# BeagleBone_Blue.net
KiCad netlist of a schematic drawn in EAGLE
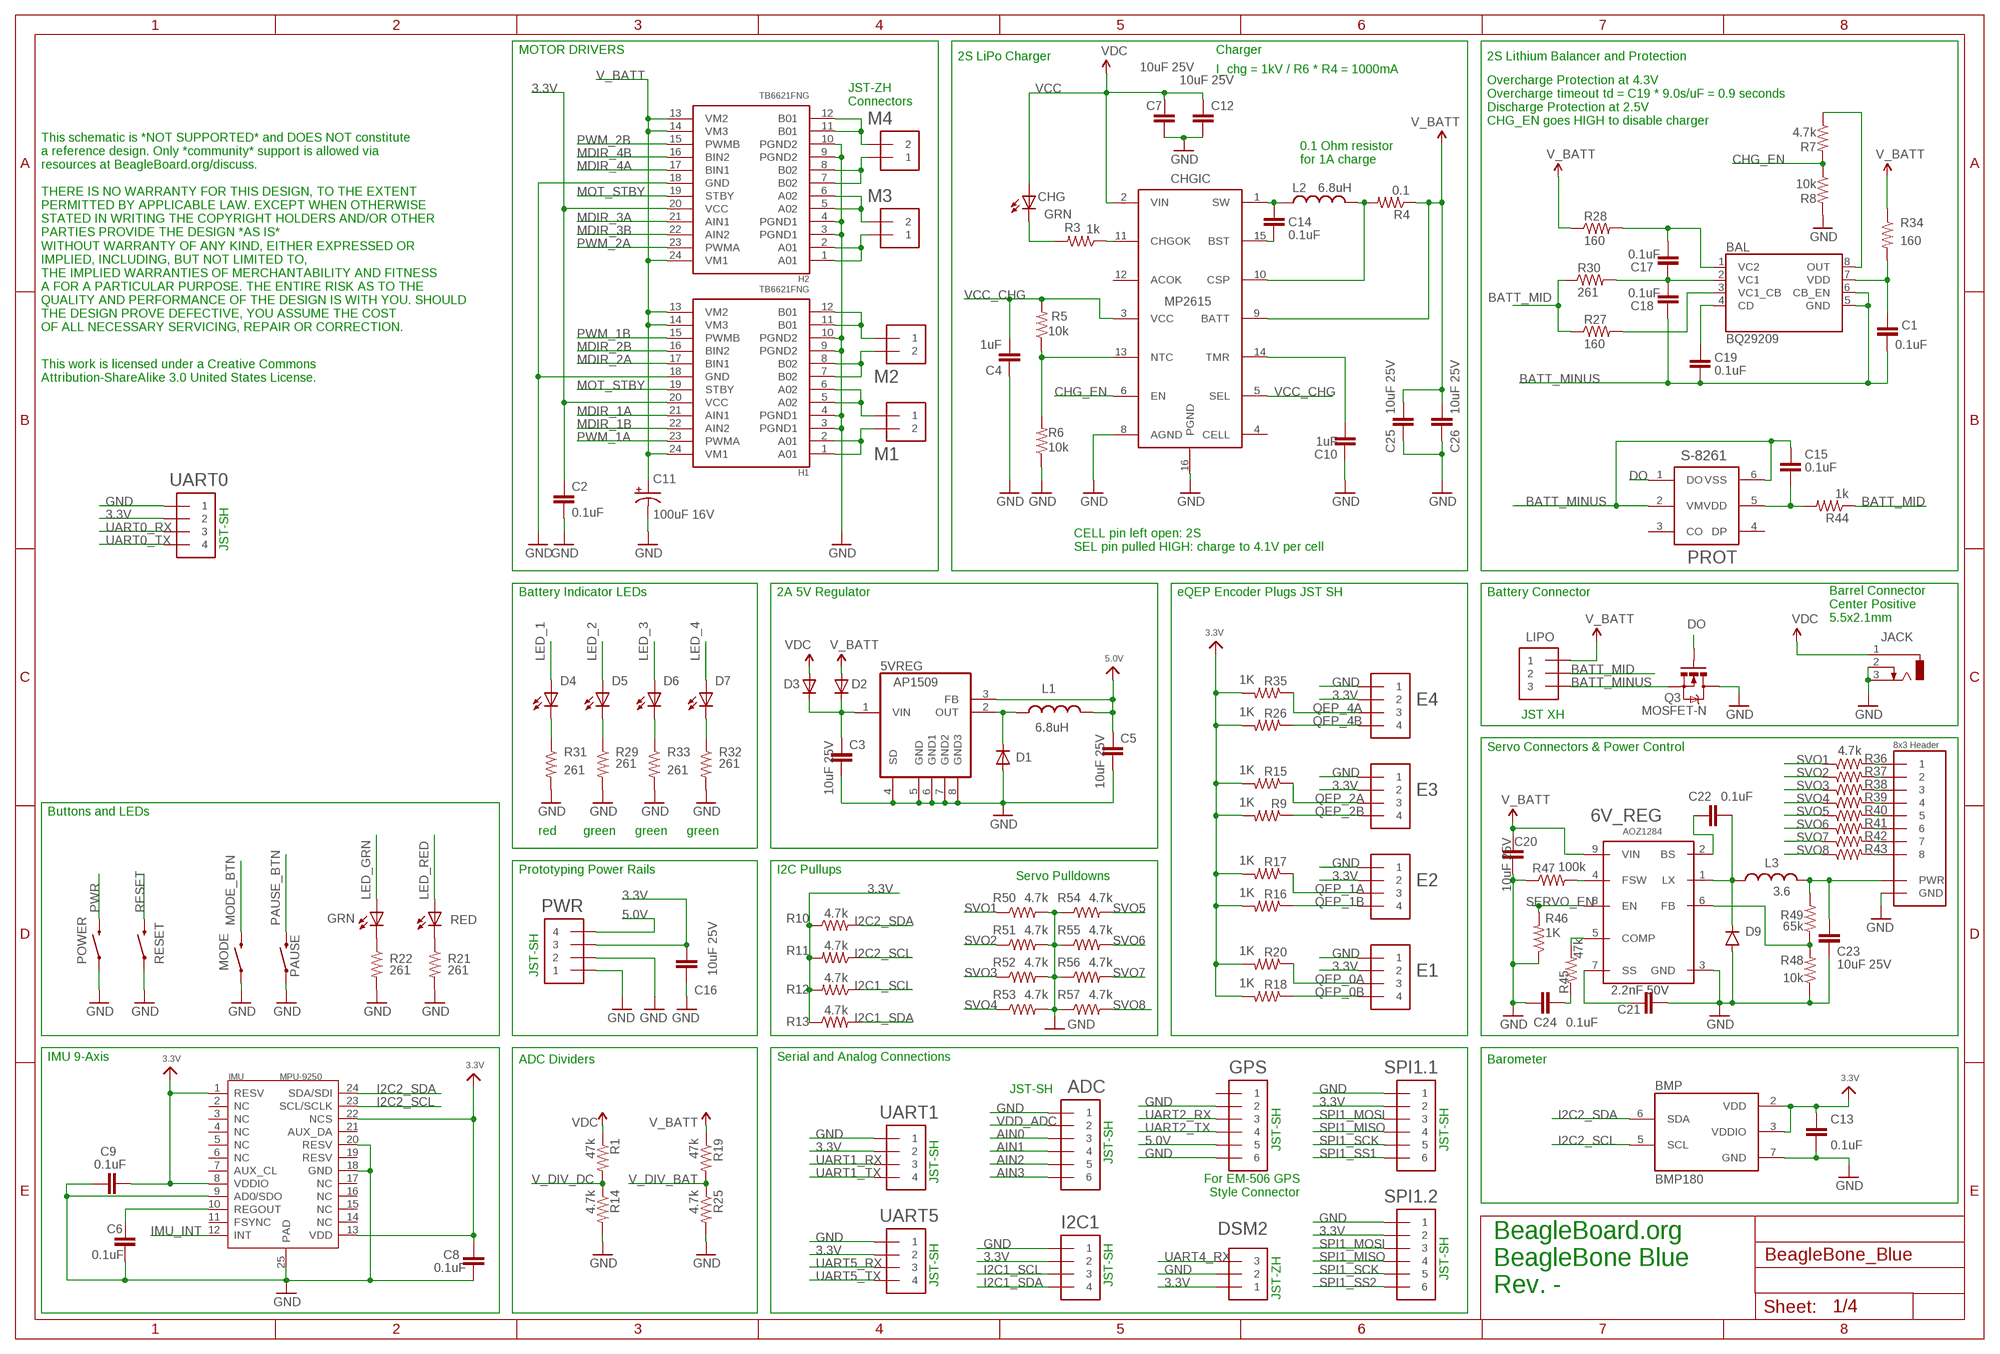
[diagram p0: schematic, sheet 1]
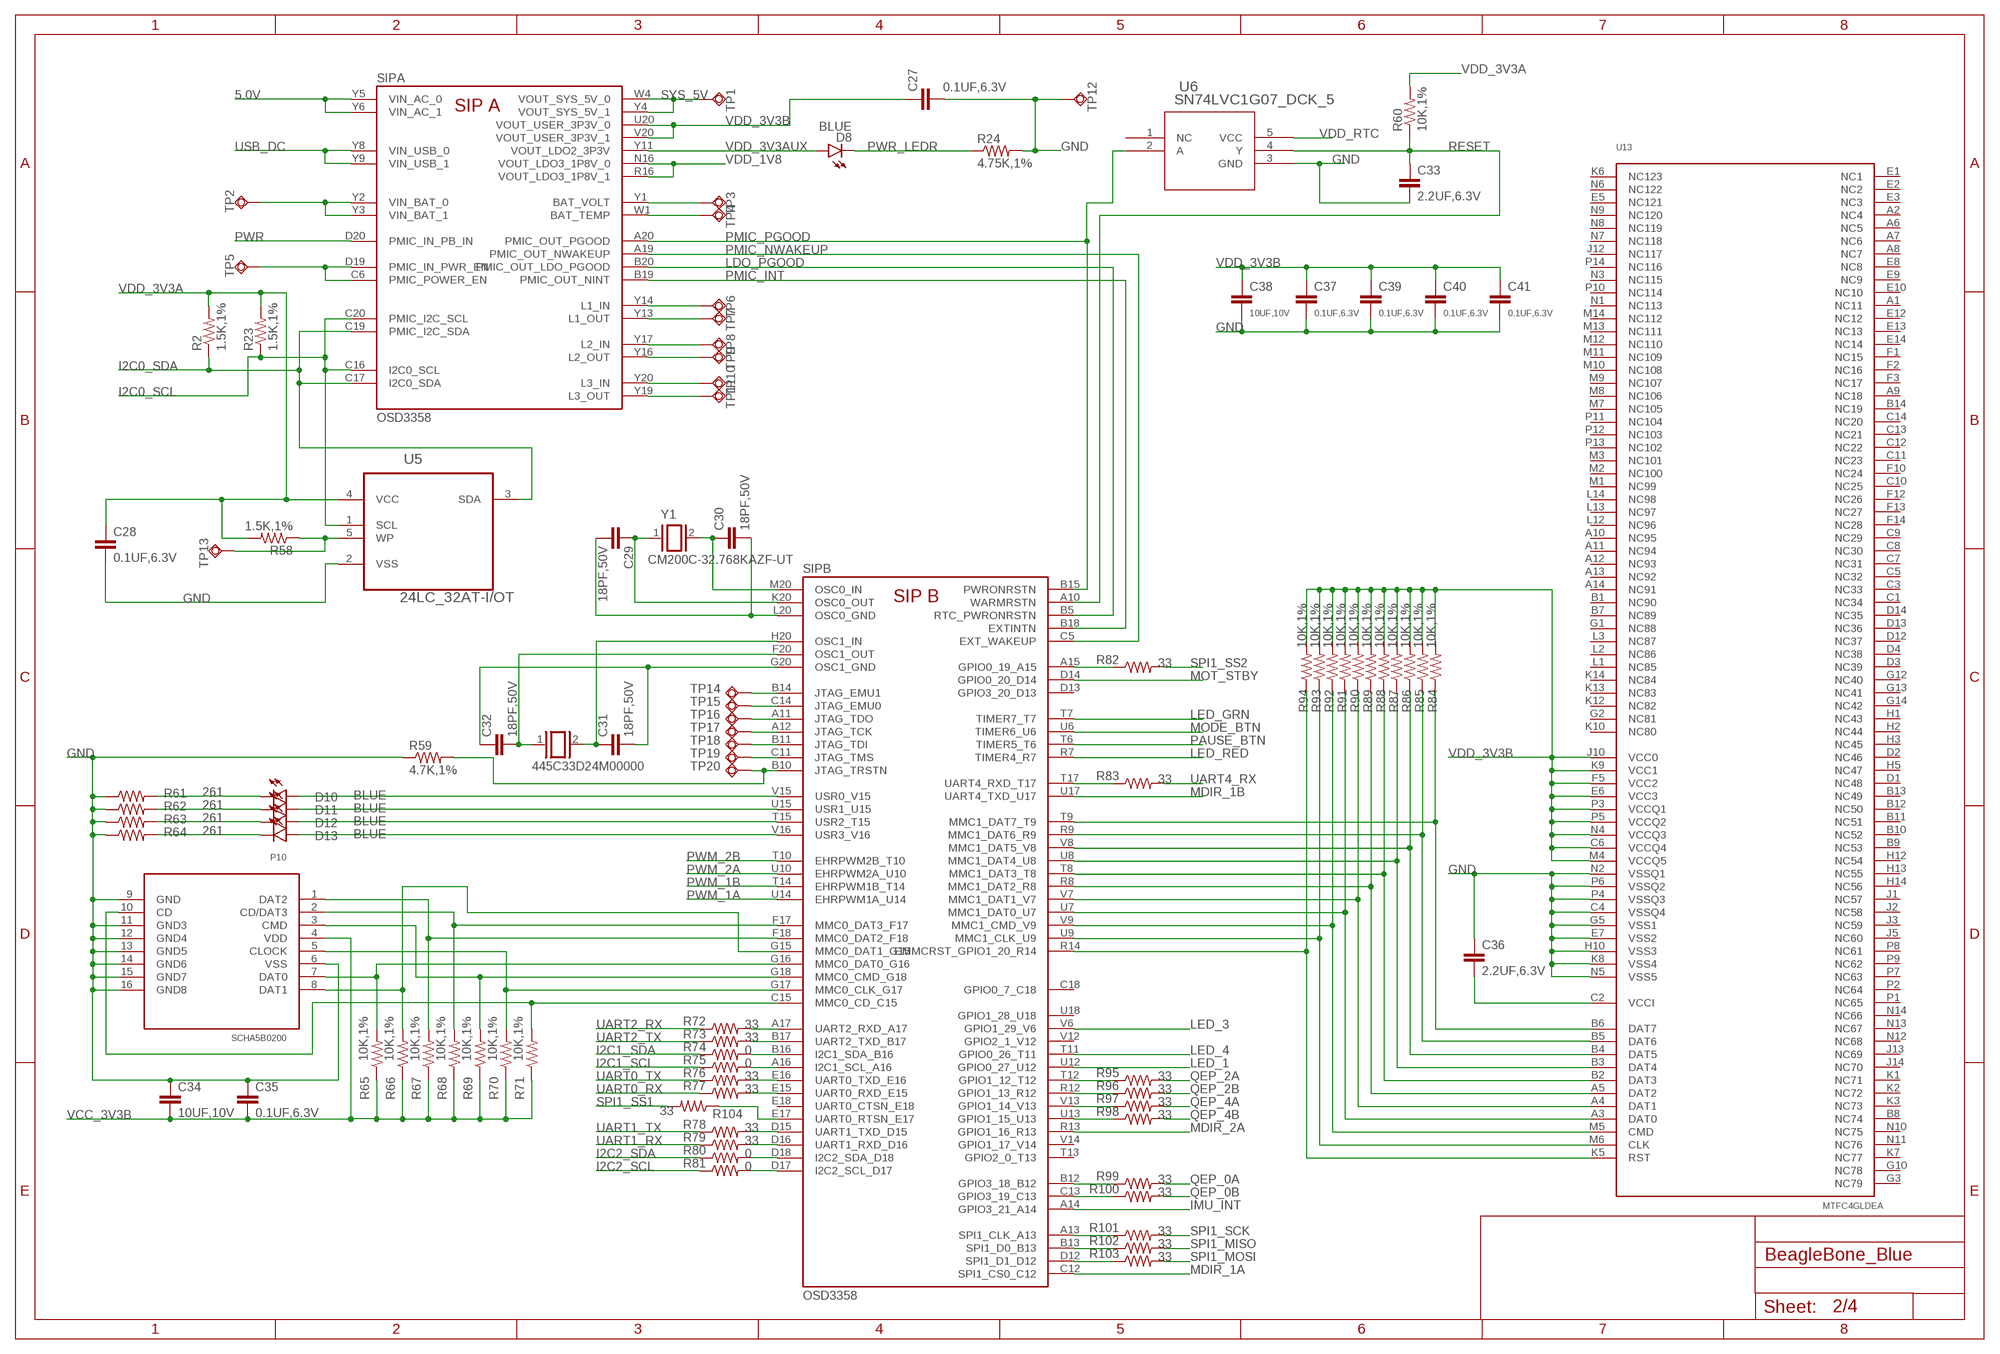
[diagram p1: schematic, sheet 2]
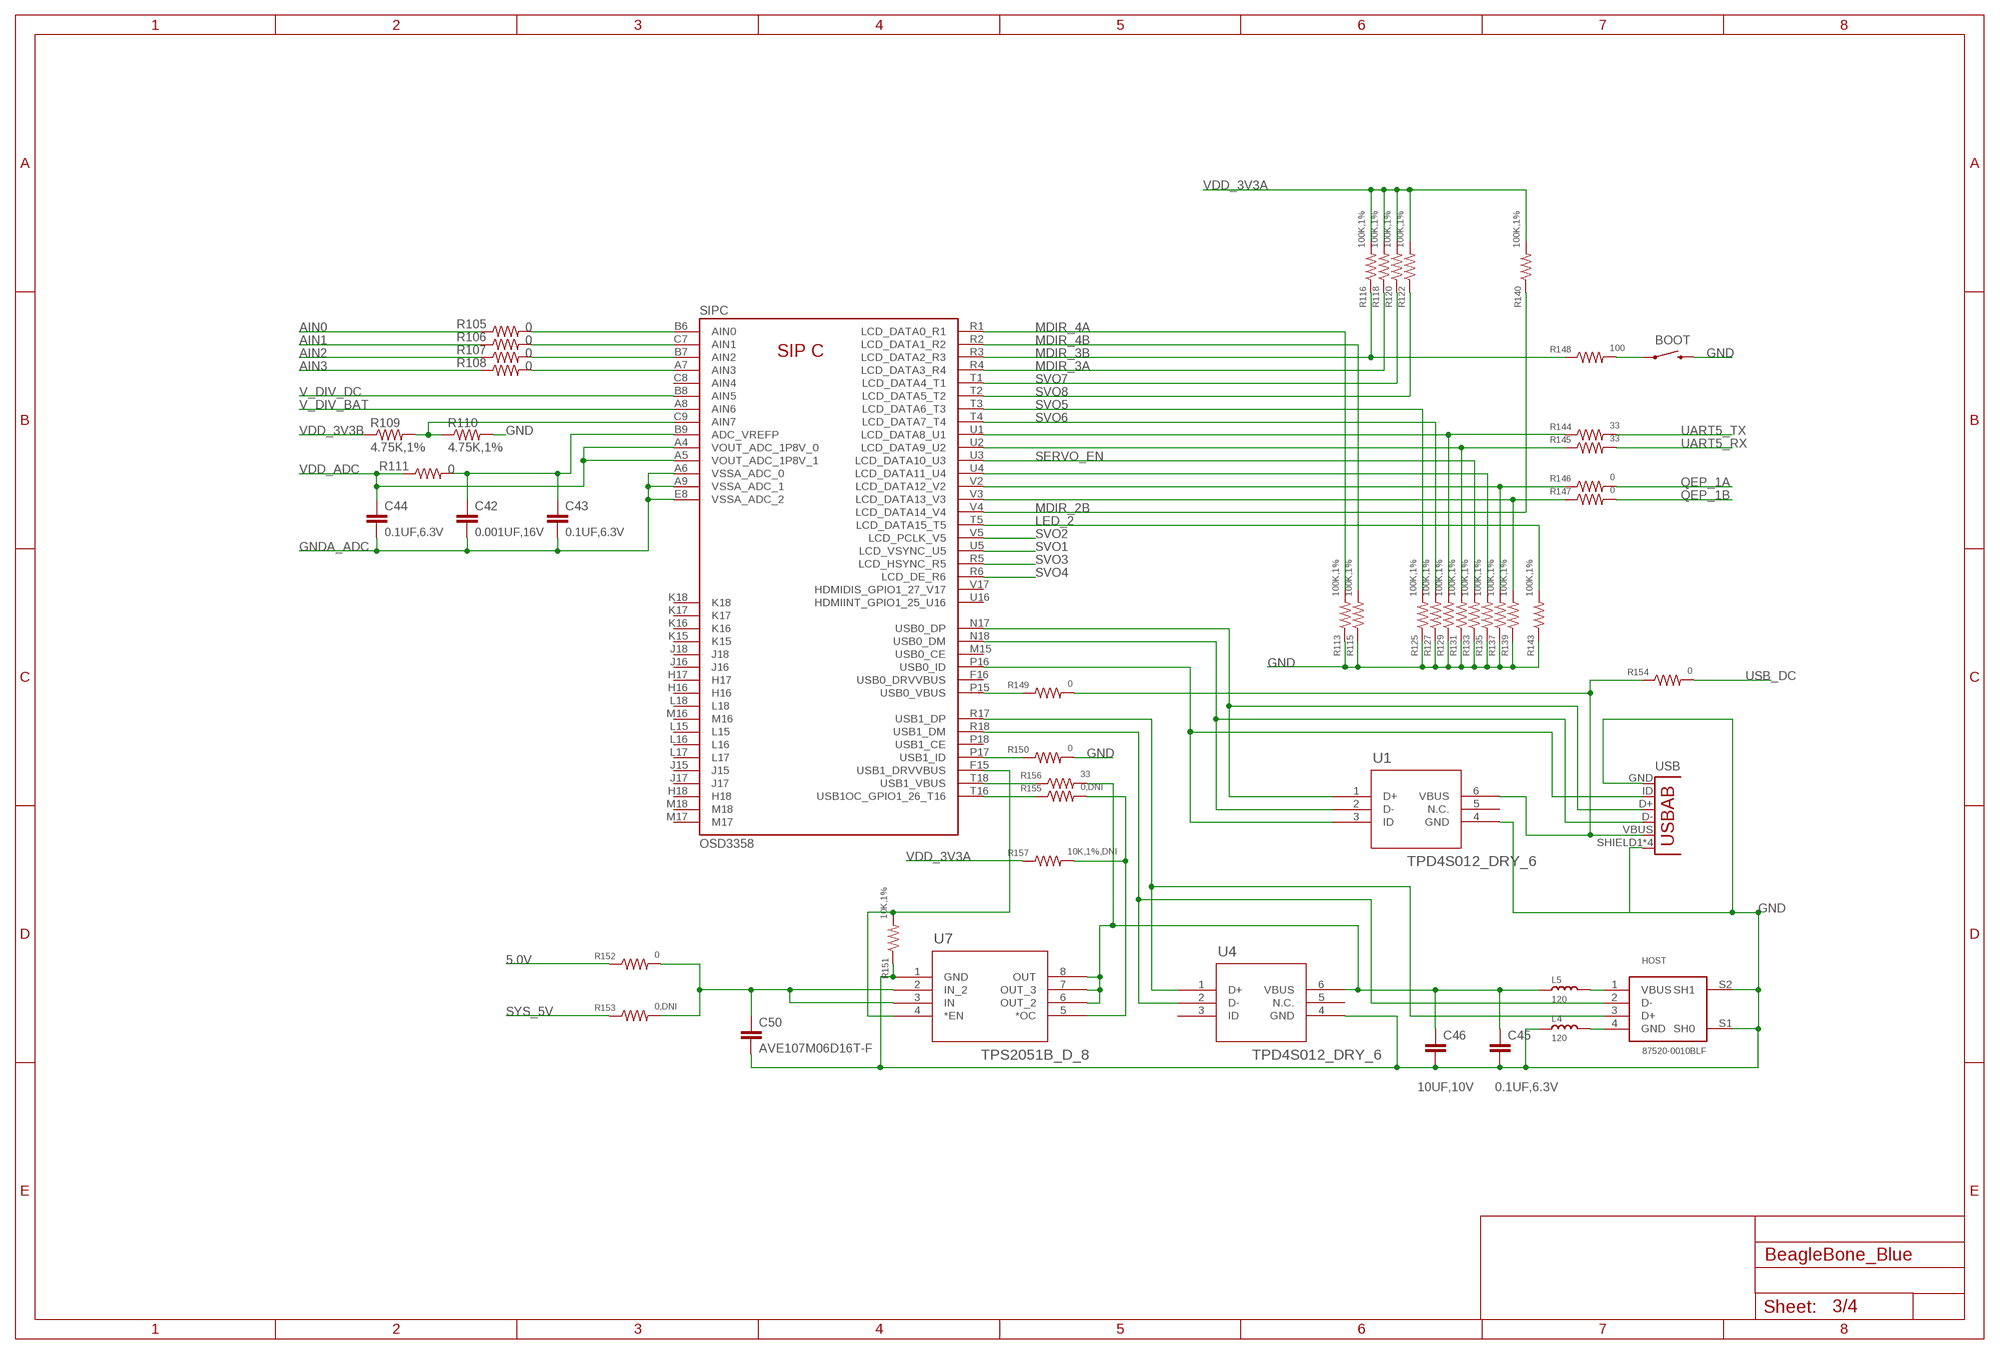
[diagram p2: schematic, sheet 3]
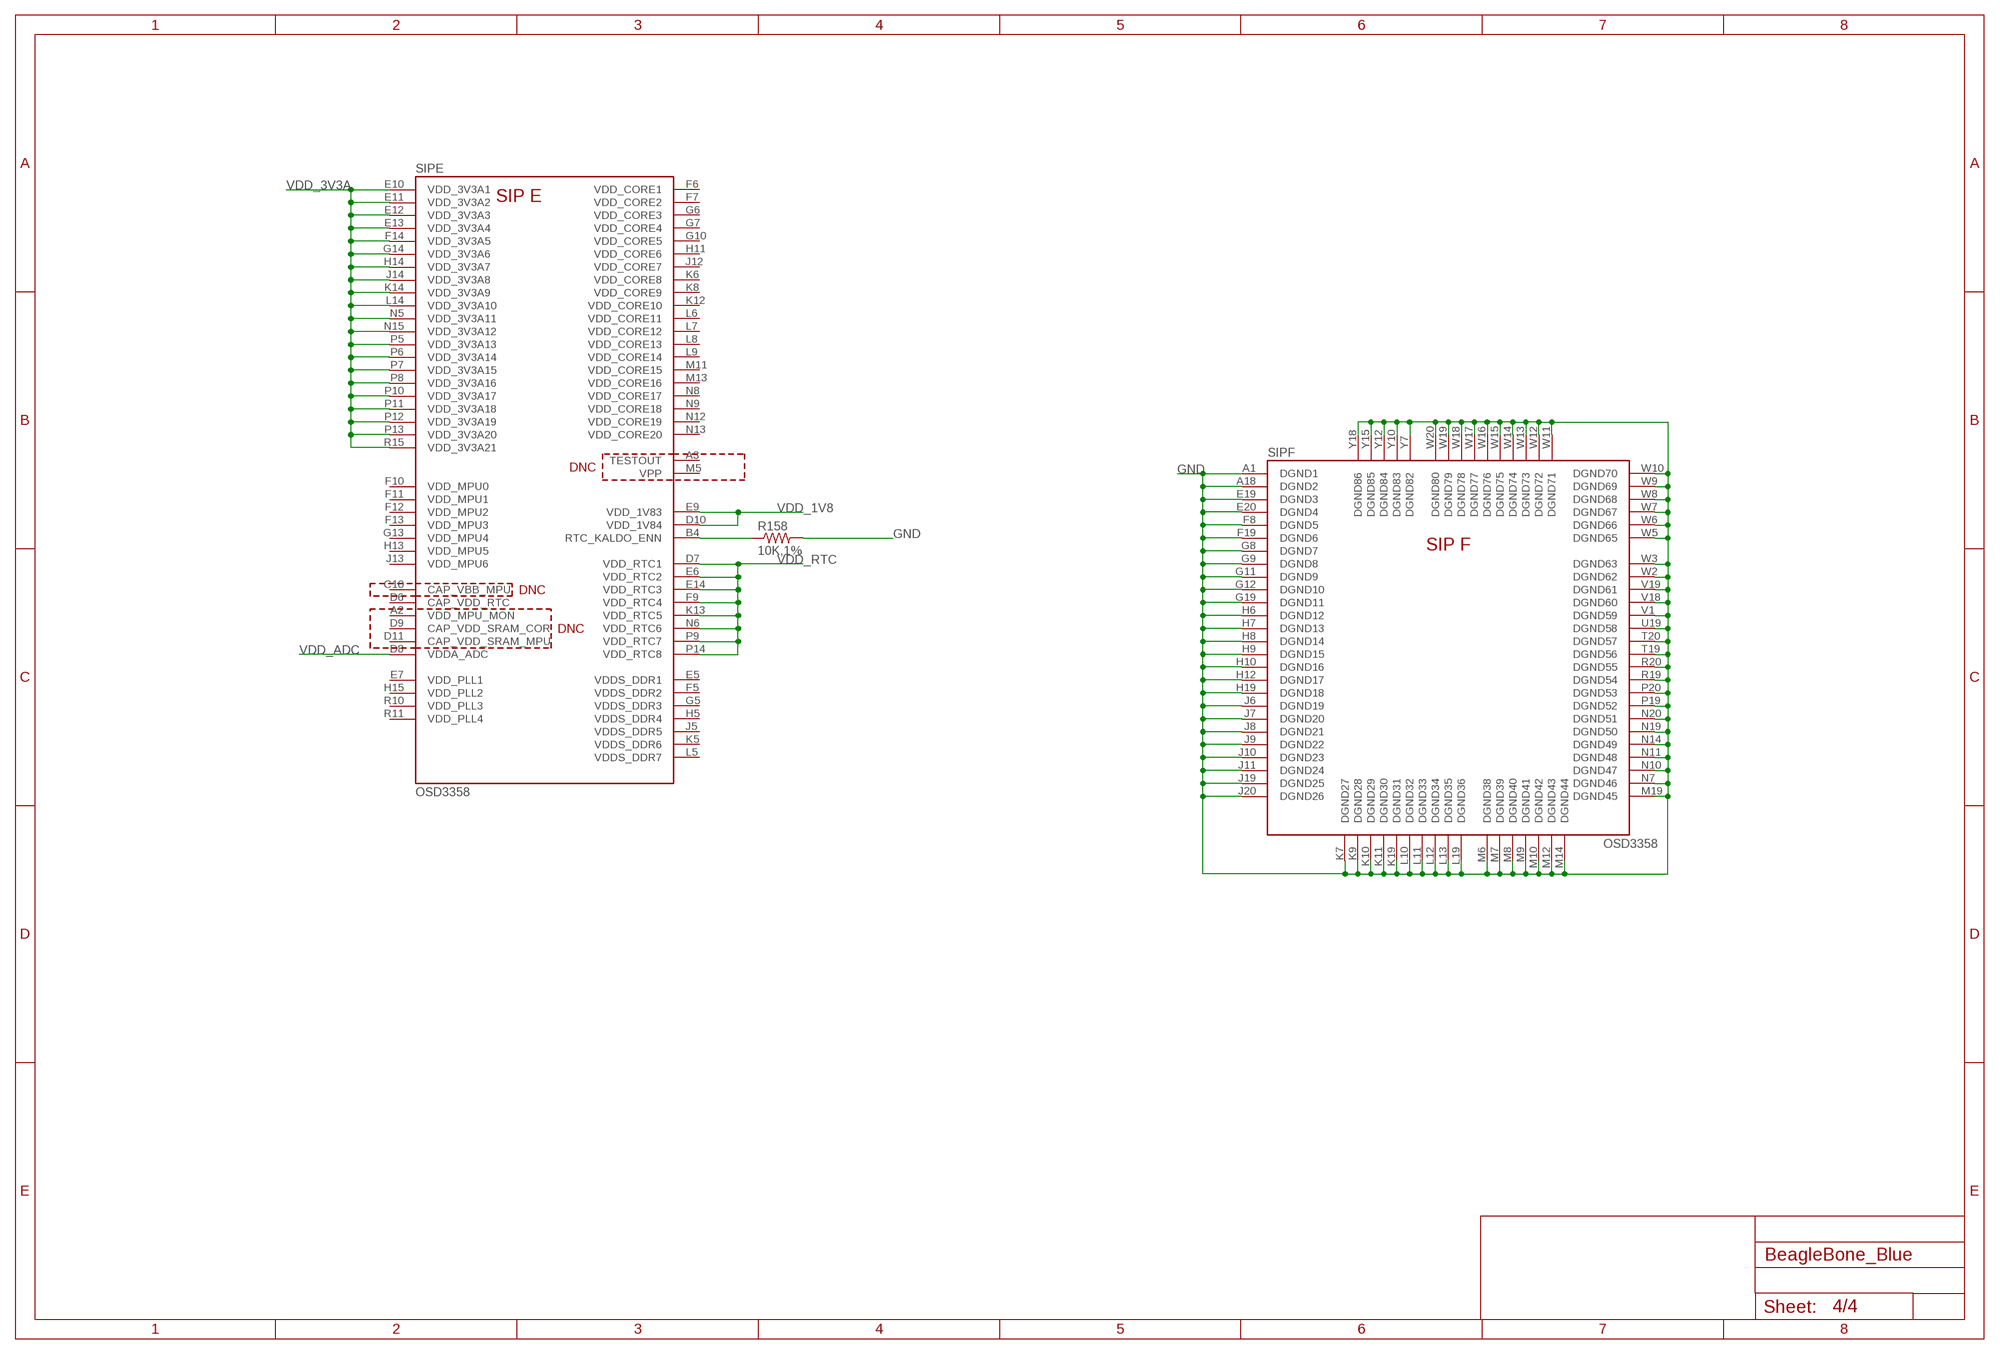
[diagram p3: schematic, sheet 4]

(export (version "E")
  (design (tool "Eeschema 10.0.6"))
  (components
    (comp (ref "5VREG")
      (value "AP1509SOIC-8-TIGHT")
      (footprint "eagle-import:SO08-TIGHT")
      (libsource (lib "eagle-import") (part "AP1509SOIC-8-TIGHT"))
    )
    (comp (ref "6V_REG")
      (value "AOZ1284")
      (footprint "eagle-import:SO08-EXPOSED")
      (libsource (lib "eagle-import") (part "AOZ1284"))
    )
    (comp (ref "ADC")
      (value "JST_SH_6")
      (footprint "eagle-import:JST_SH_6")
      (libsource (lib "eagle-import") (part "JST_SH_6"))
    )
    (comp (ref "BAL")
      (value "BQ29209")
      (footprint "eagle-import:8-SON_3X3MM")
      (libsource (lib "eagle-import") (part "BQ29209"))
    )
    (comp (ref "BMP")
      (value "BMP180")
      (footprint "eagle-import:BMP180")
      (libsource (lib "eagle-import") (part "BMP180"))
    )
    (comp (ref "C1")
      (value "0.1uF")
      (footprint "eagle-import:0402-CAP")
      (libsource (lib "eagle-import") (part "Strawson_Eagle_Lib_CAP0402-CAP"))
    )
    (comp (ref "C2")
      (value "0.1uF")
      (footprint "eagle-import:0402-CAP")
      (libsource (lib "eagle-import") (part "Strawson_Eagle_Lib_CAP0402-CAP"))
    )
    (comp (ref "C3")
      (value "10uF 25V")
      (footprint "eagle-import:0805")
      (libsource (lib "eagle-import") (part "CAP0805"))
    )
    (comp (ref "C4")
      (value "1uF")
      (footprint "eagle-import:0402-CAP")
      (libsource (lib "eagle-import") (part "Strawson_Eagle_Lib_CAP0402-CAP"))
    )
    (comp (ref "C5")
      (value "10uF 25V")
      (footprint "eagle-import:0805")
      (libsource (lib "eagle-import") (part "CAP0805"))
    )
    (comp (ref "C6")
      (value "0.1uF")
      (footprint "eagle-import:0402-CAP")
      (libsource (lib "eagle-import") (part "Strawson_Eagle_Lib_CAP0402-CAP"))
    )
    (comp (ref "C7")
      (value "10uF 25V")
      (footprint "eagle-import:0805")
      (libsource (lib "eagle-import") (part "CAP0805"))
    )
    (comp (ref "C8")
      (value "0.1uF")
      (footprint "eagle-import:0402-CAP")
      (libsource (lib "eagle-import") (part "Strawson_Eagle_Lib_CAP0402-CAP"))
    )
    (comp (ref "C9")
      (value "0.1uF")
      (footprint "eagle-import:0402-CAP")
      (libsource (lib "eagle-import") (part "Strawson_Eagle_Lib_CAP0402-CAP"))
    )
    (comp (ref "C10")
      (value "1uF")
      (footprint "eagle-import:0402-CAP")
      (libsource (lib "eagle-import") (part "Strawson_Eagle_Lib_CAP0402-CAP"))
    )
    (comp (ref "C11")
      (value "100uF 16V")
      (footprint "eagle-import:PANASONIC_D")
      (libsource (lib "eagle-import") (part "CPOL-USD"))
    )
    (comp (ref "C12")
      (value "10uF 25V")
      (footprint "eagle-import:0805")
      (libsource (lib "eagle-import") (part "CAP0805"))
    )
    (comp (ref "C13")
      (value "0.1uF")
      (footprint "eagle-import:0402-CAP")
      (libsource (lib "eagle-import") (part "Strawson_Eagle_Lib_CAP0402-CAP"))
    )
    (comp (ref "C14")
      (value "0.1uF")
      (footprint "eagle-import:0402-CAP")
      (libsource (lib "eagle-import") (part "Strawson_Eagle_Lib_CAP0402-CAP"))
    )
    (comp (ref "C15")
      (value "0.1uF")
      (footprint "eagle-import:0402-CAP")
      (libsource (lib "eagle-import") (part "Strawson_Eagle_Lib_CAP0402-CAP"))
    )
    (comp (ref "C16")
      (value "10uF 25V")
      (footprint "eagle-import:0805")
      (libsource (lib "eagle-import") (part "CAP0805"))
    )
    (comp (ref "C17")
      (value "0.1uF")
      (footprint "eagle-import:0402-CAP")
      (libsource (lib "eagle-import") (part "Strawson_Eagle_Lib_CAP0402-CAP"))
    )
    (comp (ref "C18")
      (value "0.1uF")
      (footprint "eagle-import:0402-CAP")
      (libsource (lib "eagle-import") (part "Strawson_Eagle_Lib_CAP0402-CAP"))
    )
    (comp (ref "C19")
      (value "0.1uF")
      (footprint "eagle-import:0402-CAP")
      (libsource (lib "eagle-import") (part "Strawson_Eagle_Lib_CAP0402-CAP"))
    )
    (comp (ref "C20")
      (value "10uF 25V")
      (footprint "eagle-import:0805")
      (libsource (lib "eagle-import") (part "CAP0805"))
    )
    (comp (ref "C21")
      (value "2.2nF 50V")
      (footprint "eagle-import:0402-CAP")
      (libsource (lib "eagle-import") (part "Strawson_Eagle_Lib_CAP0402-CAP"))
    )
    (comp (ref "C22")
      (value "0.1uF")
      (footprint "eagle-import:0402-CAP")
      (libsource (lib "eagle-import") (part "Strawson_Eagle_Lib_CAP0402-CAP"))
    )
    (comp (ref "C23")
      (value "10uF 25V")
      (footprint "eagle-import:0805")
      (libsource (lib "eagle-import") (part "CAP0805"))
    )
    (comp (ref "C24")
      (value "0.1uF")
      (footprint "eagle-import:0402-CAP")
      (libsource (lib "eagle-import") (part "Strawson_Eagle_Lib_CAP0402-CAP"))
    )
    (comp (ref "C25")
      (value "10uF 25V")
      (footprint "eagle-import:0805")
      (libsource (lib "eagle-import") (part "CAP0805"))
    )
    (comp (ref "C26")
      (value "10uF 25V")
      (footprint "eagle-import:0805")
      (libsource (lib "eagle-import") (part "CAP0805"))
    )
    (comp (ref "CHG")
      (value "GRN")
      (footprint "eagle-import:LED-0603")
      (libsource (lib "eagle-import") (part "SparkFun-LED_LED0603"))
    )
    (comp (ref "CHGIC")
      (value "MP2615")
      (footprint "eagle-import:MP2615")
      (libsource (lib "eagle-import") (part "MP2615"))
    )
    (comp (ref "D1")
      (value "DIODESOD-123")
      (footprint "eagle-import:SOD-123")
      (libsource (lib "eagle-import") (part "DIODESOD-123"))
    )
    (comp (ref "D2")
      (value "DIODESOD-123")
      (footprint "eagle-import:SOD-123")
      (libsource (lib "eagle-import") (part "DIODESOD-123"))
    )
    (comp (ref "D3")
      (value "DIODESOD-123")
      (footprint "eagle-import:SOD-123")
      (libsource (lib "eagle-import") (part "DIODESOD-123"))
    )
    (comp (ref "D4")
      (value "RED")
      (footprint "eagle-import:LED-0603")
      (libsource (lib "eagle-import") (part "SparkFun-LED_LED0603"))
    )
    (comp (ref "D5")
      (value "GREEN")
      (footprint "eagle-import:LED-0603")
      (libsource (lib "eagle-import") (part "SparkFun-LED_LED0603"))
    )
    (comp (ref "D6")
      (value "GREEN")
      (footprint "eagle-import:LED-0603")
      (libsource (lib "eagle-import") (part "SparkFun-LED_LED0603"))
    )
    (comp (ref "D7")
      (value "GREEN")
      (footprint "eagle-import:LED-0603")
      (libsource (lib "eagle-import") (part "SparkFun-LED_LED0603"))
    )
    (comp (ref "D9")
      (value "DIODEDO214AA")
      (footprint "eagle-import:DO-214AA")
      (libsource (lib "eagle-import") (part "DIODEDO214AA"))
    )
    (comp (ref "DSM2")
      (value "JST_ZH_3SMD_TOP")
      (footprint "eagle-import:JST_ZH_3_SMD_TOP")
      (libsource (lib "eagle-import") (part "JST_ZH_3SMD_TOP"))
    )
    (comp (ref "E1")
      (value "JST_SH_4")
      (footprint "eagle-import:JST_SH_4_SMD")
      (libsource (lib "eagle-import") (part "JST_SH_4"))
    )
    (comp (ref "E2")
      (value "JST_SH_4")
      (footprint "eagle-import:JST_SH_4_SMD")
      (libsource (lib "eagle-import") (part "JST_SH_4"))
    )
    (comp (ref "E3")
      (value "JST_SH_4")
      (footprint "eagle-import:JST_SH_4_SMD")
      (libsource (lib "eagle-import") (part "JST_SH_4"))
    )
    (comp (ref "E4")
      (value "JST_SH_4")
      (footprint "eagle-import:JST_SH_4_SMD")
      (libsource (lib "eagle-import") (part "JST_SH_4"))
    )
    (comp (ref "GPS")
      (value "JST_SH_6")
      (footprint "eagle-import:JST_SH_6")
      (libsource (lib "eagle-import") (part "JST_SH_6"))
    )
    (comp (ref "GRN")
      (value "GRN")
      (footprint "eagle-import:LED-0603")
      (libsource (lib "eagle-import") (part "SparkFun-LED_LED0603"))
    )
    (comp (ref "H1")
      (value "TB6621FNG")
      (footprint "eagle-import:SSOP24")
      (libsource (lib "eagle-import") (part "TB6621FNG"))
    )
    (comp (ref "H2")
      (value "TB6621FNG")
      (footprint "eagle-import:SSOP24")
      (libsource (lib "eagle-import") (part "TB6621FNG"))
    )
    (comp (ref "I2C1")
      (value "JST_SH_4")
      (footprint "eagle-import:JST_SH_4_SMD")
      (libsource (lib "eagle-import") (part "JST_SH_4"))
    )
    (comp (ref "IMU")
      (value "MPU-9250")
      (footprint "eagle-import:QFN24G-0.4-3X3MM")
      (libsource (lib "eagle-import") (part "MPU-9250"))
    )
    (comp (ref "JACK")
      (value "5.5x2.1mm")
      (footprint "eagle-import:DCJ0303")
      (libsource (lib "eagle-import") (part "DCJ0303"))
    )
    (comp (ref "L1")
      (value "6.8uH")
      (footprint "eagle-import:SRN6045")
      (libsource (lib "eagle-import") (part "INDUCTORBOURNS_SRN6045"))
    )
    (comp (ref "L2")
      (value "6.8uH")
      (footprint "eagle-import:SRN6045")
      (libsource (lib "eagle-import") (part "INDUCTORBOURNS_SRN6045"))
    )
    (comp (ref "L3")
      (value "3.6")
      (footprint "eagle-import:8X8MM_INDUCTOR")
      (libsource (lib "eagle-import") (part "INDUCTOR"))
    )
    (comp (ref "LIPO")
      (value "JST_XH_3-PIN")
      (footprint "eagle-import:JST_XH_3-PIN")
      (libsource (lib "eagle-import") (part "JST_XH_3-PIN"))
    )
    (comp (ref "M1")
      (value "JST_ZH_2")
      (footprint "eagle-import:JST_ZH_2")
      (libsource (lib "eagle-import") (part "JST_ZH_2"))
    )
    (comp (ref "M2")
      (value "JST_ZH_2")
      (footprint "eagle-import:JST_ZH_2")
      (libsource (lib "eagle-import") (part "JST_ZH_2"))
    )
    (comp (ref "M3")
      (value "JST_ZH_2")
      (footprint "eagle-import:JST_ZH_2")
      (libsource (lib "eagle-import") (part "JST_ZH_2"))
    )
    (comp (ref "M4")
      (value "JST_ZH_2")
      (footprint "eagle-import:JST_ZH_2")
      (libsource (lib "eagle-import") (part "JST_ZH_2"))
    )
    (comp (ref "MODE")
      (value "SWITCH-MOMENTARY-2SMD-1101NE")
      (footprint "eagle-import:TACTILE-SWITCH-1101NE")
      (libsource (lib "eagle-import") (part "SWITCH-MOMENTARY-2SMD-1101NE"))
    )
    (comp (ref "PAUSE")
      (value "SWITCH-MOMENTARY-2SMD-1101NE")
      (footprint "eagle-import:TACTILE-SWITCH-1101NE")
      (libsource (lib "eagle-import") (part "SWITCH-MOMENTARY-2SMD-1101NE"))
    )
    (comp (ref "POWER")
      (value "SWITCH-MOMENTARY-2SMD-1101NE")
      (footprint "eagle-import:TACTILE-SWITCH-1101NE")
      (libsource (lib "eagle-import") (part "SWITCH-MOMENTARY-2SMD-1101NE"))
    )
    (comp (ref "PROT")
      (value "S-8261")
      (footprint "eagle-import:SOT-236")
      (libsource (lib "eagle-import") (part "S-8261"))
    )
    (comp (ref "PWR")
      (value "JST_SH_4")
      (footprint "eagle-import:JST_SH_4_SMD")
      (libsource (lib "eagle-import") (part "JST_SH_4"))
    )
    (comp (ref "Q3")
      (value "MOSFET-N")
      (footprint "eagle-import:SO08-TIGHT")
      (libsource (lib "eagle-import") (part "MOSFET-NCHANNEL"))
    )
    (comp (ref "R1")
      (value "47k")
      (footprint "eagle-import:0402-RES")
      (libsource (lib "eagle-import") (part "RESISTOR0402-RES"))
    )
    (comp (ref "R3")
      (value "1k")
      (footprint "eagle-import:0402-RES")
      (libsource (lib "eagle-import") (part "RESISTOR0402-RES"))
    )
    (comp (ref "R4")
      (value "0.1")
      (footprint "eagle-import:0603-RES")
      (libsource (lib "eagle-import") (part "RESISTOR0603"))
    )
    (comp (ref "R5")
      (value "10k")
      (footprint "eagle-import:0402-RES")
      (libsource (lib "eagle-import") (part "RESISTOR0402-RES"))
    )
    (comp (ref "R6")
      (value "10k")
      (footprint "eagle-import:0402-RES")
      (libsource (lib "eagle-import") (part "RESISTOR0402-RES"))
    )
    (comp (ref "R7")
      (value "4.7k")
      (footprint "eagle-import:0402-RES")
      (libsource (lib "eagle-import") (part "RESISTOR0402-RES"))
    )
    (comp (ref "R8")
      (value "10k")
      (footprint "eagle-import:0402-RES")
      (libsource (lib "eagle-import") (part "RESISTOR0402-RES"))
    )
    (comp (ref "R9")
      (value "1K")
      (footprint "eagle-import:0402-RES")
      (libsource (lib "eagle-import") (part "RESISTOR0402-RES"))
    )
    (comp (ref "R10")
      (value "4.7k")
      (footprint "eagle-import:0402-RES")
      (libsource (lib "eagle-import") (part "RESISTOR0402-RES"))
    )
    (comp (ref "R11")
      (value "4.7k")
      (footprint "eagle-import:0402-RES")
      (libsource (lib "eagle-import") (part "RESISTOR0402-RES"))
    )
    (comp (ref "R12")
      (value "4.7k")
      (footprint "eagle-import:0402-RES")
      (libsource (lib "eagle-import") (part "RESISTOR0402-RES"))
    )
    (comp (ref "R13")
      (value "4.7k")
      (footprint "eagle-import:0402-RES")
      (libsource (lib "eagle-import") (part "RESISTOR0402-RES"))
    )
    (comp (ref "R14")
      (value "4.7k")
      (footprint "eagle-import:0402-RES")
      (libsource (lib "eagle-import") (part "RESISTOR0402-RES"))
    )
    (comp (ref "R15")
      (value "1K")
      (footprint "eagle-import:0402-RES")
      (libsource (lib "eagle-import") (part "RESISTOR0402-RES"))
    )
    (comp (ref "R16")
      (value "1K")
      (footprint "eagle-import:0402-RES")
      (libsource (lib "eagle-import") (part "RESISTOR0402-RES"))
    )
    (comp (ref "R17")
      (value "1K")
      (footprint "eagle-import:0402-RES")
      (libsource (lib "eagle-import") (part "RESISTOR0402-RES"))
    )
    (comp (ref "R18")
      (value "1K")
      (footprint "eagle-import:0402-RES")
      (libsource (lib "eagle-import") (part "RESISTOR0402-RES"))
    )
    (comp (ref "R19")
      (value "47k")
      (footprint "eagle-import:0402-RES")
      (libsource (lib "eagle-import") (part "RESISTOR0402-RES"))
    )
    (comp (ref "R20")
      (value "1K")
      (footprint "eagle-import:0402-RES")
      (libsource (lib "eagle-import") (part "RESISTOR0402-RES"))
    )
    (comp (ref "R21")
      (value "261")
      (footprint "eagle-import:0402-RES")
      (libsource (lib "eagle-import") (part "RESISTOR0402-RES"))
    )
    (comp (ref "R22")
      (value "261")
      (footprint "eagle-import:0402-RES")
      (libsource (lib "eagle-import") (part "RESISTOR0402-RES"))
    )
    (comp (ref "R25")
      (value "4.7k")
      (footprint "eagle-import:0402-RES")
      (libsource (lib "eagle-import") (part "RESISTOR0402-RES"))
    )
    (comp (ref "R26")
      (value "1K")
      (footprint "eagle-import:0402-RES")
      (libsource (lib "eagle-import") (part "RESISTOR0402-RES"))
    )
    (comp (ref "R27")
      (value "160")
      (footprint "eagle-import:0402-RES")
      (libsource (lib "eagle-import") (part "RESISTOR0402-RES"))
    )
    (comp (ref "R28")
      (value "160")
      (footprint "eagle-import:0402-RES")
      (libsource (lib "eagle-import") (part "RESISTOR0402-RES"))
    )
    (comp (ref "R29")
      (value "261")
      (footprint "eagle-import:0402-RES")
      (libsource (lib "eagle-import") (part "RESISTOR0402-RES"))
    )
    (comp (ref "R30")
      (value "261")
      (footprint "eagle-import:0402-RES")
      (libsource (lib "eagle-import") (part "RESISTOR0402-RES"))
    )
    (comp (ref "R31")
      (value "261")
      (footprint "eagle-import:0402-RES")
      (libsource (lib "eagle-import") (part "RESISTOR0402-RES"))
    )
    (comp (ref "R32")
      (value "261")
      (footprint "eagle-import:0402-RES")
      (libsource (lib "eagle-import") (part "RESISTOR0402-RES"))
    )
    (comp (ref "R33")
      (value "261")
      (footprint "eagle-import:0402-RES")
      (libsource (lib "eagle-import") (part "RESISTOR0402-RES"))
    )
    (comp (ref "R34")
      (value "160")
      (footprint "eagle-import:0402-RES")
      (libsource (lib "eagle-import") (part "RESISTOR0402-RES"))
    )
    (comp (ref "R35")
      (value "1K")
      (footprint "eagle-import:0402-RES")
      (libsource (lib "eagle-import") (part "RESISTOR0402-RES"))
    )
    (comp (ref "R36")
      (value "4.7k")
      (footprint "eagle-import:0402-RES")
      (libsource (lib "eagle-import") (part "RESISTOR0402-RES"))
    )
    (comp (ref "R37")
      (value "4.7k")
      (footprint "eagle-import:0402-RES")
      (libsource (lib "eagle-import") (part "RESISTOR0402-RES"))
    )
    (comp (ref "R38")
      (value "4.7k")
      (footprint "eagle-import:0402-RES")
      (libsource (lib "eagle-import") (part "RESISTOR0402-RES"))
    )
    (comp (ref "R39")
      (value "4.7k")
      (footprint "eagle-import:0402-RES")
      (libsource (lib "eagle-import") (part "RESISTOR0402-RES"))
    )
    (comp (ref "R40")
      (value "4.7k")
      (footprint "eagle-import:0402-RES")
      (libsource (lib "eagle-import") (part "RESISTOR0402-RES"))
    )
    (comp (ref "R41")
      (value "4.7k")
      (footprint "eagle-import:0402-RES")
      (libsource (lib "eagle-import") (part "RESISTOR0402-RES"))
    )
    (comp (ref "R42")
      (value "4.7k")
      (footprint "eagle-import:0402-RES")
      (libsource (lib "eagle-import") (part "RESISTOR0402-RES"))
    )
    (comp (ref "R43")
      (value "4.7k")
      (footprint "eagle-import:0402-RES")
      (libsource (lib "eagle-import") (part "RESISTOR0402-RES"))
    )
    (comp (ref "R44")
      (value "1k")
      (footprint "eagle-import:0402-RES")
      (libsource (lib "eagle-import") (part "RESISTOR0402-RES"))
    )
    (comp (ref "R45")
      (value "47k")
      (footprint "eagle-import:0402-RES")
      (libsource (lib "eagle-import") (part "RESISTOR0402-RES"))
    )
    (comp (ref "R46")
      (value "1K")
      (footprint "eagle-import:0402-RES")
      (libsource (lib "eagle-import") (part "RESISTOR0402-RES"))
    )
    (comp (ref "R47")
      (value "100k")
      (footprint "eagle-import:0402-RES")
      (libsource (lib "eagle-import") (part "RESISTOR0402-RES"))
    )
    (comp (ref "R48")
      (value "10k")
      (footprint "eagle-import:0402-RES")
      (libsource (lib "eagle-import") (part "RESISTOR0402-RES"))
    )
    (comp (ref "R49")
      (value "65k")
      (footprint "eagle-import:0402-RES")
      (libsource (lib "eagle-import") (part "RESISTOR0402-RES"))
    )
    (comp (ref "R50")
      (value "4.7k")
      (footprint "eagle-import:0402-RES")
      (libsource (lib "eagle-import") (part "RESISTOR0402-RES"))
    )
    (comp (ref "R51")
      (value "4.7k")
      (footprint "eagle-import:0402-RES")
      (libsource (lib "eagle-import") (part "RESISTOR0402-RES"))
    )
    (comp (ref "R52")
      (value "4.7k")
      (footprint "eagle-import:0402-RES")
      (libsource (lib "eagle-import") (part "RESISTOR0402-RES"))
    )
    (comp (ref "R53")
      (value "4.7k")
      (footprint "eagle-import:0402-RES")
      (libsource (lib "eagle-import") (part "RESISTOR0402-RES"))
    )
    (comp (ref "R54")
      (value "4.7k")
      (footprint "eagle-import:0402-RES")
      (libsource (lib "eagle-import") (part "RESISTOR0402-RES"))
    )
    (comp (ref "R55")
      (value "4.7k")
      (footprint "eagle-import:0402-RES")
      (libsource (lib "eagle-import") (part "RESISTOR0402-RES"))
    )
    (comp (ref "R56")
      (value "4.7k")
      (footprint "eagle-import:0402-RES")
      (libsource (lib "eagle-import") (part "RESISTOR0402-RES"))
    )
    (comp (ref "R57")
      (value "4.7k")
      (footprint "eagle-import:0402-RES")
      (libsource (lib "eagle-import") (part "RESISTOR0402-RES"))
    )
    (comp (ref "RED")
      (value "RED")
      (footprint "eagle-import:LED-0603")
      (libsource (lib "eagle-import") (part "SparkFun-LED_LED0603"))
    )
    (comp (ref "RESET")
      (value "SWITCH-MOMENTARY-2SMD-1101NE")
      (footprint "eagle-import:TACTILE-SWITCH-1101NE")
      (libsource (lib "eagle-import") (part "SWITCH-MOMENTARY-2SMD-1101NE"))
    )
    (comp (ref "SPI1.1")
      (value "JST_SH_6")
      (footprint "eagle-import:JST_SH_6")
      (libsource (lib "eagle-import") (part "JST_SH_6"))
    )
    (comp (ref "SPI1.2")
      (value "JST_SH_6")
      (footprint "eagle-import:JST_SH_6")
      (libsource (lib "eagle-import") (part "JST_SH_6"))
    )
    (comp (ref "U$1")
      (value "SERVO_HEADERS_8X")
      (footprint "eagle-import:3X8_0.1__HEADER")
      (libsource (lib "eagle-import") (part "SERVO_HEADERS_8X"))
    )
    (comp (ref "UART0")
      (value "JST_SH_4")
      (footprint "eagle-import:JST_SH_4_SMD")
      (libsource (lib "eagle-import") (part "JST_SH_4"))
    )
    (comp (ref "UART1")
      (value "JST_SH_4")
      (footprint "eagle-import:JST_SH_4_SMD")
      (libsource (lib "eagle-import") (part "JST_SH_4"))
    )
    (comp (ref "UART5")
      (value "JST_SH_4")
      (footprint "eagle-import:JST_SH_4_SMD")
      (libsource (lib "eagle-import") (part "JST_SH_4"))
    )
    (comp (ref "BOOT")
      (value "SWITCH-MOMENTARY-2SMD-1101NE")
      (footprint "eagle-import:TACTILE-SWITCH-1101NE")
      (libsource (lib "eagle-import") (part "SWITCH-MOMENTARY-2SMD-1101NE"))
    )
    (comp (ref "C42")
      (value "0.001UF,16V")
      (footprint "eagle-import:0402-CAP")
      (libsource (lib "eagle-import") (part "Strawson_Eagle_Lib_CAP0402-CAP"))
    )
    (comp (ref "C43")
      (value "0.1UF,6.3V")
      (footprint "eagle-import:0402-CAP")
      (libsource (lib "eagle-import") (part "Strawson_Eagle_Lib_CAP0402-CAP"))
    )
    (comp (ref "C44")
      (value "0.1UF,6.3V")
      (footprint "eagle-import:0402-CAP")
      (libsource (lib "eagle-import") (part "Strawson_Eagle_Lib_CAP0402-CAP"))
    )
    (comp (ref "C45")
      (value "0.1UF,6.3V")
      (footprint "eagle-import:0402-CAP")
      (libsource (lib "eagle-import") (part "Strawson_Eagle_Lib_CAP0402-CAP"))
    )
    (comp (ref "C46")
      (value "10UF,10V")
      (footprint "eagle-import:0805")
      (libsource (lib "eagle-import") (part "Strawson_Eagle_Lib_CAP0805"))
    )
    (comp (ref "C50")
      (value "AVE107M06D16T-F")
      (footprint "eagle-import:AVE107M06D16T-F")
      (libsource (lib "eagle-import") (part "AVE107M06D16T-F"))
    )
    (comp (ref "HOST")
      (value "87520-0010BLF")
      (footprint "eagle-import:87520-0010BLF")
      (libsource (lib "eagle-import") (part "87520-0010BLF"))
    )
    (comp (ref "L4")
      (value "120")
      (footprint "eagle-import:L0603")
      (libsource (lib "eagle-import") (part "INDUCTOR/FERRITE-BEAD'0603'"))
    )
    (comp (ref "L5")
      (value "120")
      (footprint "eagle-import:L0603")
      (libsource (lib "eagle-import") (part "INDUCTOR/FERRITE-BEAD'0603'"))
    )
    (comp (ref "R105")
      (value "0")
      (footprint "eagle-import:0402-RES")
      (libsource (lib "eagle-import") (part "RESISTOR0402-RES"))
    )
    (comp (ref "R106")
      (value "0")
      (footprint "eagle-import:0402-RES")
      (libsource (lib "eagle-import") (part "RESISTOR0402-RES"))
    )
    (comp (ref "R107")
      (value "0")
      (footprint "eagle-import:0402-RES")
      (libsource (lib "eagle-import") (part "RESISTOR0402-RES"))
    )
    (comp (ref "R108")
      (value "0")
      (footprint "eagle-import:0402-RES")
      (libsource (lib "eagle-import") (part "RESISTOR0402-RES"))
    )
    (comp (ref "R109")
      (value "4.75K,1%")
      (footprint "eagle-import:0402-RES")
      (libsource (lib "eagle-import") (part "RESISTOR0402-RES"))
    )
    (comp (ref "R110")
      (value "4.75K,1%")
      (footprint "eagle-import:0402-RES")
      (libsource (lib "eagle-import") (part "RESISTOR0402-RES"))
    )
    (comp (ref "R111")
      (value "0")
      (footprint "eagle-import:0402-RES")
      (libsource (lib "eagle-import") (part "RESISTOR0402-RES"))
    )
    (comp (ref "R113")
      (value "100K,1%")
      (footprint "eagle-import:0402-RES")
      (libsource (lib "eagle-import") (part "RESISTOR0402-RES"))
    )
    (comp (ref "R115")
      (value "100K,1%")
      (footprint "eagle-import:0402-RES")
      (libsource (lib "eagle-import") (part "RESISTOR0402-RES"))
    )
    (comp (ref "R116")
      (value "100K,1%")
      (footprint "eagle-import:0402-RES")
      (libsource (lib "eagle-import") (part "RESISTOR0402-RES"))
    )
    (comp (ref "R118")
      (value "100K,1%")
      (footprint "eagle-import:0402-RES")
      (libsource (lib "eagle-import") (part "RESISTOR0402-RES"))
    )
    (comp (ref "R120")
      (value "100K,1%")
      (footprint "eagle-import:0402-RES")
      (libsource (lib "eagle-import") (part "RESISTOR0402-RES"))
    )
    (comp (ref "R122")
      (value "100K,1%")
      (footprint "eagle-import:0402-RES")
      (libsource (lib "eagle-import") (part "RESISTOR0402-RES"))
    )
    (comp (ref "R125")
      (value "100K,1%")
      (footprint "eagle-import:0402-RES")
      (libsource (lib "eagle-import") (part "RESISTOR0402-RES"))
    )
    (comp (ref "R127")
      (value "100K,1%")
      (footprint "eagle-import:0402-RES")
      (libsource (lib "eagle-import") (part "RESISTOR0402-RES"))
    )
    (comp (ref "R129")
      (value "100K,1%")
      (footprint "eagle-import:0402-RES")
      (libsource (lib "eagle-import") (part "RESISTOR0402-RES"))
    )
    (comp (ref "R131")
      (value "100K,1%")
      (footprint "eagle-import:0402-RES")
      (libsource (lib "eagle-import") (part "RESISTOR0402-RES"))
    )
    (comp (ref "R133")
      (value "100K,1%")
      (footprint "eagle-import:0402-RES")
      (libsource (lib "eagle-import") (part "RESISTOR0402-RES"))
    )
    (comp (ref "R135")
      (value "100K,1%")
      (footprint "eagle-import:0402-RES")
      (libsource (lib "eagle-import") (part "RESISTOR0402-RES"))
    )
    (comp (ref "R137")
      (value "100K,1%")
      (footprint "eagle-import:0402-RES")
      (libsource (lib "eagle-import") (part "RESISTOR0402-RES"))
    )
    (comp (ref "R139")
      (value "100K,1%")
      (footprint "eagle-import:0402-RES")
      (libsource (lib "eagle-import") (part "RESISTOR0402-RES"))
    )
    (comp (ref "R140")
      (value "100K,1%")
      (footprint "eagle-import:0402-RES")
      (libsource (lib "eagle-import") (part "RESISTOR0402-RES"))
    )
    (comp (ref "R143")
      (value "100K,1%")
      (footprint "eagle-import:0402-RES")
      (libsource (lib "eagle-import") (part "RESISTOR0402-RES"))
    )
    (comp (ref "R144")
      (value "33")
      (footprint "eagle-import:0402-RES")
      (libsource (lib "eagle-import") (part "RESISTOR0402-RES"))
    )
    (comp (ref "R145")
      (value "33")
      (footprint "eagle-import:0402-RES")
      (libsource (lib "eagle-import") (part "RESISTOR0402-RES"))
    )
    (comp (ref "R146")
      (value "0")
      (footprint "eagle-import:0402-RES")
      (libsource (lib "eagle-import") (part "RESISTOR0402-RES"))
    )
    (comp (ref "R147")
      (value "0")
      (footprint "eagle-import:0402-RES")
      (libsource (lib "eagle-import") (part "RESISTOR0402-RES"))
    )
    (comp (ref "R148")
      (value "100")
      (footprint "eagle-import:0402-RES")
      (libsource (lib "eagle-import") (part "RESISTOR0402-RES"))
    )
    (comp (ref "R149")
      (value "0")
      (footprint "eagle-import:0402-RES")
      (libsource (lib "eagle-import") (part "RESISTOR0402-RES"))
    )
    (comp (ref "R150")
      (value "0")
      (footprint "eagle-import:0402-RES")
      (libsource (lib "eagle-import") (part "RESISTOR0402-RES"))
    )
    (comp (ref "R151")
      (value "10K,1%")
      (footprint "eagle-import:0402-RES")
      (libsource (lib "eagle-import") (part "RESISTOR0402-RES"))
    )
    (comp (ref "R152")
      (value "0")
      (footprint "eagle-import:0402-RES")
      (libsource (lib "eagle-import") (part "RESISTOR0402-RES"))
    )
    (comp (ref "R153")
      (value "0,DNI")
      (footprint "eagle-import:0402-RES")
      (libsource (lib "eagle-import") (part "RESISTOR0402-RES"))
    )
    (comp (ref "R154")
      (value "0")
      (footprint "eagle-import:0402-RES")
      (libsource (lib "eagle-import") (part "RESISTOR0402-RES"))
    )
    (comp (ref "R155")
      (value "0,DNI")
      (footprint "eagle-import:0402-RES")
      (libsource (lib "eagle-import") (part "RESISTOR0402-RES"))
    )
    (comp (ref "R156")
      (value "33")
      (footprint "eagle-import:0402-RES")
      (libsource (lib "eagle-import") (part "RESISTOR0402-RES"))
    )
    (comp (ref "R157")
      (value "10K,1%,DNI")
      (footprint "eagle-import:0402-RES")
      (libsource (lib "eagle-import") (part "RESISTOR0402-RES"))
    )
    (comp (ref "SIP")
      (value "OSD3358")
      (footprint "eagle-import:OSD3358")
      (libsource (lib "eagle-import") (part "OSD3358"))
    )
    (comp (ref "U1")
      (value "TPD4S012_DRY_6")
      (footprint "eagle-import:DRY6")
      (fields
        (field (name "GENERIC_PART_NUMBER") "TPD4S012")
        (field (name "MANUFACTURER") "Texas Instruments")
        (field (name "MANUFACTURER_PART_NUMBER") "tpd4s012_dry_6")
      )
      (libsource (lib "eagle-import") (part "TPD4S012_DRY_6"))
    )
    (comp (ref "U4")
      (value "TPD4S012_DRY_6")
      (footprint "eagle-import:DRY6")
      (fields
        (field (name "GENERIC_PART_NUMBER") "TPD4S012")
        (field (name "MANUFACTURER") "Texas Instruments")
        (field (name "MANUFACTURER_PART_NUMBER") "tpd4s012_dry_6")
      )
      (libsource (lib "eagle-import") (part "TPD4S012_DRY_6"))
    )
    (comp (ref "U7")
      (value "TPS2051B_D_8")
      (footprint "eagle-import:D8")
      (fields
        (field (name "GENERIC_PART_NUMBER") "TPS2051B")
        (field (name "MANUFACTURER") "Texas Instruments")
        (field (name "MANUFACTURER_PART_NUMBER") "tps2051b_d_8")
      )
      (libsource (lib "eagle-import") (part "TPS2051B_D_8"))
    )
    (comp (ref "USB")
      (value "USB-AB")
      (footprint "eagle-import:USB-AB-MICRO-SMD")
      (libsource (lib "eagle-import") (part "USB-AB"))
    )
    (comp (ref "C27")
      (value "0.1UF,6.3V")
      (footprint "eagle-import:0402-CAP")
      (libsource (lib "eagle-import") (part "Strawson_Eagle_Lib_CAP0402-CAP"))
    )
    (comp (ref "C28")
      (value "0.1UF,6.3V")
      (footprint "eagle-import:0402-CAP")
      (libsource (lib "eagle-import") (part "Strawson_Eagle_Lib_CAP0402-CAP"))
    )
    (comp (ref "C29")
      (value "18PF,50V")
      (footprint "eagle-import:0402-CAP")
      (libsource (lib "eagle-import") (part "Strawson_Eagle_Lib_CAP0402-CAP"))
    )
    (comp (ref "C30")
      (value "18PF,50V")
      (footprint "eagle-import:0402-CAP")
      (libsource (lib "eagle-import") (part "Strawson_Eagle_Lib_CAP0402-CAP"))
    )
    (comp (ref "C31")
      (value "18PF,50V")
      (footprint "eagle-import:0402-CAP")
      (libsource (lib "eagle-import") (part "Strawson_Eagle_Lib_CAP0402-CAP"))
    )
    (comp (ref "C32")
      (value "18PF,50V")
      (footprint "eagle-import:0402-CAP")
      (libsource (lib "eagle-import") (part "Strawson_Eagle_Lib_CAP0402-CAP"))
    )
    (comp (ref "C33")
      (value "2.2UF,6.3V")
      (footprint "eagle-import:0402-CAP")
      (libsource (lib "eagle-import") (part "Strawson_Eagle_Lib_CAP0402-CAP"))
    )
    (comp (ref "C34")
      (value "10UF,10V")
      (footprint "eagle-import:0805")
      (libsource (lib "eagle-import") (part "Strawson_Eagle_Lib_CAP0805"))
    )
    (comp (ref "C35")
      (value "0.1UF,6.3V")
      (footprint "eagle-import:0402-CAP")
      (libsource (lib "eagle-import") (part "Strawson_Eagle_Lib_CAP0402-CAP"))
    )
    (comp (ref "C36")
      (value "2.2UF,6.3V")
      (footprint "eagle-import:0402-CAP")
      (libsource (lib "eagle-import") (part "Strawson_Eagle_Lib_CAP0402-CAP"))
    )
    (comp (ref "C37")
      (value "0.1UF,6.3V")
      (footprint "eagle-import:0402-CAP")
      (libsource (lib "eagle-import") (part "Strawson_Eagle_Lib_CAP0402-CAP"))
    )
    (comp (ref "C38")
      (value "10UF,10V")
      (footprint "eagle-import:0805")
      (libsource (lib "eagle-import") (part "Strawson_Eagle_Lib_CAP0805"))
    )
    (comp (ref "C39")
      (value "0.1UF,6.3V")
      (footprint "eagle-import:0402-CAP")
      (libsource (lib "eagle-import") (part "Strawson_Eagle_Lib_CAP0402-CAP"))
    )
    (comp (ref "C40")
      (value "0.1UF,6.3V")
      (footprint "eagle-import:0402-CAP")
      (libsource (lib "eagle-import") (part "Strawson_Eagle_Lib_CAP0402-CAP"))
    )
    (comp (ref "C41")
      (value "0.1UF,6.3V")
      (footprint "eagle-import:0402-CAP")
      (libsource (lib "eagle-import") (part "Strawson_Eagle_Lib_CAP0402-CAP"))
    )
    (comp (ref "D8")
      (value "BLUE")
      (footprint "eagle-import:LED-0603")
      (libsource (lib "eagle-import") (part "LED0603"))
    )
    (comp (ref "D10")
      (value "BLUE")
      (footprint "eagle-import:LED-0603")
      (libsource (lib "eagle-import") (part "LED0603"))
    )
    (comp (ref "D11")
      (value "BLUE")
      (footprint "eagle-import:LED-0603")
      (libsource (lib "eagle-import") (part "LED0603"))
    )
    (comp (ref "D12")
      (value "BLUE")
      (footprint "eagle-import:LED-0603")
      (libsource (lib "eagle-import") (part "LED0603"))
    )
    (comp (ref "D13")
      (value "BLUE")
      (footprint "eagle-import:LED-0603")
      (libsource (lib "eagle-import") (part "LED0603"))
    )
    (comp (ref "P10")
      (value "SCHA5B0200")
      (footprint "eagle-import:SCHA5B0200")
      (libsource (lib "eagle-import") (part "SCHA5B0200"))
    )
    (comp (ref "R2")
      (value "1.5K,1%")
      (footprint "eagle-import:0402-RES")
      (libsource (lib "eagle-import") (part "RESISTOR0402-RES"))
    )
    (comp (ref "R23")
      (value "1.5K,1%")
      (footprint "eagle-import:0402-RES")
      (libsource (lib "eagle-import") (part "RESISTOR0402-RES"))
    )
    (comp (ref "R24")
      (value "4.75K,1%")
      (footprint "eagle-import:0402-RES")
      (libsource (lib "eagle-import") (part "RESISTOR0402-RES"))
    )
    (comp (ref "R58")
      (value "1.5K,1%")
      (footprint "eagle-import:0402-RES")
      (libsource (lib "eagle-import") (part "RESISTOR0402-RES"))
    )
    (comp (ref "R59")
      (value "4.7K,1%")
      (footprint "eagle-import:0402-RES")
      (libsource (lib "eagle-import") (part "RESISTOR0402-RES"))
    )
    (comp (ref "R60")
      (value "10K,1%")
      (footprint "eagle-import:0402-RES")
      (libsource (lib "eagle-import") (part "RESISTOR0402-RES"))
    )
    (comp (ref "R61")
      (value "261")
      (footprint "eagle-import:0402-RES")
      (libsource (lib "eagle-import") (part "RESISTOR0402-RES"))
    )
    (comp (ref "R62")
      (value "261")
      (footprint "eagle-import:0402-RES")
      (libsource (lib "eagle-import") (part "RESISTOR0402-RES"))
    )
    (comp (ref "R63")
      (value "261")
      (footprint "eagle-import:0402-RES")
      (libsource (lib "eagle-import") (part "RESISTOR0402-RES"))
    )
    (comp (ref "R64")
      (value "261")
      (footprint "eagle-import:0402-RES")
      (libsource (lib "eagle-import") (part "RESISTOR0402-RES"))
    )
    (comp (ref "R65")
      (value "10K,1%")
      (footprint "eagle-import:0402-RES")
      (libsource (lib "eagle-import") (part "RESISTOR0402-RES"))
    )
    (comp (ref "R66")
      (value "10K,1%")
      (footprint "eagle-import:0402-RES")
      (libsource (lib "eagle-import") (part "RESISTOR0402-RES"))
    )
    (comp (ref "R67")
      (value "10K,1%")
      (footprint "eagle-import:0402-RES")
      (libsource (lib "eagle-import") (part "RESISTOR0402-RES"))
    )
    (comp (ref "R68")
      (value "10K,1%")
      (footprint "eagle-import:0402-RES")
      (libsource (lib "eagle-import") (part "RESISTOR0402-RES"))
    )
    (comp (ref "R69")
      (value "10K,1%")
      (footprint "eagle-import:0402-RES")
      (libsource (lib "eagle-import") (part "RESISTOR0402-RES"))
    )
    (comp (ref "R70")
      (value "10K,1%")
      (footprint "eagle-import:0402-RES")
      (libsource (lib "eagle-import") (part "RESISTOR0402-RES"))
    )
    (comp (ref "R71")
      (value "10K,1%")
      (footprint "eagle-import:0402-RES")
      (libsource (lib "eagle-import") (part "RESISTOR0402-RES"))
    )
    (comp (ref "R72")
      (value "33")
      (footprint "eagle-import:0402-RES")
      (libsource (lib "eagle-import") (part "RESISTOR0402-RES"))
    )
    (comp (ref "R73")
      (value "33")
      (footprint "eagle-import:0402-RES")
      (libsource (lib "eagle-import") (part "RESISTOR0402-RES"))
    )
    (comp (ref "R74")
      (value "0")
      (footprint "eagle-import:0402-RES")
      (libsource (lib "eagle-import") (part "RESISTOR0402-RES"))
    )
    (comp (ref "R75")
      (value "0")
      (footprint "eagle-import:0402-RES")
      (libsource (lib "eagle-import") (part "RESISTOR0402-RES"))
    )
    (comp (ref "R76")
      (value "33")
      (footprint "eagle-import:0402-RES")
      (libsource (lib "eagle-import") (part "RESISTOR0402-RES"))
    )
    (comp (ref "R77")
      (value "33")
      (footprint "eagle-import:0402-RES")
      (libsource (lib "eagle-import") (part "RESISTOR0402-RES"))
    )
    (comp (ref "R78")
      (value "33")
      (footprint "eagle-import:0402-RES")
      (libsource (lib "eagle-import") (part "RESISTOR0402-RES"))
    )
    (comp (ref "R79")
      (value "33")
      (footprint "eagle-import:0402-RES")
      (libsource (lib "eagle-import") (part "RESISTOR0402-RES"))
    )
    (comp (ref "R80")
      (value "0")
      (footprint "eagle-import:0402-RES")
      (libsource (lib "eagle-import") (part "RESISTOR0402-RES"))
    )
    (comp (ref "R81")
      (value "0")
      (footprint "eagle-import:0402-RES")
      (libsource (lib "eagle-import") (part "RESISTOR0402-RES"))
    )
    (comp (ref "R82")
      (value "33")
      (footprint "eagle-import:0402-RES")
      (libsource (lib "eagle-import") (part "RESISTOR0402-RES"))
    )
    (comp (ref "R83")
      (value "33")
      (footprint "eagle-import:0402-RES")
      (libsource (lib "eagle-import") (part "RESISTOR0402-RES"))
    )
    (comp (ref "R84")
      (value "10K,1%")
      (footprint "eagle-import:0402-RES")
      (libsource (lib "eagle-import") (part "RESISTOR0402-RES"))
    )
    (comp (ref "R85")
      (value "10K,1%")
      (footprint "eagle-import:0402-RES")
      (libsource (lib "eagle-import") (part "RESISTOR0402-RES"))
    )
    (comp (ref "R86")
      (value "10K,1%")
      (footprint "eagle-import:0402-RES")
      (libsource (lib "eagle-import") (part "RESISTOR0402-RES"))
    )
    (comp (ref "R87")
      (value "10K,1%")
      (footprint "eagle-import:0402-RES")
      (libsource (lib "eagle-import") (part "RESISTOR0402-RES"))
    )
    (comp (ref "R88")
      (value "10K,1%")
      (footprint "eagle-import:0402-RES")
      (libsource (lib "eagle-import") (part "RESISTOR0402-RES"))
    )
    (comp (ref "R89")
      (value "10K,1%")
      (footprint "eagle-import:0402-RES")
      (libsource (lib "eagle-import") (part "RESISTOR0402-RES"))
    )
    (comp (ref "R90")
      (value "10K,1%")
      (footprint "eagle-import:0402-RES")
      (libsource (lib "eagle-import") (part "RESISTOR0402-RES"))
    )
    (comp (ref "R91")
      (value "10K,1%")
      (footprint "eagle-import:0402-RES")
      (libsource (lib "eagle-import") (part "RESISTOR0402-RES"))
    )
    (comp (ref "R92")
      (value "10K,1%")
      (footprint "eagle-import:0402-RES")
      (libsource (lib "eagle-import") (part "RESISTOR0402-RES"))
    )
    (comp (ref "R93")
      (value "10K,1%")
      (footprint "eagle-import:0402-RES")
      (libsource (lib "eagle-import") (part "RESISTOR0402-RES"))
    )
    (comp (ref "R94")
      (value "10K,1%")
      (footprint "eagle-import:0402-RES")
      (libsource (lib "eagle-import") (part "RESISTOR0402-RES"))
    )
    (comp (ref "R95")
      (value "33")
      (footprint "eagle-import:0402-RES")
      (libsource (lib "eagle-import") (part "RESISTOR0402-RES"))
    )
    (comp (ref "R96")
      (value "33")
      (footprint "eagle-import:0402-RES")
      (libsource (lib "eagle-import") (part "RESISTOR0402-RES"))
    )
    (comp (ref "R97")
      (value "33")
      (footprint "eagle-import:0402-RES")
      (libsource (lib "eagle-import") (part "RESISTOR0402-RES"))
    )
    (comp (ref "R98")
      (value "33")
      (footprint "eagle-import:0402-RES")
      (libsource (lib "eagle-import") (part "RESISTOR0402-RES"))
    )
    (comp (ref "R99")
      (value "33")
      (footprint "eagle-import:0402-RES")
      (libsource (lib "eagle-import") (part "RESISTOR0402-RES"))
    )
    (comp (ref "R100")
      (value "33")
      (footprint "eagle-import:0402-RES")
      (libsource (lib "eagle-import") (part "RESISTOR0402-RES"))
    )
    (comp (ref "R101")
      (value "33")
      (footprint "eagle-import:0402-RES")
      (libsource (lib "eagle-import") (part "RESISTOR0402-RES"))
    )
    (comp (ref "R102")
      (value "33")
      (footprint "eagle-import:0402-RES")
      (libsource (lib "eagle-import") (part "RESISTOR0402-RES"))
    )
    (comp (ref "R103")
      (value "33")
      (footprint "eagle-import:0402-RES")
      (libsource (lib "eagle-import") (part "RESISTOR0402-RES"))
    )
    (comp (ref "R104")
      (value "33")
      (footprint "eagle-import:0402-RES")
      (libsource (lib "eagle-import") (part "RESISTOR0402-RES"))
    )
    (comp (ref "TP1")
      (value "TPSQB1,27")
      (footprint "eagle-import:B1,27")
      (libsource (lib "eagle-import") (part "TPSQB1,27"))
    )
    (comp (ref "TP2")
      (value "TPSQB1,27")
      (footprint "eagle-import:B1,27")
      (libsource (lib "eagle-import") (part "TPSQB1,27"))
    )
    (comp (ref "TP3")
      (value "TPSQB1,27")
      (footprint "eagle-import:B1,27")
      (libsource (lib "eagle-import") (part "TPSQB1,27"))
    )
    (comp (ref "TP4")
      (value "TPSQB1,27")
      (footprint "eagle-import:B1,27")
      (libsource (lib "eagle-import") (part "TPSQB1,27"))
    )
    (comp (ref "TP5")
      (value "TPSQB1,27")
      (footprint "eagle-import:B1,27")
      (libsource (lib "eagle-import") (part "TPSQB1,27"))
    )
    (comp (ref "TP6")
      (value "TPSQB1,27")
      (footprint "eagle-import:B1,27")
      (libsource (lib "eagle-import") (part "TPSQB1,27"))
    )
    (comp (ref "TP7")
      (value "TPSQB1,27")
      (footprint "eagle-import:B1,27")
      (libsource (lib "eagle-import") (part "TPSQB1,27"))
    )
    (comp (ref "TP8")
      (value "TPSQB1,27")
      (footprint "eagle-import:B1,27")
      (libsource (lib "eagle-import") (part "TPSQB1,27"))
    )
    (comp (ref "TP9")
      (value "TPSQB1,27")
      (footprint "eagle-import:B1,27")
      (libsource (lib "eagle-import") (part "TPSQB1,27"))
    )
    (comp (ref "TP10")
      (value "TPSQB1,27")
      (footprint "eagle-import:B1,27")
      (libsource (lib "eagle-import") (part "TPSQB1,27"))
    )
    (comp (ref "TP11")
      (value "TPSQB1,27")
      (footprint "eagle-import:B1,27")
      (libsource (lib "eagle-import") (part "TPSQB1,27"))
    )
    (comp (ref "TP12")
      (value "TPSQB1,27")
      (footprint "eagle-import:B1,27")
      (libsource (lib "eagle-import") (part "TPSQB1,27"))
    )
    (comp (ref "TP13")
      (value "TPSQB1,27")
      (footprint "eagle-import:B1,27")
      (libsource (lib "eagle-import") (part "TPSQB1,27"))
    )
    (comp (ref "TP14")
      (value "TPSQB1,27")
      (footprint "eagle-import:B1,27")
      (libsource (lib "eagle-import") (part "TPSQB1,27"))
    )
    (comp (ref "TP15")
      (value "TPSQB1,27")
      (footprint "eagle-import:B1,27")
      (libsource (lib "eagle-import") (part "TPSQB1,27"))
    )
    (comp (ref "TP16")
      (value "TPSQB1,27")
      (footprint "eagle-import:B1,27")
      (libsource (lib "eagle-import") (part "TPSQB1,27"))
    )
    (comp (ref "TP17")
      (value "TPSQB1,27")
      (footprint "eagle-import:B1,27")
      (libsource (lib "eagle-import") (part "TPSQB1,27"))
    )
    (comp (ref "TP18")
      (value "TPSQB1,27")
      (footprint "eagle-import:B1,27")
      (libsource (lib "eagle-import") (part "TPSQB1,27"))
    )
    (comp (ref "TP19")
      (value "TPSQB1,27")
      (footprint "eagle-import:B1,27")
      (libsource (lib "eagle-import") (part "TPSQB1,27"))
    )
    (comp (ref "TP20")
      (value "TPSQB1,27")
      (footprint "eagle-import:B1,27")
      (libsource (lib "eagle-import") (part "TPSQB1,27"))
    )
    (comp (ref "U5")
      (value "24LC_32AT-I/OT")
      (footprint "eagle-import:SOT95P290X145-5N")
      (fields (field (name "MPN") "24LC32AT-I/OT"))
      (libsource (lib "eagle-import") (part "24LC_32AT-I/OT"))
    )
    (comp (ref "U6")
      (value "SN74LVC1G07_DCK_5")
      (footprint "eagle-import:DCK5")
      (fields
        (field (name "GENERIC_PART_NUMBER") "SN74LVC1G07")
        (field (name "MANUFACTURER") "Texas Instruments")
        (field (name "MANUFACTURER_PART_NUMBER") "sn74lvc1g07_dck_5")
      )
      (libsource (lib "eagle-import") (part "SN74LVC1G07_DCK_5"))
    )
    (comp (ref "U8")
      (value "MTFC4GLDEA")
      (footprint "eagle-import:MTFC4GLDEA")
      (libsource (lib "eagle-import") (part "MTFC4GLDEA"))
    )
    (comp (ref "Y1")
      (value "CM200C-32.768KAZF-UT")
      (footprint "eagle-import:CM200C-32.768KAZF-UT")
      (libsource (lib "eagle-import") (part "CM200C-32.768KAZF-UT"))
    )
    (comp (ref "Y2")
      (value "445C33D24M00000")
      (footprint "eagle-import:445C33D24M00000")
      (libsource (lib "eagle-import") (part "445C33D24M00000"))
    )
    (comp (ref "R158")
      (value "10K,1%")
      (footprint "eagle-import:0402-RES")
      (libsource (lib "eagle-import") (part "RESISTOR0402-RES"))
    )
  )
  (nets
    (net (code "1") (name "3.3V") (class "Default")
      (node (ref "BMP") (pin "2") (pinfunction "VDD_2") (pintype "power_in"))
      (node (ref "BMP") (pin "3") (pinfunction "VDDIO_3") (pintype "power_in"))
      (node (ref "C13") (pin "1") (pinfunction "1_1") (pintype "passive"))
      (node (ref "C16") (pin "1") (pinfunction "1_1") (pintype "passive"))
      (node (ref "C2") (pin "2") (pinfunction "2_2") (pintype "passive"))
      (node (ref "C8") (pin "1") (pinfunction "1_1") (pintype "passive"))
      (node (ref "C9") (pin "2") (pinfunction "2_2") (pintype "passive"))
      (node (ref "DSM2") (pin "1") (pinfunction "1_1") (pintype "bidirectional"))
      (node (ref "E1") (pin "2") (pinfunction "2_2") (pintype "bidirectional"))
      (node (ref "E2") (pin "2") (pinfunction "2_2") (pintype "bidirectional"))
      (node (ref "E3") (pin "2") (pinfunction "2_2") (pintype "bidirectional"))
      (node (ref "E4") (pin "2") (pinfunction "2_2") (pintype "bidirectional"))
      (node (ref "H1") (pin "20") (pinfunction "VCC_20") (pintype "bidirectional"))
      (node (ref "H2") (pin "20") (pinfunction "VCC_20") (pintype "bidirectional"))
      (node (ref "I2C1") (pin "2") (pinfunction "2_2") (pintype "bidirectional"))
      (node (ref "IMU") (pin "1") (pinfunction "RESV_1") (pintype "bidirectional"))
      (node (ref "IMU") (pin "13") (pinfunction "VDD_13") (pintype "bidirectional"))
      (node (ref "IMU") (pin "22") (pinfunction "NCS_22") (pintype "bidirectional"))
      (node (ref "IMU") (pin "8") (pinfunction "VDDIO_8") (pintype "bidirectional"))
      (node (ref "PWR") (pin "3") (pinfunction "3_3") (pintype "bidirectional"))
      (node (ref "R10") (pin "1") (pinfunction "1_1") (pintype "passive"))
      (node (ref "R11") (pin "2") (pinfunction "2_2") (pintype "passive"))
      (node (ref "R12") (pin "2") (pinfunction "2_2") (pintype "passive"))
      (node (ref "R13") (pin "1") (pinfunction "1_1") (pintype "passive"))
      (node (ref "R15") (pin "2") (pinfunction "2_2") (pintype "passive"))
      (node (ref "R16") (pin "2") (pinfunction "2_2") (pintype "passive"))
      (node (ref "R17") (pin "2") (pinfunction "2_2") (pintype "passive"))
      (node (ref "R18") (pin "2") (pinfunction "2_2") (pintype "passive"))
      (node (ref "R20") (pin "2") (pinfunction "2_2") (pintype "passive"))
      (node (ref "R26") (pin "2") (pinfunction "2_2") (pintype "passive"))
      (node (ref "R35") (pin "2") (pinfunction "2_2") (pintype "passive"))
      (node (ref "R9") (pin "2") (pinfunction "2_2") (pintype "passive"))
      (node (ref "SPI1.1") (pin "2") (pinfunction "2_2") (pintype "bidirectional"))
      (node (ref "SPI1.2") (pin "2") (pinfunction "2_2") (pintype "bidirectional"))
      (node (ref "UART0") (pin "2") (pinfunction "2_2") (pintype "bidirectional"))
      (node (ref "UART1") (pin "2") (pinfunction "2_2") (pintype "bidirectional"))
      (node (ref "UART5") (pin "2") (pinfunction "2_2") (pintype "bidirectional"))
    )
    (net (code "2") (name "5.0V") (class "Default")
      (node (ref "5VREG") (pin "3") (pinfunction "FB_3") (pintype "power_in"))
      (node (ref "C5") (pin "1") (pinfunction "1_1") (pintype "passive"))
      (node (ref "GPS") (pin "5") (pinfunction "5_5") (pintype "bidirectional"))
      (node (ref "L1") (pin "2") (pinfunction "2_2") (pintype "passive"))
      (node (ref "PWR") (pin "4") (pinfunction "4_4") (pintype "bidirectional"))
      (node (ref "R152") (pin "1") (pinfunction "1_1") (pintype "passive"))
      (node (ref "SIP") (pin "Y5") (pinfunction "VIN_AC_0_Y5") (pintype "power_in"))
      (node (ref "SIP") (pin "Y6") (pinfunction "VIN_AC_1_Y6") (pintype "power_in"))
    )
    (net (code "3") (name "AIN0") (class "Default")
      (node (ref "ADC") (pin "3") (pinfunction "3_3") (pintype "bidirectional"))
      (node (ref "R105") (pin "1") (pinfunction "1_1") (pintype "passive"))
    )
    (net (code "4") (name "AIN1") (class "Default")
      (node (ref "ADC") (pin "4") (pinfunction "4_4") (pintype "bidirectional"))
      (node (ref "R106") (pin "1") (pinfunction "1_1") (pintype "passive"))
    )
    (net (code "5") (name "AIN2") (class "Default")
      (node (ref "ADC") (pin "5") (pinfunction "5_5") (pintype "bidirectional"))
      (node (ref "R107") (pin "1") (pinfunction "1_1") (pintype "passive"))
    )
    (net (code "6") (name "AIN3") (class "Default")
      (node (ref "ADC") (pin "6") (pinfunction "6_6") (pintype "bidirectional"))
      (node (ref "R108") (pin "1") (pinfunction "1_1") (pintype "passive"))
    )
    (net (code "7") (name "BATT_MID") (class "Default")
      (node (ref "LIPO") (pin "P$2") (pinfunction "2_P$2") (pintype "passive"))
      (node (ref "R27") (pin "1") (pinfunction "1_1") (pintype "passive"))
      (node (ref "R30") (pin "1") (pinfunction "1_1") (pintype "passive"))
      (node (ref "R44") (pin "1") (pinfunction "1_1") (pintype "passive"))
    )
    (net (code "8") (name "BATT_MINUS") (class "Default")
      (node (ref "BAL") (pin "5") (pinfunction "GND_5") (pintype "bidirectional"))
      (node (ref "BAL") (pin "6") (pinfunction "CB_EN_6") (pintype "bidirectional"))
      (node (ref "C1") (pin "2") (pinfunction "2_2") (pintype "passive"))
      (node (ref "C15") (pin "1") (pinfunction "1_1") (pintype "passive"))
      (node (ref "C18") (pin "1") (pinfunction "1_1") (pintype "passive"))
      (node (ref "C19") (pin "2") (pinfunction "2_2") (pintype "passive"))
      (node (ref "LIPO") (pin "P$3") (pinfunction "3_P$3") (pintype "passive"))
      (node (ref "PROT") (pin "2") (pinfunction "VM_2") (pintype "bidirectional"))
      (node (ref "PROT") (pin "6") (pinfunction "VSS_6") (pintype "bidirectional"))
      (node (ref "Q3") (pin "1") (pinfunction "S_1") (pintype "passive"))
      (node (ref "Q3") (pin "2") (pinfunction "S_2") (pintype "passive"))
      (node (ref "Q3") (pin "3") (pinfunction "S_3") (pintype "passive"))
    )
    (net (code "9") (name "CHG_EN") (class "Default")
      (node (ref "CHGIC") (pin "6") (pinfunction "EN_6") (pintype "bidirectional"))
      (node (ref "R7") (pin "2") (pinfunction "2_2") (pintype "passive"))
      (node (ref "R8") (pin "1") (pinfunction "1_1") (pintype "passive"))
    )
    (net (code "10") (name "DO") (class "Default")
      (node (ref "PROT") (pin "1") (pinfunction "DO_1") (pintype "bidirectional"))
      (node (ref "Q3") (pin "4") (pinfunction "G_4") (pintype "passive"))
    )
    (net (code "11") (name "GND") (class "Default")
      (node (ref "5VREG") (pin "4") (pinfunction "SD_4") (pintype "input"))
      (node (ref "5VREG") (pin "5") (pinfunction "GND_5") (pintype "power_in"))
      (node (ref "5VREG") (pin "6") (pinfunction "GND1_6") (pintype "input"))
      (node (ref "5VREG") (pin "7") (pinfunction "GND2_7") (pintype "passive"))
      (node (ref "5VREG") (pin "8") (pinfunction "GND3_8") (pintype "power_in"))
      (node (ref "6V_REG") (pin "3") (pinfunction "GND_3") (pintype "bidirectional"))
      (node (ref "ADC") (pin "1") (pinfunction "1_1") (pintype "bidirectional"))
      (node (ref "BMP") (pin "7") (pinfunction "GND_7") (pintype "power_in"))
      (node (ref "BOOT") (pin "2") (pinfunction "2_2") (pintype "passive"))
      (node (ref "C10") (pin "1") (pinfunction "1_1") (pintype "passive"))
      (node (ref "C11") (pin "-") (pinfunction "-_-") (pintype "passive"))
      (node (ref "C12") (pin "2") (pinfunction "2_2") (pintype "passive"))
      (node (ref "C13") (pin "2") (pinfunction "2_2") (pintype "passive"))
      (node (ref "C16") (pin "2") (pinfunction "2_2") (pintype "passive"))
      (node (ref "C2") (pin "1") (pinfunction "1_1") (pintype "passive"))
      (node (ref "C20") (pin "1") (pinfunction "1_1") (pintype "passive"))
      (node (ref "C21") (pin "1") (pinfunction "1_1") (pintype "passive"))
      (node (ref "C23") (pin "1") (pinfunction "1_1") (pintype "passive"))
      (node (ref "C24") (pin "1") (pinfunction "1_1") (pintype "passive"))
      (node (ref "C25") (pin "2") (pinfunction "2_2") (pintype "passive"))
      (node (ref "C26") (pin "2") (pinfunction "2_2") (pintype "passive"))
      (node (ref "C27") (pin "2") (pinfunction "2_2") (pintype "passive"))
      (node (ref "C28") (pin "2") (pinfunction "2_2") (pintype "passive"))
      (node (ref "C3") (pin "2") (pinfunction "2_2") (pintype "passive"))
      (node (ref "C33") (pin "2") (pinfunction "2_2") (pintype "passive"))
      (node (ref "C34") (pin "1") (pinfunction "1_1") (pintype "passive"))
      (node (ref "C35") (pin "1") (pinfunction "1_1") (pintype "passive"))
      (node (ref "C36") (pin "1") (pinfunction "1_1") (pintype "passive"))
      (node (ref "C37") (pin "2") (pinfunction "2_2") (pintype "passive"))
      (node (ref "C38") (pin "2") (pinfunction "2_2") (pintype "passive"))
      (node (ref "C39") (pin "2") (pinfunction "2_2") (pintype "passive"))
      (node (ref "C4") (pin "1") (pinfunction "1_1") (pintype "passive"))
      (node (ref "C40") (pin "2") (pinfunction "2_2") (pintype "passive"))
      (node (ref "C41") (pin "2") (pinfunction "2_2") (pintype "passive"))
      (node (ref "C45") (pin "2") (pinfunction "2_2") (pintype "passive"))
      (node (ref "C46") (pin "2") (pinfunction "2_2") (pintype "passive"))
      (node (ref "C5") (pin "2") (pinfunction "2_2") (pintype "passive"))
      (node (ref "C50") (pin "-") (pinfunction "2_-") (pintype "passive"))
      (node (ref "C6") (pin "2") (pinfunction "2_2") (pintype "passive"))
      (node (ref "C7") (pin "2") (pinfunction "2_2") (pintype "passive"))
      (node (ref "C8") (pin "2") (pinfunction "2_2") (pintype "passive"))
      (node (ref "C9") (pin "1") (pinfunction "1_1") (pintype "passive"))
      (node (ref "CHGIC") (pin "16") (pinfunction "PGND_16") (pintype "bidirectional"))
      (node (ref "CHGIC") (pin "8") (pinfunction "AGND_8") (pintype "bidirectional"))
      (node (ref "D1") (pin "A") (pinfunction "A_A") (pintype "passive"))
      (node (ref "D9") (pin "A") (pinfunction "A_A") (pintype "passive"))
      (node (ref "DSM2") (pin "2") (pinfunction "2_2") (pintype "bidirectional"))
      (node (ref "E1") (pin "1") (pinfunction "1_1") (pintype "bidirectional"))
      (node (ref "E2") (pin "1") (pinfunction "1_1") (pintype "bidirectional"))
      (node (ref "E3") (pin "1") (pinfunction "1_1") (pintype "bidirectional"))
      (node (ref "E4") (pin "1") (pinfunction "1_1") (pintype "bidirectional"))
      (node (ref "GPS") (pin "2") (pinfunction "2_2") (pintype "bidirectional"))
      (node (ref "GPS") (pin "6") (pinfunction "6_6") (pintype "bidirectional"))
      (node (ref "H1") (pin "10") (pinfunction "PGND2_10") (pintype "bidirectional"))
      (node (ref "H1") (pin "18") (pinfunction "GND_18") (pintype "bidirectional"))
      (node (ref "H1") (pin "3") (pinfunction "PGND1_3") (pintype "bidirectional"))
      (node (ref "H1") (pin "4") (pinfunction "PGND1_4") (pintype "bidirectional"))
      (node (ref "H1") (pin "9") (pinfunction "PGND2_9") (pintype "bidirectional"))
      (node (ref "H2") (pin "10") (pinfunction "PGND2_10") (pintype "bidirectional"))
      (node (ref "H2") (pin "18") (pinfunction "GND_18") (pintype "bidirectional"))
      (node (ref "H2") (pin "3") (pinfunction "PGND1_3") (pintype "bidirectional"))
      (node (ref "H2") (pin "4") (pinfunction "PGND1_4") (pintype "bidirectional"))
      (node (ref "H2") (pin "9") (pinfunction "PGND2_9") (pintype "bidirectional"))
      (node (ref "HOST") (pin "S1") (pinfunction "SH0_S1") (pintype "bidirectional"))
      (node (ref "HOST") (pin "S2") (pinfunction "SH1_S2") (pintype "bidirectional"))
      (node (ref "I2C1") (pin "1") (pinfunction "1_1") (pintype "bidirectional"))
      (node (ref "IMU") (pin "18") (pinfunction "GND_18") (pintype "bidirectional"))
      (node (ref "IMU") (pin "20") (pinfunction "RESV_20") (pintype "bidirectional"))
      (node (ref "IMU") (pin "25") (pinfunction "PAD_25") (pintype "bidirectional"))
      (node (ref "IMU") (pin "9") (pinfunction "AD0/SDO_9") (pintype "bidirectional"))
      (node (ref "JACK") (pin "2") (pinfunction "2_2") (pintype "passive"))
      (node (ref "JACK") (pin "3") (pinfunction "3_3") (pintype "passive"))
      (node (ref "L4") (pin "1") (pinfunction "1_1") (pintype "passive"))
      (node (ref "MODE") (pin "1") (pinfunction "1_1") (pintype "passive"))
      (node (ref "P10") (pin "11") (pinfunction "GND3_11") (pintype "bidirectional"))
      (node (ref "P10") (pin "12") (pinfunction "GND4_12") (pintype "bidirectional"))
      (node (ref "P10") (pin "13") (pinfunction "GND5_13") (pintype "bidirectional"))
      (node (ref "P10") (pin "14") (pinfunction "GND6_14") (pintype "bidirectional"))
      (node (ref "P10") (pin "15") (pinfunction "GND7_15") (pintype "bidirectional"))
      (node (ref "P10") (pin "16") (pinfunction "GND8_16") (pintype "bidirectional"))
      (node (ref "P10") (pin "6") (pinfunction "VSS_6") (pintype "bidirectional"))
      (node (ref "P10") (pin "9") (pinfunction "GND_9") (pintype "bidirectional"))
      (node (ref "PAUSE") (pin "1") (pinfunction "1_1") (pintype "passive"))
      (node (ref "POWER") (pin "1") (pinfunction "1_1") (pintype "passive"))
      (node (ref "PWR") (pin "1") (pinfunction "1_1") (pintype "bidirectional"))
      (node (ref "PWR") (pin "2") (pinfunction "2_2") (pintype "bidirectional"))
      (node (ref "Q3") (pin "5") (pinfunction "D_5") (pintype "passive"))
      (node (ref "Q3") (pin "6") (pinfunction "D_6") (pintype "passive"))
      (node (ref "Q3") (pin "7") (pinfunction "D_7") (pintype "passive"))
      (node (ref "Q3") (pin "8") (pinfunction "D_8") (pintype "passive"))
      (node (ref "R110") (pin "2") (pinfunction "2_2") (pintype "passive"))
      (node (ref "R113") (pin "1") (pinfunction "1_1") (pintype "passive"))
      (node (ref "R115") (pin "1") (pinfunction "1_1") (pintype "passive"))
      (node (ref "R125") (pin "1") (pinfunction "1_1") (pintype "passive"))
      (node (ref "R127") (pin "1") (pinfunction "1_1") (pintype "passive"))
      (node (ref "R129") (pin "1") (pinfunction "1_1") (pintype "passive"))
      (node (ref "R131") (pin "1") (pinfunction "1_1") (pintype "passive"))
      (node (ref "R133") (pin "1") (pinfunction "1_1") (pintype "passive"))
      (node (ref "R135") (pin "1") (pinfunction "1_1") (pintype "passive"))
      (node (ref "R137") (pin "1") (pinfunction "1_1") (pintype "passive"))
      (node (ref "R139") (pin "1") (pinfunction "1_1") (pintype "passive"))
      (node (ref "R14") (pin "2") (pinfunction "2_2") (pintype "passive"))
      (node (ref "R143") (pin "1") (pinfunction "1_1") (pintype "passive"))
      (node (ref "R150") (pin "2") (pinfunction "2_2") (pintype "passive"))
      (node (ref "R151") (pin "1") (pinfunction "1_1") (pintype "passive"))
      (node (ref "R158") (pin "2") (pinfunction "2_2") (pintype "passive"))
      (node (ref "R21") (pin "2") (pinfunction "2_2") (pintype "passive"))
      (node (ref "R22") (pin "2") (pinfunction "2_2") (pintype "passive"))
      (node (ref "R24") (pin "2") (pinfunction "2_2") (pintype "passive"))
      (node (ref "R25") (pin "2") (pinfunction "2_2") (pintype "passive"))
      (node (ref "R29") (pin "2") (pinfunction "2_2") (pintype "passive"))
      (node (ref "R31") (pin "2") (pinfunction "2_2") (pintype "passive"))
      (node (ref "R32") (pin "2") (pinfunction "2_2") (pintype "passive"))
      (node (ref "R33") (pin "2") (pinfunction "2_2") (pintype "passive"))
      (node (ref "R46") (pin "1") (pinfunction "1_1") (pintype "passive"))
      (node (ref "R47") (pin "1") (pinfunction "1_1") (pintype "passive"))
      (node (ref "R48") (pin "1") (pinfunction "1_1") (pintype "passive"))
      (node (ref "R50") (pin "2") (pinfunction "2_2") (pintype "passive"))
      (node (ref "R51") (pin "2") (pinfunction "2_2") (pintype "passive"))
      (node (ref "R52") (pin "2") (pinfunction "2_2") (pintype "passive"))
      (node (ref "R53") (pin "2") (pinfunction "2_2") (pintype "passive"))
      (node (ref "R54") (pin "1") (pinfunction "1_1") (pintype "passive"))
      (node (ref "R55") (pin "1") (pinfunction "1_1") (pintype "passive"))
      (node (ref "R56") (pin "1") (pinfunction "1_1") (pintype "passive"))
      (node (ref "R57") (pin "1") (pinfunction "1_1") (pintype "passive"))
      (node (ref "R59") (pin "1") (pinfunction "1_1") (pintype "passive"))
      (node (ref "R6") (pin "1") (pinfunction "1_1") (pintype "passive"))
      (node (ref "R61") (pin "1") (pinfunction "1_1") (pintype "passive"))
      (node (ref "R62") (pin "1") (pinfunction "1_1") (pintype "passive"))
      (node (ref "R63") (pin "1") (pinfunction "1_1") (pintype "passive"))
      (node (ref "R64") (pin "1") (pinfunction "1_1") (pintype "passive"))
      (node (ref "R8") (pin "2") (pinfunction "2_2") (pintype "passive"))
      (node (ref "RESET") (pin "1") (pinfunction "1_1") (pintype "passive"))
      (node (ref "SIP") (pin "A1") (pinfunction "DGND1_A1") (pintype "bidirectional"))
      (node (ref "SIP") (pin "A18") (pinfunction "DGND2_A18") (pintype "bidirectional"))
      (node (ref "SIP") (pin "E19") (pinfunction "DGND3_E19") (pintype "bidirectional"))
      (node (ref "SIP") (pin "E20") (pinfunction "DGND4_E20") (pintype "bidirectional"))
      (node (ref "SIP") (pin "F19") (pinfunction "DGND6_F19") (pintype "bidirectional"))
      (node (ref "SIP") (pin "F8") (pinfunction "DGND5_F8") (pintype "bidirectional"))
      (node (ref "SIP") (pin "G11") (pinfunction "DGND9_G11") (pintype "bidirectional"))
      (node (ref "SIP") (pin "G12") (pinfunction "DGND10_G12") (pintype "bidirectional"))
      (node (ref "SIP") (pin "G19") (pinfunction "DGND11_G19") (pintype "bidirectional"))
      (node (ref "SIP") (pin "G8") (pinfunction "DGND7_G8") (pintype "bidirectional"))
      (node (ref "SIP") (pin "G9") (pinfunction "DGND8_G9") (pintype "bidirectional"))
      (node (ref "SIP") (pin "H10") (pinfunction "DGND16_H10") (pintype "bidirectional"))
      (node (ref "SIP") (pin "H12") (pinfunction "DGND17_H12") (pintype "bidirectional"))
      (node (ref "SIP") (pin "H19") (pinfunction "DGND18_H19") (pintype "bidirectional"))
      (node (ref "SIP") (pin "H6") (pinfunction "DGND12_H6") (pintype "bidirectional"))
      (node (ref "SIP") (pin "H7") (pinfunction "DGND13_H7") (pintype "bidirectional"))
      (node (ref "SIP") (pin "H8") (pinfunction "DGND14_H8") (pintype "bidirectional"))
      (node (ref "SIP") (pin "H9") (pinfunction "DGND15_H9") (pintype "bidirectional"))
      (node (ref "SIP") (pin "J10") (pinfunction "DGND23_J10") (pintype "bidirectional"))
      (node (ref "SIP") (pin "J11") (pinfunction "DGND24_J11") (pintype "bidirectional"))
      (node (ref "SIP") (pin "J19") (pinfunction "DGND25_J19") (pintype "bidirectional"))
      (node (ref "SIP") (pin "J20") (pinfunction "DGND26_J20") (pintype "bidirectional"))
      (node (ref "SIP") (pin "J6") (pinfunction "DGND19_J6") (pintype "bidirectional"))
      (node (ref "SIP") (pin "J7") (pinfunction "DGND20_J7") (pintype "bidirectional"))
      (node (ref "SIP") (pin "J8") (pinfunction "DGND21_J8") (pintype "bidirectional"))
      (node (ref "SIP") (pin "J9") (pinfunction "DGND22_J9") (pintype "bidirectional"))
      (node (ref "SIP") (pin "K10") (pinfunction "DGND29_K10") (pintype "bidirectional"))
      (node (ref "SIP") (pin "K11") (pinfunction "DGND30_K11") (pintype "bidirectional"))
      (node (ref "SIP") (pin "K19") (pinfunction "DGND31_K19") (pintype "bidirectional"))
      (node (ref "SIP") (pin "K7") (pinfunction "DGND27_K7") (pintype "bidirectional"))
      (node (ref "SIP") (pin "K9") (pinfunction "DGND28_K9") (pintype "bidirectional"))
      (node (ref "SIP") (pin "L10") (pinfunction "DGND32_L10") (pintype "bidirectional"))
      (node (ref "SIP") (pin "L11") (pinfunction "DGND33_L11") (pintype "bidirectional"))
      (node (ref "SIP") (pin "L12") (pinfunction "DGND34_L12") (pintype "bidirectional"))
      (node (ref "SIP") (pin "L13") (pinfunction "DGND35_L13") (pintype "bidirectional"))
      (node (ref "SIP") (pin "L19") (pinfunction "DGND36_L19") (pintype "bidirectional"))
      (node (ref "SIP") (pin "M10") (pinfunction "DGND42_M10") (pintype "bidirectional"))
      (node (ref "SIP") (pin "M12") (pinfunction "DGND43_M12") (pintype "bidirectional"))
      (node (ref "SIP") (pin "M14") (pinfunction "DGND44_M14") (pintype "bidirectional"))
      (node (ref "SIP") (pin "M19") (pinfunction "DGND45_M19") (pintype "bidirectional"))
      (node (ref "SIP") (pin "M6") (pinfunction "DGND38_M6") (pintype "bidirectional"))
      (node (ref "SIP") (pin "M7") (pinfunction "DGND39_M7") (pintype "bidirectional"))
      (node (ref "SIP") (pin "M8") (pinfunction "DGND40_M8") (pintype "bidirectional"))
      (node (ref "SIP") (pin "M9") (pinfunction "DGND41_M9") (pintype "bidirectional"))
      (node (ref "SIP") (pin "N10") (pinfunction "DGND47_N10") (pintype "bidirectional"))
      (node (ref "SIP") (pin "N11") (pinfunction "DGND48_N11") (pintype "bidirectional"))
      (node (ref "SIP") (pin "N14") (pinfunction "DGND49_N14") (pintype "bidirectional"))
      (node (ref "SIP") (pin "N19") (pinfunction "DGND50_N19") (pintype "bidirectional"))
      (node (ref "SIP") (pin "N20") (pinfunction "DGND51_N20") (pintype "bidirectional"))
      (node (ref "SIP") (pin "N7") (pinfunction "DGND46_N7") (pintype "bidirectional"))
      (node (ref "SIP") (pin "P19") (pinfunction "DGND52_P19") (pintype "bidirectional"))
      (node (ref "SIP") (pin "P20") (pinfunction "DGND53_P20") (pintype "bidirectional"))
      (node (ref "SIP") (pin "R19") (pinfunction "DGND54_R19") (pintype "bidirectional"))
      (node (ref "SIP") (pin "R20") (pinfunction "DGND55_R20") (pintype "bidirectional"))
      (node (ref "SIP") (pin "T19") (pinfunction "DGND56_T19") (pintype "bidirectional"))
      (node (ref "SIP") (pin "T20") (pinfunction "DGND57_T20") (pintype "bidirectional"))
      (node (ref "SIP") (pin "U19") (pinfunction "DGND58_U19") (pintype "bidirectional"))
      (node (ref "SIP") (pin "V1") (pinfunction "DGND59_V1") (pintype "bidirectional"))
      (node (ref "SIP") (pin "V18") (pinfunction "DGND60_V18") (pintype "bidirectional"))
      (node (ref "SIP") (pin "V19") (pinfunction "DGND61_V19") (pintype "bidirectional"))
      (node (ref "SIP") (pin "W10") (pinfunction "DGND70_W10") (pintype "bidirectional"))
      (node (ref "SIP") (pin "W11") (pinfunction "DGND71_W11") (pintype "bidirectional"))
      (node (ref "SIP") (pin "W12") (pinfunction "DGND72_W12") (pintype "bidirectional"))
      (node (ref "SIP") (pin "W13") (pinfunction "DGND73_W13") (pintype "bidirectional"))
      (node (ref "SIP") (pin "W14") (pinfunction "DGND74_W14") (pintype "bidirectional"))
      (node (ref "SIP") (pin "W15") (pinfunction "DGND75_W15") (pintype "bidirectional"))
      (node (ref "SIP") (pin "W16") (pinfunction "DGND76_W16") (pintype "bidirectional"))
      (node (ref "SIP") (pin "W17") (pinfunction "DGND77_W17") (pintype "bidirectional"))
      (node (ref "SIP") (pin "W18") (pinfunction "DGND78_W18") (pintype "bidirectional"))
      (node (ref "SIP") (pin "W19") (pinfunction "DGND79_W19") (pintype "bidirectional"))
      (node (ref "SIP") (pin "W2") (pinfunction "DGND62_W2") (pintype "bidirectional"))
      (node (ref "SIP") (pin "W20") (pinfunction "DGND80_W20") (pintype "bidirectional"))
      (node (ref "SIP") (pin "W3") (pinfunction "DGND63_W3") (pintype "bidirectional"))
      (node (ref "SIP") (pin "W5") (pinfunction "DGND65_W5") (pintype "bidirectional"))
      (node (ref "SIP") (pin "W6") (pinfunction "DGND66_W6") (pintype "bidirectional"))
      (node (ref "SIP") (pin "W7") (pinfunction "DGND67_W7") (pintype "bidirectional"))
      (node (ref "SIP") (pin "W8") (pinfunction "DGND68_W8") (pintype "bidirectional"))
      (node (ref "SIP") (pin "W9") (pinfunction "DGND69_W9") (pintype "bidirectional"))
      (node (ref "SIP") (pin "Y10") (pinfunction "DGND83_Y10") (pintype "bidirectional"))
      (node (ref "SIP") (pin "Y12") (pinfunction "DGND84_Y12") (pintype "bidirectional"))
      (node (ref "SIP") (pin "Y15") (pinfunction "DGND85_Y15") (pintype "bidirectional"))
      (node (ref "SIP") (pin "Y18") (pinfunction "DGND86_Y18") (pintype "bidirectional"))
      (node (ref "SIP") (pin "Y7") (pinfunction "DGND82_Y7") (pintype "bidirectional"))
      (node (ref "SPI1.1") (pin "1") (pinfunction "1_1") (pintype "bidirectional"))
      (node (ref "SPI1.2") (pin "1") (pinfunction "1_1") (pintype "bidirectional"))
      (node (ref "TP12") (pin "TP") (pinfunction "TP_TP") (pintype "input"))
      (node (ref "U$1") (pin "P$13") (pinfunction "GND_P$13") (pintype "bidirectional"))
      (node (ref "U$1") (pin "P$14") (pinfunction "GND_P$14") (pintype "bidirectional"))
      (node (ref "U$1") (pin "P$15") (pinfunction "GND_P$15") (pintype "bidirectional"))
      (node (ref "U$1") (pin "P$16") (pinfunction "GND_P$16") (pintype "bidirectional"))
      (node (ref "U$1") (pin "P$17") (pinfunction "GND_P$17") (pintype "bidirectional"))
      (node (ref "U$1") (pin "P$18") (pinfunction "GND_P$18") (pintype "bidirectional"))
      (node (ref "U$1") (pin "P$23") (pinfunction "GND_P$23") (pintype "bidirectional"))
      (node (ref "U$1") (pin "P$24") (pinfunction "GND_P$24") (pintype "bidirectional"))
      (node (ref "U1") (pin "4") (pinfunction "GND_4") (pintype "power_in"))
      (node (ref "U4") (pin "4") (pinfunction "GND_4") (pintype "power_in"))
      (node (ref "U5") (pin "2") (pinfunction "VSS_2") (pintype "passive"))
      (node (ref "U6") (pin "3") (pinfunction "GND_3") (pintype "power_in"))
      (node (ref "U7") (pin "1") (pinfunction "GND_1") (pintype "power_in"))
      (node (ref "U8") (pin "C4") (pinfunction "VSSQ4_C4") (pintype "bidirectional"))
      (node (ref "U8") (pin "E7") (pinfunction "VSS2_E7") (pintype "bidirectional"))
      (node (ref "U8") (pin "G5") (pinfunction "VSS1_G5") (pintype "bidirectional"))
      (node (ref "U8") (pin "H10") (pinfunction "VSS3_H10") (pintype "bidirectional"))
      (node (ref "U8") (pin "K8") (pinfunction "VSS4_K8") (pintype "bidirectional"))
      (node (ref "U8") (pin "N2") (pinfunction "VSSQ1_N2") (pintype "bidirectional"))
      (node (ref "U8") (pin "N5") (pinfunction "VSS5_N5") (pintype "bidirectional"))
      (node (ref "U8") (pin "P4") (pinfunction "VSSQ3_P4") (pintype "bidirectional"))
      (node (ref "U8") (pin "P6") (pinfunction "VSSQ2_P6") (pintype "bidirectional"))
      (node (ref "UART0") (pin "1") (pinfunction "1_1") (pintype "bidirectional"))
      (node (ref "UART1") (pin "1") (pinfunction "1_1") (pintype "bidirectional"))
      (node (ref "UART5") (pin "1") (pinfunction "1_1") (pintype "bidirectional"))
      (node (ref "USB") (pin "GND") (pinfunction "GND_GND") (pintype "bidirectional"))
      (node (ref "USB") (pin "SHIELD1") (pinfunction "SHIELD_SHIELD1") (pintype "bidirectional"))
      (node (ref "USB") (pin "SHIELD2") (pinfunction "SHIELD_SHIELD2") (pintype "bidirectional"))
      (node (ref "USB") (pin "SHIELD3") (pinfunction "SHIELD_SHIELD3") (pintype "bidirectional"))
      (node (ref "USB") (pin "SHIELD4") (pinfunction "SHIELD_SHIELD4") (pintype "bidirectional"))
    )
    (net (code "12") (name "GNDA_ADC") (class "Default")
      (node (ref "C42") (pin "2") (pinfunction "2_2") (pintype "passive"))
      (node (ref "C43") (pin "2") (pinfunction "2_2") (pintype "passive"))
      (node (ref "C44") (pin "2") (pinfunction "2_2") (pintype "passive"))
      (node (ref "SIP") (pin "A6") (pinfunction "VSSA_ADC_0_A6") (pintype "bidirectional"))
      (node (ref "SIP") (pin "A9") (pinfunction "VSSA_ADC_1_A9") (pintype "bidirectional"))
      (node (ref "SIP") (pin "E8") (pinfunction "VSSA_ADC_2_E8") (pintype "bidirectional"))
    )
    (net (code "13") (name "I2C0_SCL") (class "Default")
      (node (ref "R23") (pin "1") (pinfunction "1_1") (pintype "passive"))
      (node (ref "SIP") (pin "C16") (pinfunction "I2C0_SCL_C16") (pintype "bidirectional"))
      (node (ref "SIP") (pin "C20") (pinfunction "PMIC_I2C_SCL_C20") (pintype "bidirectional"))
      (node (ref "U5") (pin "1") (pinfunction "SCL_1") (pintype "input"))
    )
    (net (code "14") (name "I2C0_SDA") (class "Default")
      (node (ref "R2") (pin "1") (pinfunction "1_1") (pintype "passive"))
      (node (ref "SIP") (pin "C17") (pinfunction "I2C0_SDA_C17") (pintype "bidirectional"))
      (node (ref "SIP") (pin "C19") (pinfunction "PMIC_I2C_SDA_C19") (pintype "bidirectional"))
      (node (ref "U5") (pin "3") (pinfunction "SDA_3") (pintype "bidirectional"))
    )
    (net (code "15") (name "I2C1_SCL") (class "Default")
      (node (ref "I2C1") (pin "3") (pinfunction "3_3") (pintype "bidirectional"))
      (node (ref "R12") (pin "1") (pinfunction "1_1") (pintype "passive"))
      (node (ref "R75") (pin "1") (pinfunction "1_1") (pintype "passive"))
    )
    (net (code "16") (name "I2C1_SDA") (class "Default")
      (node (ref "I2C1") (pin "4") (pinfunction "4_4") (pintype "bidirectional"))
      (node (ref "R13") (pin "2") (pinfunction "2_2") (pintype "passive"))
      (node (ref "R74") (pin "1") (pinfunction "1_1") (pintype "passive"))
    )
    (net (code "17") (name "I2C2_SCL") (class "Default")
      (node (ref "BMP") (pin "5") (pinfunction "SCL_5") (pintype "input"))
      (node (ref "IMU") (pin "23") (pinfunction "SCL/SCLK_23") (pintype "bidirectional"))
      (node (ref "R11") (pin "1") (pinfunction "1_1") (pintype "passive"))
      (node (ref "R81") (pin "1") (pinfunction "1_1") (pintype "passive"))
    )
    (net (code "18") (name "I2C2_SDA") (class "Default")
      (node (ref "BMP") (pin "6") (pinfunction "SDA_6") (pintype "bidirectional"))
      (node (ref "IMU") (pin "24") (pinfunction "SDA/SDI_24") (pintype "bidirectional"))
      (node (ref "R10") (pin "2") (pinfunction "2_2") (pintype "passive"))
      (node (ref "R80") (pin "1") (pinfunction "1_1") (pintype "passive"))
    )
    (net (code "19") (name "IMU_INT") (class "Default")
      (node (ref "IMU") (pin "12") (pinfunction "INT_12") (pintype "bidirectional"))
      (node (ref "SIP") (pin "A14") (pinfunction "GPIO3_21_A14_A14") (pintype "bidirectional"))
    )
    (net (code "20") (name "LDO_PGOOD") (class "Default")
      (node (ref "SIP") (pin "B20") (pinfunction "PMIC_OUT_LDO_PGOOD_B20") (pintype "output"))
      (node (ref "SIP") (pin "B5") (pinfunction "RTC_PWRONRSTN_B5") (pintype "bidirectional"))
    )
    (net (code "21") (name "LED_1") (class "Default")
      (node (ref "D4") (pin "A") (pinfunction "A_A") (pintype "passive"))
      (node (ref "SIP") (pin "U12") (pinfunction "GPIO0_27_U12_U12") (pintype "bidirectional"))
    )
    (net (code "22") (name "LED_2") (class "Default")
      (node (ref "D5") (pin "A") (pinfunction "A_A") (pintype "passive"))
      (node (ref "R143") (pin "2") (pinfunction "2_2") (pintype "passive"))
      (node (ref "SIP") (pin "T5") (pinfunction "LCD_DATA15_T5_T5") (pintype "bidirectional"))
    )
    (net (code "23") (name "LED_3") (class "Default")
      (node (ref "D6") (pin "A") (pinfunction "A_A") (pintype "passive"))
      (node (ref "SIP") (pin "V6") (pinfunction "GPIO1_29_V6_V6") (pintype "bidirectional"))
    )
    (net (code "24") (name "LED_4") (class "Default")
      (node (ref "D7") (pin "A") (pinfunction "A_A") (pintype "passive"))
      (node (ref "SIP") (pin "T11") (pinfunction "GPIO0_26_T11_T11") (pintype "bidirectional"))
    )
    (net (code "25") (name "LED_GRN") (class "Default")
      (node (ref "GRN") (pin "A") (pinfunction "A_A") (pintype "passive"))
      (node (ref "SIP") (pin "T7") (pinfunction "TIMER7_T7_T7") (pintype "bidirectional"))
    )
    (net (code "26") (name "LED_RED") (class "Default")
      (node (ref "RED") (pin "A") (pinfunction "A_A") (pintype "passive"))
      (node (ref "SIP") (pin "R7") (pinfunction "TIMER4_R7_R7") (pintype "bidirectional"))
    )
    (net (code "27") (name "MDIR_1A") (class "Default")
      (node (ref "H1") (pin "21") (pinfunction "AIN1_21") (pintype "bidirectional"))
      (node (ref "SIP") (pin "C12") (pinfunction "SPI1_CS0_C12_C12") (pintype "bidirectional"))
    )
    (net (code "28") (name "MDIR_1B") (class "Default")
      (node (ref "H1") (pin "22") (pinfunction "AIN2_22") (pintype "bidirectional"))
      (node (ref "SIP") (pin "U17") (pinfunction "UART4_TXD_U17_U17") (pintype "bidirectional"))
    )
    (net (code "29") (name "MDIR_2A") (class "Default")
      (node (ref "H1") (pin "17") (pinfunction "BIN1_17") (pintype "bidirectional"))
      (node (ref "SIP") (pin "R13") (pinfunction "GPIO1_16_R13_R13") (pintype "bidirectional"))
    )
    (net (code "30") (name "MDIR_2B") (class "Default")
      (node (ref "H1") (pin "16") (pinfunction "BIN2_16") (pintype "bidirectional"))
      (node (ref "R140") (pin "1") (pinfunction "1_1") (pintype "passive"))
      (node (ref "SIP") (pin "V4") (pinfunction "LCD_DATA14_V4_V4") (pintype "bidirectional"))
    )
    (net (code "31") (name "MDIR_3A") (class "Default")
      (node (ref "H2") (pin "21") (pinfunction "AIN1_21") (pintype "bidirectional"))
      (node (ref "R118") (pin "1") (pinfunction "1_1") (pintype "passive"))
      (node (ref "SIP") (pin "R4") (pinfunction "LCD_DATA3_R4_R4") (pintype "bidirectional"))
    )
    (net (code "32") (name "MDIR_3B") (class "Default")
      (node (ref "H2") (pin "22") (pinfunction "AIN2_22") (pintype "bidirectional"))
      (node (ref "R116") (pin "1") (pinfunction "1_1") (pintype "passive"))
      (node (ref "R148") (pin "1") (pinfunction "1_1") (pintype "passive"))
      (node (ref "SIP") (pin "R3") (pinfunction "LCD_DATA2_R3_R3") (pintype "bidirectional"))
    )
    (net (code "33") (name "MDIR_4A") (class "Default")
      (node (ref "H2") (pin "17") (pinfunction "BIN1_17") (pintype "bidirectional"))
      (node (ref "R113") (pin "2") (pinfunction "2_2") (pintype "passive"))
      (node (ref "SIP") (pin "R1") (pinfunction "LCD_DATA0_R1_R1") (pintype "bidirectional"))
    )
    (net (code "34") (name "MDIR_4B") (class "Default")
      (node (ref "H2") (pin "16") (pinfunction "BIN2_16") (pintype "bidirectional"))
      (node (ref "R115") (pin "2") (pinfunction "2_2") (pintype "passive"))
      (node (ref "SIP") (pin "R2") (pinfunction "LCD_DATA1_R2_R2") (pintype "bidirectional"))
    )
    (net (code "35") (name "MODE_BTN") (class "Default")
      (node (ref "MODE") (pin "2") (pinfunction "2_2") (pintype "passive"))
      (node (ref "SIP") (pin "U6") (pinfunction "TIMER6_U6_U6") (pintype "bidirectional"))
    )
    (net (code "36") (name "MOT_STBY") (class "Default")
      (node (ref "H1") (pin "19") (pinfunction "STBY_19") (pintype "bidirectional"))
      (node (ref "H2") (pin "19") (pinfunction "STBY_19") (pintype "bidirectional"))
      (node (ref "SIP") (pin "D14") (pinfunction "GPIO0_20_D14_D14") (pintype "bidirectional"))
    )
    (net (code "37") (name "Net-(5VREG-OUT)") (class "Default")
      (node (ref "5VREG") (pin "2") (pinfunction "OUT_2") (pintype "power_in"))
      (node (ref "D1") (pin "C") (pinfunction "C_C") (pintype "passive"))
      (node (ref "L1") (pin "1") (pinfunction "1_1") (pintype "passive"))
    )
    (net (code "38") (name "Net-(5VREG-VIN)") (class "Default")
      (node (ref "5VREG") (pin "1") (pinfunction "VIN_1") (pintype "input"))
      (node (ref "C3") (pin "1") (pinfunction "1_1") (pintype "passive"))
      (node (ref "D2") (pin "C") (pinfunction "C_C") (pintype "passive"))
      (node (ref "D3") (pin "C") (pinfunction "C_C") (pintype "passive"))
    )
    (net (code "39") (name "Net-(6V_REG-BS)") (class "Default")
      (node (ref "6V_REG") (pin "2") (pinfunction "BS_2") (pintype "bidirectional"))
      (node (ref "C22") (pin "1") (pinfunction "1_1") (pintype "passive"))
    )
    (net (code "40") (name "Net-(6V_REG-COMP)") (class "Default")
      (node (ref "6V_REG") (pin "5") (pinfunction "COMP_5") (pintype "bidirectional"))
      (node (ref "R45") (pin "2") (pinfunction "2_2") (pintype "passive"))
    )
    (net (code "41") (name "Net-(6V_REG-FB)") (class "Default")
      (node (ref "6V_REG") (pin "6") (pinfunction "FB_6") (pintype "bidirectional"))
      (node (ref "R48") (pin "2") (pinfunction "2_2") (pintype "passive"))
      (node (ref "R49") (pin "1") (pinfunction "1_1") (pintype "passive"))
    )
    (net (code "42") (name "Net-(6V_REG-FSW)") (class "Default")
      (node (ref "6V_REG") (pin "4") (pinfunction "FSW_4") (pintype "bidirectional"))
      (node (ref "R47") (pin "2") (pinfunction "2_2") (pintype "passive"))
    )
    (net (code "43") (name "Net-(6V_REG-LX)") (class "Default")
      (node (ref "6V_REG") (pin "1") (pinfunction "LX_1") (pintype "bidirectional"))
      (node (ref "C22") (pin "2") (pinfunction "2_2") (pintype "passive"))
      (node (ref "D9") (pin "C") (pinfunction "C_C") (pintype "passive"))
      (node (ref "L3") (pin "1") (pinfunction "1_1") (pintype "passive"))
    )
    (net (code "44") (name "Net-(6V_REG-SS)") (class "Default")
      (node (ref "6V_REG") (pin "7") (pinfunction "SS_7") (pintype "bidirectional"))
      (node (ref "C21") (pin "2") (pinfunction "2_2") (pintype "passive"))
    )
    (net (code "45") (name "Net-(BAL-CD)") (class "Default")
      (node (ref "BAL") (pin "4") (pinfunction "CD_4") (pintype "bidirectional"))
      (node (ref "C19") (pin "1") (pinfunction "1_1") (pintype "passive"))
    )
    (net (code "46") (name "Net-(BAL-OUT)") (class "Default")
      (node (ref "BAL") (pin "8") (pinfunction "OUT_8") (pintype "bidirectional"))
      (node (ref "R7") (pin "1") (pinfunction "1_1") (pintype "passive"))
    )
    (net (code "47") (name "Net-(BAL-VC1)") (class "Default")
      (node (ref "BAL") (pin "2") (pinfunction "VC1_2") (pintype "bidirectional"))
      (node (ref "C17") (pin "1") (pinfunction "1_1") (pintype "passive"))
      (node (ref "C18") (pin "2") (pinfunction "2_2") (pintype "passive"))
      (node (ref "R30") (pin "2") (pinfunction "2_2") (pintype "passive"))
    )
    (net (code "48") (name "Net-(BAL-VC1_CB)") (class "Default")
      (node (ref "BAL") (pin "3") (pinfunction "VC1_CB_3") (pintype "bidirectional"))
      (node (ref "R27") (pin "2") (pinfunction "2_2") (pintype "passive"))
    )
    (net (code "49") (name "Net-(BAL-VC2)") (class "Default")
      (node (ref "BAL") (pin "1") (pinfunction "VC2_1") (pintype "bidirectional"))
      (node (ref "C17") (pin "2") (pinfunction "2_2") (pintype "passive"))
      (node (ref "R28") (pin "2") (pinfunction "2_2") (pintype "passive"))
    )
    (net (code "50") (name "Net-(BAL-VDD)") (class "Default")
      (node (ref "BAL") (pin "7") (pinfunction "VDD_7") (pintype "bidirectional"))
      (node (ref "C1") (pin "1") (pinfunction "1_1") (pintype "passive"))
      (node (ref "R34") (pin "2") (pinfunction "2_2") (pintype "passive"))
    )
    (net (code "51") (name "Net-(BOOT-Pad1)") (class "Default")
      (node (ref "BOOT") (pin "1") (pinfunction "1_1") (pintype "passive"))
      (node (ref "R148") (pin "2") (pinfunction "2_2") (pintype "passive"))
    )
    (net (code "52") (name "Net-(C23-Pad2)") (class "Default")
      (node (ref "C23") (pin "2") (pinfunction "2_2") (pintype "passive"))
      (node (ref "L3") (pin "2") (pinfunction "2_2") (pintype "passive"))
      (node (ref "R49") (pin "2") (pinfunction "2_2") (pintype "passive"))
      (node (ref "U$1") (pin "P$10") (pinfunction "PWR_P$10") (pintype "bidirectional"))
      (node (ref "U$1") (pin "P$11") (pinfunction "PWR_P$11") (pintype "bidirectional"))
      (node (ref "U$1") (pin "P$12") (pinfunction "PWR_P$12") (pintype "bidirectional"))
      (node (ref "U$1") (pin "P$21") (pinfunction "PWR_P$21") (pintype "bidirectional"))
      (node (ref "U$1") (pin "P$22") (pinfunction "PWR_P$22") (pintype "bidirectional"))
      (node (ref "U$1") (pin "P$7") (pinfunction "PWR_P$7") (pintype "bidirectional"))
      (node (ref "U$1") (pin "P$8") (pinfunction "PWR_P$8") (pintype "bidirectional"))
      (node (ref "U$1") (pin "P$9") (pinfunction "PWR_P$9") (pintype "bidirectional"))
    )
    (net (code "53") (name "Net-(C24-Pad2)") (class "Default")
      (node (ref "C24") (pin "2") (pinfunction "2_2") (pintype "passive"))
      (node (ref "R45") (pin "1") (pinfunction "1_1") (pintype "passive"))
    )
    (net (code "54") (name "Net-(C50-1)") (class "Default")
      (node (ref "C50") (pin "+") (pinfunction "1_+") (pintype "passive"))
      (node (ref "R152") (pin "2") (pinfunction "2_2") (pintype "passive"))
      (node (ref "R153") (pin "2") (pinfunction "2_2") (pintype "passive"))
      (node (ref "U7") (pin "2") (pinfunction "IN_2_2") (pintype "input"))
      (node (ref "U7") (pin "3") (pinfunction "IN_3") (pintype "input"))
    )
    (net (code "55") (name "Net-(CHG-PadC)") (class "Default")
      (node (ref "CHG") (pin "C") (pinfunction "C_C") (pintype "passive"))
      (node (ref "R3") (pin "2") (pinfunction "2_2") (pintype "passive"))
    )
    (net (code "56") (name "Net-(CHGIC-BST)") (class "Default")
      (node (ref "C14") (pin "1") (pinfunction "1_1") (pintype "passive"))
      (node (ref "CHGIC") (pin "15") (pinfunction "BST_15") (pintype "bidirectional"))
    )
    (net (code "57") (name "Net-(CHGIC-CHGOK)") (class "Default")
      (node (ref "CHGIC") (pin "11") (pinfunction "CHGOK_11") (pintype "bidirectional"))
      (node (ref "R3") (pin "1") (pinfunction "1_1") (pintype "passive"))
    )
    (net (code "58") (name "Net-(CHGIC-CSP)") (class "Default")
      (node (ref "CHGIC") (pin "10") (pinfunction "CSP_10") (pintype "bidirectional"))
      (node (ref "L2") (pin "2") (pinfunction "2_2") (pintype "passive"))
      (node (ref "R4") (pin "2") (pinfunction "2_2") (pintype "passive"))
    )
    (net (code "59") (name "Net-(CHGIC-NTC)") (class "Default")
      (node (ref "CHGIC") (pin "13") (pinfunction "NTC_13") (pintype "bidirectional"))
      (node (ref "R5") (pin "1") (pinfunction "1_1") (pintype "passive"))
      (node (ref "R6") (pin "2") (pinfunction "2_2") (pintype "passive"))
    )
    (net (code "60") (name "Net-(CHGIC-SW)") (class "Default")
      (node (ref "C14") (pin "2") (pinfunction "2_2") (pintype "passive"))
      (node (ref "CHGIC") (pin "1") (pinfunction "SW_1") (pintype "bidirectional"))
      (node (ref "L2") (pin "1") (pinfunction "1_1") (pintype "passive"))
    )
    (net (code "61") (name "Net-(CHGIC-TMR)") (class "Default")
      (node (ref "C10") (pin "2") (pinfunction "2_2") (pintype "passive"))
      (node (ref "CHGIC") (pin "14") (pinfunction "TMR_14") (pintype "bidirectional"))
    )
    (net (code "62") (name "Net-(D4-PadC)") (class "Default")
      (node (ref "D4") (pin "C") (pinfunction "C_C") (pintype "passive"))
      (node (ref "R31") (pin "1") (pinfunction "1_1") (pintype "passive"))
    )
    (net (code "63") (name "Net-(D5-PadC)") (class "Default")
      (node (ref "D5") (pin "C") (pinfunction "C_C") (pintype "passive"))
      (node (ref "R29") (pin "1") (pinfunction "1_1") (pintype "passive"))
    )
    (net (code "64") (name "Net-(D6-PadC)") (class "Default")
      (node (ref "D6") (pin "C") (pinfunction "C_C") (pintype "passive"))
      (node (ref "R33") (pin "1") (pinfunction "1_1") (pintype "passive"))
    )
    (net (code "65") (name "Net-(D7-PadC)") (class "Default")
      (node (ref "D7") (pin "C") (pinfunction "C_C") (pintype "passive"))
      (node (ref "R32") (pin "1") (pinfunction "1_1") (pintype "passive"))
    )
    (net (code "66") (name "Net-(D10-PadC)") (class "Default")
      (node (ref "D10") (pin "C") (pinfunction "C_C") (pintype "passive"))
      (node (ref "R61") (pin "2") (pinfunction "2_2") (pintype "passive"))
    )
    (net (code "67") (name "Net-(D11-PadC)") (class "Default")
      (node (ref "D11") (pin "C") (pinfunction "C_C") (pintype "passive"))
      (node (ref "R62") (pin "2") (pinfunction "2_2") (pintype "passive"))
    )
    (net (code "68") (name "Net-(D12-PadC)") (class "Default")
      (node (ref "D12") (pin "C") (pinfunction "C_C") (pintype "passive"))
      (node (ref "R63") (pin "2") (pinfunction "2_2") (pintype "passive"))
    )
    (net (code "69") (name "Net-(D13-PadC)") (class "Default")
      (node (ref "D13") (pin "C") (pinfunction "C_C") (pintype "passive"))
      (node (ref "R64") (pin "2") (pinfunction "2_2") (pintype "passive"))
    )
    (net (code "70") (name "Net-(GRN-PadC)") (class "Default")
      (node (ref "GRN") (pin "C") (pinfunction "C_C") (pintype "passive"))
      (node (ref "R22") (pin "1") (pinfunction "1_1") (pintype "passive"))
    )
    (net (code "71") (name "Net-(HOST-D+)") (class "Default")
      (node (ref "HOST") (pin "3") (pinfunction "D+_3") (pintype "bidirectional"))
      (node (ref "SIP") (pin "R17") (pinfunction "USB1_DP_R17") (pintype "bidirectional"))
      (node (ref "U4") (pin "1") (pinfunction "D+_1") (pintype "passive"))
    )
    (net (code "72") (name "Net-(HOST-D-)") (class "Default")
      (node (ref "HOST") (pin "2") (pinfunction "D-_2") (pintype "bidirectional"))
      (node (ref "SIP") (pin "R18") (pinfunction "USB1_DM_R18") (pintype "bidirectional"))
      (node (ref "U4") (pin "2") (pinfunction "D-_2") (pintype "passive"))
    )
    (net (code "73") (name "Net-(HOST-GND)") (class "Default")
      (node (ref "HOST") (pin "4") (pinfunction "GND_4") (pintype "bidirectional"))
      (node (ref "L4") (pin "2") (pinfunction "2_2") (pintype "passive"))
    )
    (net (code "74") (name "Net-(HOST-VBUS)") (class "Default")
      (node (ref "HOST") (pin "1") (pinfunction "VBUS_1") (pintype "bidirectional"))
      (node (ref "L5") (pin "2") (pinfunction "2_2") (pintype "passive"))
    )
    (net (code "75") (name "Net-(IMU-REGOUT)") (class "Default")
      (node (ref "C6") (pin "1") (pinfunction "1_1") (pintype "passive"))
      (node (ref "IMU") (pin "10") (pinfunction "REGOUT_10") (pintype "bidirectional"))
    )
    (net (code "76") (name "Net-(M1-1)") (class "Default")
      (node (ref "H1") (pin "5") (pinfunction "A02_5") (pintype "bidirectional"))
      (node (ref "H1") (pin "6") (pinfunction "A02_6") (pintype "bidirectional"))
      (node (ref "M1") (pin "P$1") (pinfunction "1_P$1") (pintype "bidirectional"))
    )
    (net (code "77") (name "Net-(M1-2)") (class "Default")
      (node (ref "H1") (pin "1") (pinfunction "A01_1") (pintype "bidirectional"))
      (node (ref "H1") (pin "2") (pinfunction "A01_2") (pintype "bidirectional"))
      (node (ref "M1") (pin "P$2") (pinfunction "2_P$2") (pintype "bidirectional"))
    )
    (net (code "78") (name "Net-(M2-1)") (class "Default")
      (node (ref "H1") (pin "11") (pinfunction "B01_11") (pintype "bidirectional"))
      (node (ref "H1") (pin "12") (pinfunction "B01_12") (pintype "bidirectional"))
      (node (ref "M2") (pin "P$1") (pinfunction "1_P$1") (pintype "bidirectional"))
    )
    (net (code "79") (name "Net-(M2-2)") (class "Default")
      (node (ref "H1") (pin "7") (pinfunction "B02_7") (pintype "bidirectional"))
      (node (ref "H1") (pin "8") (pinfunction "B02_8") (pintype "bidirectional"))
      (node (ref "M2") (pin "P$2") (pinfunction "2_P$2") (pintype "bidirectional"))
    )
    (net (code "80") (name "Net-(M3-1)") (class "Default")
      (node (ref "H2") (pin "1") (pinfunction "A01_1") (pintype "bidirectional"))
      (node (ref "H2") (pin "2") (pinfunction "A01_2") (pintype "bidirectional"))
      (node (ref "M3") (pin "P$1") (pinfunction "1_P$1") (pintype "bidirectional"))
    )
    (net (code "81") (name "Net-(M3-2)") (class "Default")
      (node (ref "H2") (pin "5") (pinfunction "A02_5") (pintype "bidirectional"))
      (node (ref "H2") (pin "6") (pinfunction "A02_6") (pintype "bidirectional"))
      (node (ref "M3") (pin "P$2") (pinfunction "2_P$2") (pintype "bidirectional"))
    )
    (net (code "82") (name "Net-(M4-1)") (class "Default")
      (node (ref "H2") (pin "7") (pinfunction "B02_7") (pintype "bidirectional"))
      (node (ref "H2") (pin "8") (pinfunction "B02_8") (pintype "bidirectional"))
      (node (ref "M4") (pin "P$1") (pinfunction "1_P$1") (pintype "bidirectional"))
    )
    (net (code "83") (name "Net-(M4-2)") (class "Default")
      (node (ref "H2") (pin "11") (pinfunction "B01_11") (pintype "bidirectional"))
      (node (ref "H2") (pin "12") (pinfunction "B01_12") (pintype "bidirectional"))
      (node (ref "M4") (pin "P$2") (pinfunction "2_P$2") (pintype "bidirectional"))
    )
    (net (code "84") (name "Net-(P10-CD)") (class "Default")
      (node (ref "P10") (pin "10") (pinfunction "CD_10") (pintype "bidirectional"))
      (node (ref "R71") (pin "2") (pinfunction "2_2") (pintype "passive"))
      (node (ref "SIP") (pin "C15") (pinfunction "MMC0_CD_C15_C15") (pintype "bidirectional"))
    )
    (net (code "85") (name "Net-(P10-CD{slash}DAT3)") (class "Default")
      (node (ref "P10") (pin "2") (pinfunction "CD/DAT3_2") (pintype "bidirectional"))
      (node (ref "R68") (pin "2") (pinfunction "2_2") (pintype "passive"))
      (node (ref "SIP") (pin "F17") (pinfunction "MMC0_DAT3_F17_F17") (pintype "bidirectional"))
    )
    (net (code "86") (name "Net-(P10-CLOCK)") (class "Default")
      (node (ref "P10") (pin "5") (pinfunction "CLOCK_5") (pintype "bidirectional"))
      (node (ref "R70") (pin "2") (pinfunction "2_2") (pintype "passive"))
      (node (ref "SIP") (pin "G17") (pinfunction "MMC0_CLK_G17_G17") (pintype "bidirectional"))
    )
    (net (code "87") (name "Net-(P10-CMD)") (class "Default")
      (node (ref "P10") (pin "3") (pinfunction "CMD_3") (pintype "bidirectional"))
      (node (ref "R69") (pin "2") (pinfunction "2_2") (pintype "passive"))
      (node (ref "SIP") (pin "G18") (pinfunction "MMC0_CMD_G18_G18") (pintype "bidirectional"))
    )
    (net (code "88") (name "Net-(P10-DAT0)") (class "Default")
      (node (ref "P10") (pin "7") (pinfunction "DAT0_7") (pintype "bidirectional"))
      (node (ref "R65") (pin "2") (pinfunction "2_2") (pintype "passive"))
      (node (ref "SIP") (pin "G16") (pinfunction "MMC0_DAT0_G16_G16") (pintype "bidirectional"))
    )
    (net (code "89") (name "Net-(P10-DAT1)") (class "Default")
      (node (ref "P10") (pin "8") (pinfunction "DAT1_8") (pintype "bidirectional"))
      (node (ref "R66") (pin "2") (pinfunction "2_2") (pintype "passive"))
      (node (ref "SIP") (pin "G15") (pinfunction "MMC0_DAT1_G15_G15") (pintype "bidirectional"))
    )
    (net (code "90") (name "Net-(P10-DAT2)") (class "Default")
      (node (ref "P10") (pin "1") (pinfunction "DAT2_1") (pintype "bidirectional"))
      (node (ref "R67") (pin "2") (pinfunction "2_2") (pintype "passive"))
      (node (ref "SIP") (pin "F18") (pinfunction "MMC0_DAT2_F18_F18") (pintype "bidirectional"))
    )
    (net (code "91") (name "Net-(PROT-VDD)") (class "Default")
      (node (ref "C15") (pin "2") (pinfunction "2_2") (pintype "passive"))
      (node (ref "PROT") (pin "5") (pinfunction "VDD_5") (pintype "bidirectional"))
      (node (ref "R44") (pin "2") (pinfunction "2_2") (pintype "passive"))
    )
    (net (code "92") (name "Net-(R21-Pad1)") (class "Default")
      (node (ref "R21") (pin "1") (pinfunction "1_1") (pintype "passive"))
      (node (ref "RED") (pin "C") (pinfunction "C_C") (pintype "passive"))
    )
    (net (code "93") (name "Net-(SIPA-BAT_TEMP)") (class "Default")
      (node (ref "SIP") (pin "W1") (pinfunction "BAT_TEMP_W1") (pintype "bidirectional"))
      (node (ref "TP4") (pin "TP") (pinfunction "TP_TP") (pintype "input"))
    )
    (net (code "94") (name "Net-(SIPA-BAT_VOLT)") (class "Default")
      (node (ref "SIP") (pin "Y1") (pinfunction "BAT_VOLT_Y1") (pintype "bidirectional"))
      (node (ref "TP3") (pin "TP") (pinfunction "TP_TP") (pintype "input"))
    )
    (net (code "95") (name "Net-(SIPA-L1_IN)") (class "Default")
      (node (ref "SIP") (pin "Y14") (pinfunction "L1_IN_Y14") (pintype "bidirectional"))
      (node (ref "TP6") (pin "TP") (pinfunction "TP_TP") (pintype "input"))
    )
    (net (code "96") (name "Net-(SIPA-L1_OUT)") (class "Default")
      (node (ref "SIP") (pin "Y13") (pinfunction "L1_OUT_Y13") (pintype "bidirectional"))
      (node (ref "TP7") (pin "TP") (pinfunction "TP_TP") (pintype "input"))
    )
    (net (code "97") (name "Net-(SIPA-L2_IN)") (class "Default")
      (node (ref "SIP") (pin "Y17") (pinfunction "L2_IN_Y17") (pintype "bidirectional"))
      (node (ref "TP8") (pin "TP") (pinfunction "TP_TP") (pintype "input"))
    )
    (net (code "98") (name "Net-(SIPA-L2_OUT)") (class "Default")
      (node (ref "SIP") (pin "Y16") (pinfunction "L2_OUT_Y16") (pintype "bidirectional"))
      (node (ref "TP9") (pin "TP") (pinfunction "TP_TP") (pintype "input"))
    )
    (net (code "99") (name "Net-(SIPA-L3_IN)") (class "Default")
      (node (ref "SIP") (pin "Y20") (pinfunction "L3_IN_Y20") (pintype "bidirectional"))
      (node (ref "TP10") (pin "TP") (pinfunction "TP_TP") (pintype "input"))
    )
    (net (code "100") (name "Net-(SIPA-L3_OUT)") (class "Default")
      (node (ref "SIP") (pin "Y19") (pinfunction "L3_OUT_Y19") (pintype "bidirectional"))
      (node (ref "TP11") (pin "TP") (pinfunction "TP_TP") (pintype "input"))
    )
    (net (code "101") (name "Net-(SIPA-PMIC_IN_PWR_EN)") (class "Default")
      (node (ref "SIP") (pin "C6") (pinfunction "PMIC_POWER_EN_C6") (pintype "output"))
      (node (ref "SIP") (pin "D19") (pinfunction "PMIC_IN_PWR_EN_D19") (pintype "input"))
      (node (ref "TP5") (pin "TP") (pinfunction "TP_TP") (pintype "input"))
    )
    (net (code "102") (name "Net-(SIPA-VIN_BAT_0)") (class "Default")
      (node (ref "SIP") (pin "Y2") (pinfunction "VIN_BAT_0_Y2") (pintype "power_in"))
      (node (ref "SIP") (pin "Y3") (pinfunction "VIN_BAT_1_Y3") (pintype "power_in"))
      (node (ref "TP2") (pin "TP") (pinfunction "TP_TP") (pintype "input"))
    )
    (net (code "103") (name "Net-(SIPB-EMMCRST_GPIO1_20_R14)") (class "Default")
      (node (ref "R94") (pin "1") (pinfunction "1_1") (pintype "passive"))
      (node (ref "SIP") (pin "R14") (pinfunction "EMMCRST_GPIO1_20_R14_R14") (pintype "bidirectional"))
      (node (ref "U8") (pin "K5") (pinfunction "RST_K5") (pintype "bidirectional"))
    )
    (net (code "104") (name "Net-(SIPB-GPIO0_19_A15)") (class "Default")
      (node (ref "R82") (pin "1") (pinfunction "1_1") (pintype "passive"))
      (node (ref "SIP") (pin "A15") (pinfunction "GPIO0_19_A15_A15") (pintype "bidirectional"))
    )
    (net (code "105") (name "Net-(SIPB-GPIO1_12_T12)") (class "Default")
      (node (ref "R95") (pin "1") (pinfunction "1_1") (pintype "passive"))
      (node (ref "SIP") (pin "T12") (pinfunction "GPIO1_12_T12_T12") (pintype "bidirectional"))
    )
    (net (code "106") (name "Net-(SIPB-GPIO1_13_R12)") (class "Default")
      (node (ref "R96") (pin "1") (pinfunction "1_1") (pintype "passive"))
      (node (ref "SIP") (pin "R12") (pinfunction "GPIO1_13_R12_R12") (pintype "bidirectional"))
    )
    (net (code "107") (name "Net-(SIPB-GPIO1_14_V13)") (class "Default")
      (node (ref "R97") (pin "1") (pinfunction "1_1") (pintype "passive"))
      (node (ref "SIP") (pin "V13") (pinfunction "GPIO1_14_V13_V13") (pintype "bidirectional"))
    )
    (net (code "108") (name "Net-(SIPB-GPIO1_15_U13)") (class "Default")
      (node (ref "R98") (pin "1") (pinfunction "1_1") (pintype "passive"))
      (node (ref "SIP") (pin "U13") (pinfunction "GPIO1_15_U13_U13") (pintype "bidirectional"))
    )
    (net (code "109") (name "Net-(SIPB-GPIO3_18_B12)") (class "Default")
      (node (ref "R99") (pin "1") (pinfunction "1_1") (pintype "passive"))
      (node (ref "SIP") (pin "B12") (pinfunction "GPIO3_18_B12_B12") (pintype "bidirectional"))
    )
    (net (code "110") (name "Net-(SIPB-GPIO3_19_C13)") (class "Default")
      (node (ref "R100") (pin "1") (pinfunction "1_1") (pintype "passive"))
      (node (ref "SIP") (pin "C13") (pinfunction "GPIO3_19_C13_C13") (pintype "bidirectional"))
    )
    (net (code "111") (name "Net-(SIPB-I2C1_SCL_A16)") (class "Default")
      (node (ref "R75") (pin "2") (pinfunction "2_2") (pintype "passive"))
      (node (ref "SIP") (pin "A16") (pinfunction "I2C1_SCL_A16_A16") (pintype "bidirectional"))
    )
    (net (code "112") (name "Net-(SIPB-I2C1_SDA_B16)") (class "Default")
      (node (ref "R74") (pin "2") (pinfunction "2_2") (pintype "passive"))
      (node (ref "SIP") (pin "B16") (pinfunction "I2C1_SDA_B16_B16") (pintype "bidirectional"))
    )
    (net (code "113") (name "Net-(SIPB-I2C2_SCL_D17)") (class "Default")
      (node (ref "R81") (pin "2") (pinfunction "2_2") (pintype "passive"))
      (node (ref "SIP") (pin "D17") (pinfunction "I2C2_SCL_D17_D17") (pintype "bidirectional"))
    )
    (net (code "114") (name "Net-(SIPB-I2C2_SDA_D18)") (class "Default")
      (node (ref "R80") (pin "2") (pinfunction "2_2") (pintype "passive"))
      (node (ref "SIP") (pin "D18") (pinfunction "I2C2_SDA_D18_D18") (pintype "bidirectional"))
    )
    (net (code "115") (name "Net-(SIPB-JTAG_EMU0)") (class "Default")
      (node (ref "SIP") (pin "C14") (pinfunction "JTAG_EMU0_C14") (pintype "bidirectional"))
      (node (ref "TP15") (pin "TP") (pinfunction "TP_TP") (pintype "input"))
    )
    (net (code "116") (name "Net-(SIPB-JTAG_EMU1)") (class "Default")
      (node (ref "SIP") (pin "B14") (pinfunction "JTAG_EMU1_B14") (pintype "bidirectional"))
      (node (ref "TP14") (pin "TP") (pinfunction "TP_TP") (pintype "input"))
    )
    (net (code "117") (name "Net-(SIPB-JTAG_TCK)") (class "Default")
      (node (ref "SIP") (pin "A12") (pinfunction "JTAG_TCK_A12") (pintype "bidirectional"))
      (node (ref "TP17") (pin "TP") (pinfunction "TP_TP") (pintype "input"))
    )
    (net (code "118") (name "Net-(SIPB-JTAG_TDI)") (class "Default")
      (node (ref "SIP") (pin "B11") (pinfunction "JTAG_TDI_B11") (pintype "bidirectional"))
      (node (ref "TP18") (pin "TP") (pinfunction "TP_TP") (pintype "input"))
    )
    (net (code "119") (name "Net-(SIPB-JTAG_TDO)") (class "Default")
      (node (ref "SIP") (pin "A11") (pinfunction "JTAG_TDO_A11") (pintype "bidirectional"))
      (node (ref "TP16") (pin "TP") (pinfunction "TP_TP") (pintype "input"))
    )
    (net (code "120") (name "Net-(SIPB-JTAG_TMS)") (class "Default")
      (node (ref "SIP") (pin "C11") (pinfunction "JTAG_TMS_C11") (pintype "bidirectional"))
      (node (ref "TP19") (pin "TP") (pinfunction "TP_TP") (pintype "input"))
    )
    (net (code "121") (name "Net-(SIPB-JTAG_TRSTN)") (class "Default")
      (node (ref "R59") (pin "2") (pinfunction "2_2") (pintype "passive"))
      (node (ref "SIP") (pin "B10") (pinfunction "JTAG_TRSTN_B10") (pintype "bidirectional"))
      (node (ref "TP20") (pin "TP") (pinfunction "TP_TP") (pintype "input"))
    )
    (net (code "122") (name "Net-(SIPB-MMC1_CLK_U9)") (class "Default")
      (node (ref "R93") (pin "1") (pinfunction "1_1") (pintype "passive"))
      (node (ref "SIP") (pin "U9") (pinfunction "MMC1_CLK_U9_U9") (pintype "bidirectional"))
      (node (ref "U8") (pin "M6") (pinfunction "CLK_M6") (pintype "bidirectional"))
    )
    (net (code "123") (name "Net-(SIPB-MMC1_CMD_V9)") (class "Default")
      (node (ref "R92") (pin "1") (pinfunction "1_1") (pintype "passive"))
      (node (ref "SIP") (pin "V9") (pinfunction "MMC1_CMD_V9_V9") (pintype "bidirectional"))
      (node (ref "U8") (pin "M5") (pinfunction "CMD_M5") (pintype "bidirectional"))
    )
    (net (code "124") (name "Net-(SIPB-MMC1_DAT0_U7)") (class "Default")
      (node (ref "R91") (pin "1") (pinfunction "1_1") (pintype "passive"))
      (node (ref "SIP") (pin "U7") (pinfunction "MMC1_DAT0_U7_U7") (pintype "bidirectional"))
      (node (ref "U8") (pin "A3") (pinfunction "DAT0_A3") (pintype "bidirectional"))
    )
    (net (code "125") (name "Net-(SIPB-MMC1_DAT1_V7)") (class "Default")
      (node (ref "R90") (pin "1") (pinfunction "1_1") (pintype "passive"))
      (node (ref "SIP") (pin "V7") (pinfunction "MMC1_DAT1_V7_V7") (pintype "bidirectional"))
      (node (ref "U8") (pin "A4") (pinfunction "DAT1_A4") (pintype "bidirectional"))
    )
    (net (code "126") (name "Net-(SIPB-MMC1_DAT2_R8)") (class "Default")
      (node (ref "R89") (pin "1") (pinfunction "1_1") (pintype "passive"))
      (node (ref "SIP") (pin "R8") (pinfunction "MMC1_DAT2_R8_R8") (pintype "bidirectional"))
      (node (ref "U8") (pin "A5") (pinfunction "DAT2_A5") (pintype "bidirectional"))
    )
    (net (code "127") (name "Net-(SIPB-MMC1_DAT3_T8)") (class "Default")
      (node (ref "R88") (pin "1") (pinfunction "1_1") (pintype "passive"))
      (node (ref "SIP") (pin "T8") (pinfunction "MMC1_DAT3_T8_T8") (pintype "bidirectional"))
      (node (ref "U8") (pin "B2") (pinfunction "DAT3_B2") (pintype "bidirectional"))
    )
    (net (code "128") (name "Net-(SIPB-MMC1_DAT4_U8)") (class "Default")
      (node (ref "R87") (pin "1") (pinfunction "1_1") (pintype "passive"))
      (node (ref "SIP") (pin "U8") (pinfunction "MMC1_DAT4_U8_U8") (pintype "bidirectional"))
      (node (ref "U8") (pin "B3") (pinfunction "DAT4_B3") (pintype "bidirectional"))
    )
    (net (code "129") (name "Net-(SIPB-MMC1_DAT5_V8)") (class "Default")
      (node (ref "R86") (pin "1") (pinfunction "1_1") (pintype "passive"))
      (node (ref "SIP") (pin "V8") (pinfunction "MMC1_DAT5_V8_V8") (pintype "bidirectional"))
      (node (ref "U8") (pin "B4") (pinfunction "DAT5_B4") (pintype "bidirectional"))
    )
    (net (code "130") (name "Net-(SIPB-MMC1_DAT6_R9)") (class "Default")
      (node (ref "R85") (pin "1") (pinfunction "1_1") (pintype "passive"))
      (node (ref "SIP") (pin "R9") (pinfunction "MMC1_DAT6_R9_R9") (pintype "bidirectional"))
      (node (ref "U8") (pin "B5") (pinfunction "DAT6_B5") (pintype "bidirectional"))
    )
    (net (code "131") (name "Net-(SIPB-MMC1_DAT7_T9)") (class "Default")
      (node (ref "R84") (pin "1") (pinfunction "1_1") (pintype "passive"))
      (node (ref "SIP") (pin "T9") (pinfunction "MMC1_DAT7_T9_T9") (pintype "bidirectional"))
      (node (ref "U8") (pin "B6") (pinfunction "DAT7_B6") (pintype "bidirectional"))
    )
    (net (code "132") (name "Net-(SIPB-OSC0_GND)") (class "Default")
      (node (ref "C29") (pin "2") (pinfunction "2_2") (pintype "passive"))
      (node (ref "C30") (pin "2") (pinfunction "2_2") (pintype "passive"))
      (node (ref "SIP") (pin "L20") (pinfunction "OSC0_GND_L20") (pintype "bidirectional"))
    )
    (net (code "133") (name "Net-(SIPB-OSC0_IN)") (class "Default")
      (node (ref "C30") (pin "1") (pinfunction "1_1") (pintype "passive"))
      (node (ref "SIP") (pin "M20") (pinfunction "OSC0_IN_M20") (pintype "bidirectional"))
      (node (ref "Y1") (pin "2") (pinfunction "2_2") (pintype "passive"))
    )
    (net (code "134") (name "Net-(SIPB-OSC0_OUT)") (class "Default")
      (node (ref "C29") (pin "1") (pinfunction "1_1") (pintype "passive"))
      (node (ref "SIP") (pin "K20") (pinfunction "OSC0_OUT_K20") (pintype "bidirectional"))
      (node (ref "Y1") (pin "1") (pinfunction "1_1") (pintype "passive"))
    )
    (net (code "135") (name "Net-(SIPB-OSC1_GND)") (class "Default")
      (node (ref "C31") (pin "2") (pinfunction "2_2") (pintype "passive"))
      (node (ref "C32") (pin "1") (pinfunction "1_1") (pintype "passive"))
      (node (ref "SIP") (pin "G20") (pinfunction "OSC1_GND_G20") (pintype "bidirectional"))
    )
    (net (code "136") (name "Net-(SIPB-OSC1_IN)") (class "Default")
      (node (ref "C31") (pin "1") (pinfunction "1_1") (pintype "passive"))
      (node (ref "SIP") (pin "H20") (pinfunction "OSC1_IN_H20") (pintype "bidirectional"))
      (node (ref "Y2") (pin "2") (pinfunction "2_2") (pintype "passive"))
    )
    (net (code "137") (name "Net-(SIPB-OSC1_OUT)") (class "Default")
      (node (ref "C32") (pin "2") (pinfunction "2_2") (pintype "passive"))
      (node (ref "SIP") (pin "F20") (pinfunction "OSC1_OUT_F20") (pintype "bidirectional"))
      (node (ref "Y2") (pin "1") (pinfunction "1_1") (pintype "passive"))
    )
    (net (code "138") (name "Net-(SIPB-SPI1_CLK_A13)") (class "Default")
      (node (ref "R101") (pin "1") (pinfunction "1_1") (pintype "passive"))
      (node (ref "SIP") (pin "A13") (pinfunction "SPI1_CLK_A13_A13") (pintype "bidirectional"))
    )
    (net (code "139") (name "Net-(SIPB-SPI1_D0_B13)") (class "Default")
      (node (ref "R102") (pin "1") (pinfunction "1_1") (pintype "passive"))
      (node (ref "SIP") (pin "B13") (pinfunction "SPI1_D0_B13_B13") (pintype "bidirectional"))
    )
    (net (code "140") (name "Net-(SIPB-SPI1_D1_D12)") (class "Default")
      (node (ref "R103") (pin "1") (pinfunction "1_1") (pintype "passive"))
      (node (ref "SIP") (pin "D12") (pinfunction "SPI1_D1_D12_D12") (pintype "bidirectional"))
    )
    (net (code "141") (name "Net-(SIPB-UART0_RTSN_E17)") (class "Default")
      (node (ref "R104") (pin "1") (pinfunction "1_1") (pintype "passive"))
      (node (ref "SIP") (pin "E17") (pinfunction "UART0_RTSN_E17_E17") (pintype "bidirectional"))
    )
    (net (code "142") (name "Net-(SIPB-UART0_RXD_E15)") (class "Default")
      (node (ref "R77") (pin "2") (pinfunction "2_2") (pintype "passive"))
      (node (ref "SIP") (pin "E15") (pinfunction "UART0_RXD_E15_E15") (pintype "bidirectional"))
    )
    (net (code "143") (name "Net-(SIPB-UART0_TXD_E16)") (class "Default")
      (node (ref "R76") (pin "2") (pinfunction "2_2") (pintype "passive"))
      (node (ref "SIP") (pin "E16") (pinfunction "UART0_TXD_E16_E16") (pintype "bidirectional"))
    )
    (net (code "144") (name "Net-(SIPB-UART1_RXD_D16)") (class "Default")
      (node (ref "R79") (pin "2") (pinfunction "2_2") (pintype "passive"))
      (node (ref "SIP") (pin "D16") (pinfunction "UART1_RXD_D16_D16") (pintype "bidirectional"))
    )
    (net (code "145") (name "Net-(SIPB-UART1_TXD_D15)") (class "Default")
      (node (ref "R78") (pin "2") (pinfunction "2_2") (pintype "passive"))
      (node (ref "SIP") (pin "D15") (pinfunction "UART1_TXD_D15_D15") (pintype "bidirectional"))
    )
    (net (code "146") (name "Net-(SIPB-UART2_RXD_A17)") (class "Default")
      (node (ref "R72") (pin "2") (pinfunction "2_2") (pintype "passive"))
      (node (ref "SIP") (pin "A17") (pinfunction "UART2_RXD_A17_A17") (pintype "bidirectional"))
    )
    (net (code "147") (name "Net-(SIPB-UART2_TXD_B17)") (class "Default")
      (node (ref "R73") (pin "2") (pinfunction "2_2") (pintype "passive"))
      (node (ref "SIP") (pin "B17") (pinfunction "UART2_TXD_B17_B17") (pintype "bidirectional"))
    )
    (net (code "148") (name "Net-(SIPB-UART4_RXD_T17)") (class "Default")
      (node (ref "R83") (pin "1") (pinfunction "1_1") (pintype "passive"))
      (node (ref "SIP") (pin "T17") (pinfunction "UART4_RXD_T17_T17") (pintype "bidirectional"))
    )
    (net (code "149") (name "Net-(SIPB-USR0_V15)") (class "Default")
      (node (ref "D10") (pin "A") (pinfunction "A_A") (pintype "passive"))
      (node (ref "SIP") (pin "V15") (pinfunction "USR0_V15_V15") (pintype "bidirectional"))
    )
    (net (code "150") (name "Net-(SIPB-USR1_U15)") (class "Default")
      (node (ref "D11") (pin "A") (pinfunction "A_A") (pintype "passive"))
      (node (ref "SIP") (pin "U15") (pinfunction "USR1_U15_U15") (pintype "bidirectional"))
    )
    (net (code "151") (name "Net-(SIPB-USR2_T15)") (class "Default")
      (node (ref "D12") (pin "A") (pinfunction "A_A") (pintype "passive"))
      (node (ref "SIP") (pin "T15") (pinfunction "USR2_T15_T15") (pintype "bidirectional"))
    )
    (net (code "152") (name "Net-(SIPB-USR3_V16)") (class "Default")
      (node (ref "D13") (pin "A") (pinfunction "A_A") (pintype "passive"))
      (node (ref "SIP") (pin "V16") (pinfunction "USR3_V16_V16") (pintype "bidirectional"))
    )
    (net (code "153") (name "Net-(SIPC-ADC_VREFP)") (class "Default")
      (node (ref "C42") (pin "1") (pinfunction "1_1") (pintype "passive"))
      (node (ref "C43") (pin "1") (pinfunction "1_1") (pintype "passive"))
      (node (ref "R111") (pin "2") (pinfunction "2_2") (pintype "passive"))
      (node (ref "SIP") (pin "B9") (pinfunction "ADC_VREFP_B9") (pintype "bidirectional"))
    )
    (net (code "154") (name "Net-(SIPC-AIN0)") (class "Default")
      (node (ref "R105") (pin "2") (pinfunction "2_2") (pintype "passive"))
      (node (ref "SIP") (pin "B6") (pinfunction "AIN0_B6") (pintype "bidirectional"))
    )
    (net (code "155") (name "Net-(SIPC-AIN1)") (class "Default")
      (node (ref "R106") (pin "2") (pinfunction "2_2") (pintype "passive"))
      (node (ref "SIP") (pin "C7") (pinfunction "AIN1_C7") (pintype "bidirectional"))
    )
    (net (code "156") (name "Net-(SIPC-AIN2)") (class "Default")
      (node (ref "R107") (pin "2") (pinfunction "2_2") (pintype "passive"))
      (node (ref "SIP") (pin "B7") (pinfunction "AIN2_B7") (pintype "bidirectional"))
    )
    (net (code "157") (name "Net-(SIPC-AIN3)") (class "Default")
      (node (ref "R108") (pin "2") (pinfunction "2_2") (pintype "passive"))
      (node (ref "SIP") (pin "A7") (pinfunction "AIN3_A7") (pintype "bidirectional"))
    )
    (net (code "158") (name "Net-(SIPC-AIN7)") (class "Default")
      (node (ref "R109") (pin "2") (pinfunction "2_2") (pintype "passive"))
      (node (ref "R110") (pin "1") (pinfunction "1_1") (pintype "passive"))
      (node (ref "SIP") (pin "C9") (pinfunction "AIN7_C9") (pintype "bidirectional"))
    )
    (net (code "159") (name "Net-(SIPC-LCD_DATA8_U1)") (class "Default")
      (node (ref "R129") (pin "2") (pinfunction "2_2") (pintype "passive"))
      (node (ref "R144") (pin "1") (pinfunction "1_1") (pintype "passive"))
      (node (ref "SIP") (pin "U1") (pinfunction "LCD_DATA8_U1_U1") (pintype "bidirectional"))
    )
    (net (code "160") (name "Net-(SIPC-LCD_DATA9_U2)") (class "Default")
      (node (ref "R131") (pin "2") (pinfunction "2_2") (pintype "passive"))
      (node (ref "R145") (pin "1") (pinfunction "1_1") (pintype "passive"))
      (node (ref "SIP") (pin "U2") (pinfunction "LCD_DATA9_U2_U2") (pintype "bidirectional"))
    )
    (net (code "161") (name "Net-(SIPC-LCD_DATA11_U4)") (class "Default")
      (node (ref "R135") (pin "2") (pinfunction "2_2") (pintype "passive"))
      (node (ref "SIP") (pin "U4") (pinfunction "LCD_DATA11_U4_U4") (pintype "bidirectional"))
    )
    (net (code "162") (name "Net-(SIPC-LCD_DATA12_V2)") (class "Default")
      (node (ref "R137") (pin "2") (pinfunction "2_2") (pintype "passive"))
      (node (ref "R146") (pin "1") (pinfunction "1_1") (pintype "passive"))
      (node (ref "SIP") (pin "V2") (pinfunction "LCD_DATA12_V2_V2") (pintype "bidirectional"))
    )
    (net (code "163") (name "Net-(SIPC-LCD_DATA13_V3)") (class "Default")
      (node (ref "R139") (pin "2") (pinfunction "2_2") (pintype "passive"))
      (node (ref "R147") (pin "1") (pinfunction "1_1") (pintype "passive"))
      (node (ref "SIP") (pin "V3") (pinfunction "LCD_DATA13_V3_V3") (pintype "bidirectional"))
    )
    (net (code "164") (name "Net-(SIPC-USB0_DM)") (class "Default")
      (node (ref "SIP") (pin "N18") (pinfunction "USB0_DM_N18") (pintype "bidirectional"))
      (node (ref "U1") (pin "2") (pinfunction "D-_2") (pintype "passive"))
      (node (ref "USB") (pin "D-") (pinfunction "D-_D-") (pintype "bidirectional"))
    )
    (net (code "165") (name "Net-(SIPC-USB0_DP)") (class "Default")
      (node (ref "SIP") (pin "N17") (pinfunction "USB0_DP_N17") (pintype "bidirectional"))
      (node (ref "U1") (pin "1") (pinfunction "D+_1") (pintype "passive"))
      (node (ref "USB") (pin "D+") (pinfunction "D+_D+") (pintype "bidirectional"))
    )
    (net (code "166") (name "Net-(SIPC-USB0_ID)") (class "Default")
      (node (ref "SIP") (pin "P16") (pinfunction "USB0_ID_P16") (pintype "bidirectional"))
      (node (ref "U1") (pin "3") (pinfunction "ID_3") (pintype "passive"))
      (node (ref "USB") (pin "ID") (pinfunction "USBID_ID") (pintype "bidirectional"))
    )
    (net (code "167") (name "Net-(SIPC-USB0_VBUS)") (class "Default")
      (node (ref "R149") (pin "1") (pinfunction "1_1") (pintype "passive"))
      (node (ref "SIP") (pin "P15") (pinfunction "USB0_VBUS_P15") (pintype "bidirectional"))
    )
    (net (code "168") (name "Net-(SIPC-USB1OC_GPIO1_26_T16)") (class "Default")
      (node (ref "R155") (pin "1") (pinfunction "1_1") (pintype "passive"))
      (node (ref "SIP") (pin "T16") (pinfunction "USB1OC_GPIO1_26_T16_T16") (pintype "bidirectional"))
    )
    (net (code "169") (name "Net-(SIPC-USB1_DRVVBUS)") (class "Default")
      (node (ref "R151") (pin "2") (pinfunction "2_2") (pintype "passive"))
      (node (ref "SIP") (pin "F15") (pinfunction "USB1_DRVVBUS_F15") (pintype "bidirectional"))
      (node (ref "U7") (pin "4") (pinfunction "*EN_4") (pintype "input"))
    )
    (net (code "170") (name "Net-(SIPC-USB1_ID)") (class "Default")
      (node (ref "R150") (pin "1") (pinfunction "1_1") (pintype "passive"))
      (node (ref "SIP") (pin "P17") (pinfunction "USB1_ID_P17") (pintype "bidirectional"))
    )
    (net (code "171") (name "Net-(SIPC-USB1_VBUS)") (class "Default")
      (node (ref "R156") (pin "1") (pinfunction "1_1") (pintype "passive"))
      (node (ref "SIP") (pin "T18") (pinfunction "USB1_VBUS_T18") (pintype "bidirectional"))
    )
    (net (code "172") (name "Net-(SIPE-RTC_KALDO_ENN)") (class "Default")
      (node (ref "R158") (pin "1") (pinfunction "1_1") (pintype "passive"))
      (node (ref "SIP") (pin "B4") (pinfunction "RTC_KALDO_ENN_B4") (pintype "bidirectional"))
    )
    (net (code "173") (name "Net-(U$1-1)") (class "Default")
      (node (ref "R36") (pin "2") (pinfunction "2_2") (pintype "passive"))
      (node (ref "U$1") (pin "P$1") (pinfunction "1_P$1") (pintype "bidirectional"))
    )
    (net (code "174") (name "Net-(U$1-2)") (class "Default")
      (node (ref "R37") (pin "2") (pinfunction "2_2") (pintype "passive"))
      (node (ref "U$1") (pin "P$2") (pinfunction "2_P$2") (pintype "bidirectional"))
    )
    (net (code "175") (name "Net-(U$1-3)") (class "Default")
      (node (ref "R38") (pin "2") (pinfunction "2_2") (pintype "passive"))
      (node (ref "U$1") (pin "P$3") (pinfunction "3_P$3") (pintype "bidirectional"))
    )
    (net (code "176") (name "Net-(U$1-4)") (class "Default")
      (node (ref "R39") (pin "2") (pinfunction "2_2") (pintype "passive"))
      (node (ref "U$1") (pin "P$4") (pinfunction "4_P$4") (pintype "bidirectional"))
    )
    (net (code "177") (name "Net-(U$1-5)") (class "Default")
      (node (ref "R40") (pin "2") (pinfunction "2_2") (pintype "passive"))
      (node (ref "U$1") (pin "P$5") (pinfunction "5_P$5") (pintype "bidirectional"))
    )
    (net (code "178") (name "Net-(U$1-6)") (class "Default")
      (node (ref "R41") (pin "2") (pinfunction "2_2") (pintype "passive"))
      (node (ref "U$1") (pin "P$6") (pinfunction "6_P$6") (pintype "bidirectional"))
    )
    (net (code "179") (name "Net-(U$1-7)") (class "Default")
      (node (ref "R42") (pin "2") (pinfunction "2_2") (pintype "passive"))
      (node (ref "U$1") (pin "P$19") (pinfunction "7_P$19") (pintype "bidirectional"))
    )
    (net (code "180") (name "Net-(U$1-8)") (class "Default")
      (node (ref "R43") (pin "2") (pinfunction "2_2") (pintype "passive"))
      (node (ref "U$1") (pin "P$20") (pinfunction "8_P$20") (pintype "bidirectional"))
    )
    (net (code "181") (name "Net-(U1-VBUS)") (class "Default")
      (node (ref "R149") (pin "2") (pinfunction "2_2") (pintype "passive"))
      (node (ref "R154") (pin "1") (pinfunction "1_1") (pintype "passive"))
      (node (ref "U1") (pin "6") (pinfunction "VBUS_6") (pintype "passive"))
      (node (ref "USB") (pin "VBUS") (pinfunction "VBUS_VBUS") (pintype "bidirectional"))
    )
    (net (code "182") (name "Net-(U4-VBUS)") (class "Default")
      (node (ref "C45") (pin "1") (pinfunction "1_1") (pintype "passive"))
      (node (ref "C46") (pin "1") (pinfunction "1_1") (pintype "passive"))
      (node (ref "L5") (pin "1") (pinfunction "1_1") (pintype "passive"))
      (node (ref "R156") (pin "2") (pinfunction "2_2") (pintype "passive"))
      (node (ref "U4") (pin "6") (pinfunction "VBUS_6") (pintype "passive"))
      (node (ref "U7") (pin "6") (pinfunction "OUT_2_6") (pintype "power_in"))
      (node (ref "U7") (pin "7") (pinfunction "OUT_3_7") (pintype "power_in"))
      (node (ref "U7") (pin "8") (pinfunction "OUT_8") (pintype "power_in"))
    )
    (net (code "183") (name "Net-(U5-WP)") (class "Default")
      (node (ref "R58") (pin "1") (pinfunction "1_1") (pintype "passive"))
      (node (ref "TP13") (pin "TP") (pinfunction "TP_TP") (pintype "input"))
      (node (ref "U5") (pin "5") (pinfunction "WP_5") (pintype "input"))
    )
    (net (code "184") (name "Net-(U7-*OC)") (class "Default")
      (node (ref "R155") (pin "2") (pinfunction "2_2") (pintype "passive"))
      (node (ref "R157") (pin "2") (pinfunction "2_2") (pintype "passive"))
      (node (ref "U7") (pin "5") (pinfunction "*OC_5") (pintype "output"))
    )
    (net (code "185") (name "Net-(U8-VCCI)") (class "Default")
      (node (ref "C36") (pin "2") (pinfunction "2_2") (pintype "passive"))
      (node (ref "U8") (pin "C2") (pinfunction "VCCI_C2") (pintype "bidirectional"))
    )
    (net (code "186") (name "PAUSE_BTN") (class "Default")
      (node (ref "PAUSE") (pin "2") (pinfunction "2_2") (pintype "passive"))
      (node (ref "SIP") (pin "T6") (pinfunction "TIMER5_T6_T6") (pintype "bidirectional"))
    )
    (net (code "187") (name "PMIC_INT") (class "Default")
      (node (ref "SIP") (pin "B18") (pinfunction "EXTINTN_B18") (pintype "bidirectional"))
      (node (ref "SIP") (pin "B19") (pinfunction "PMIC_OUT_NINT_B19") (pintype "output"))
    )
    (net (code "188") (name "PMIC_NWAKEUP") (class "Default")
      (node (ref "SIP") (pin "A19") (pinfunction "PMIC_OUT_NWAKEUP_A19") (pintype "output"))
      (node (ref "SIP") (pin "C5") (pinfunction "EXT_WAKEUP_C5") (pintype "bidirectional"))
    )
    (net (code "189") (name "PMIC_PGOOD") (class "Default")
      (node (ref "SIP") (pin "A20") (pinfunction "PMIC_OUT_PGOOD_A20") (pintype "output"))
      (node (ref "SIP") (pin "B15") (pinfunction "PWRONRSTN_B15") (pintype "bidirectional"))
      (node (ref "U6") (pin "2") (pinfunction "A_2") (pintype "input"))
    )
    (net (code "190") (name "PWM_1A") (class "Default")
      (node (ref "H1") (pin "23") (pinfunction "PWMA_23") (pintype "bidirectional"))
      (node (ref "SIP") (pin "U14") (pinfunction "EHRPWM1A_U14_U14") (pintype "bidirectional"))
    )
    (net (code "191") (name "PWM_1B") (class "Default")
      (node (ref "H1") (pin "15") (pinfunction "PWMB_15") (pintype "bidirectional"))
      (node (ref "SIP") (pin "T14") (pinfunction "EHRPWM1B_T14_T14") (pintype "bidirectional"))
    )
    (net (code "192") (name "PWM_2A") (class "Default")
      (node (ref "H2") (pin "23") (pinfunction "PWMA_23") (pintype "bidirectional"))
      (node (ref "SIP") (pin "U10") (pinfunction "EHRPWM2A_U10_U10") (pintype "bidirectional"))
    )
    (net (code "193") (name "PWM_2B") (class "Default")
      (node (ref "H2") (pin "15") (pinfunction "PWMB_15") (pintype "bidirectional"))
      (node (ref "SIP") (pin "T10") (pinfunction "EHRPWM2B_T10_T10") (pintype "bidirectional"))
    )
    (net (code "194") (name "PWR") (class "Default")
      (node (ref "POWER") (pin "2") (pinfunction "2_2") (pintype "passive"))
      (node (ref "SIP") (pin "D20") (pinfunction "PMIC_IN_PB_IN_D20") (pintype "bidirectional"))
    )
    (net (code "195") (name "PWR_LEDR") (class "Default")
      (node (ref "D8") (pin "C") (pinfunction "C_C") (pintype "passive"))
      (node (ref "R24") (pin "1") (pinfunction "1_1") (pintype "passive"))
    )
    (net (code "196") (name "QEP_0A") (class "Default")
      (node (ref "E1") (pin "3") (pinfunction "3_3") (pintype "bidirectional"))
      (node (ref "R20") (pin "1") (pinfunction "1_1") (pintype "passive"))
      (node (ref "R99") (pin "2") (pinfunction "2_2") (pintype "passive"))
    )
    (net (code "197") (name "QEP_0B") (class "Default")
      (node (ref "E1") (pin "4") (pinfunction "4_4") (pintype "bidirectional"))
      (node (ref "R100") (pin "2") (pinfunction "2_2") (pintype "passive"))
      (node (ref "R18") (pin "1") (pinfunction "1_1") (pintype "passive"))
    )
    (net (code "198") (name "QEP_1A") (class "Default")
      (node (ref "E2") (pin "3") (pinfunction "3_3") (pintype "bidirectional"))
      (node (ref "R146") (pin "2") (pinfunction "2_2") (pintype "passive"))
      (node (ref "R17") (pin "1") (pinfunction "1_1") (pintype "passive"))
    )
    (net (code "199") (name "QEP_1B") (class "Default")
      (node (ref "E2") (pin "4") (pinfunction "4_4") (pintype "bidirectional"))
      (node (ref "R147") (pin "2") (pinfunction "2_2") (pintype "passive"))
      (node (ref "R16") (pin "1") (pinfunction "1_1") (pintype "passive"))
    )
    (net (code "200") (name "QEP_2A") (class "Default")
      (node (ref "E3") (pin "3") (pinfunction "3_3") (pintype "bidirectional"))
      (node (ref "R15") (pin "1") (pinfunction "1_1") (pintype "passive"))
      (node (ref "R95") (pin "2") (pinfunction "2_2") (pintype "passive"))
    )
    (net (code "201") (name "QEP_2B") (class "Default")
      (node (ref "E3") (pin "4") (pinfunction "4_4") (pintype "bidirectional"))
      (node (ref "R9") (pin "1") (pinfunction "1_1") (pintype "passive"))
      (node (ref "R96") (pin "2") (pinfunction "2_2") (pintype "passive"))
    )
    (net (code "202") (name "QEP_4A") (class "Default")
      (node (ref "E4") (pin "3") (pinfunction "3_3") (pintype "bidirectional"))
      (node (ref "R35") (pin "1") (pinfunction "1_1") (pintype "passive"))
      (node (ref "R97") (pin "2") (pinfunction "2_2") (pintype "passive"))
    )
    (net (code "203") (name "QEP_4B") (class "Default")
      (node (ref "E4") (pin "4") (pinfunction "4_4") (pintype "bidirectional"))
      (node (ref "R26") (pin "1") (pinfunction "1_1") (pintype "passive"))
      (node (ref "R98") (pin "2") (pinfunction "2_2") (pintype "passive"))
    )
    (net (code "204") (name "RESET") (class "Default")
      (node (ref "C33") (pin "1") (pinfunction "1_1") (pintype "passive"))
      (node (ref "R60") (pin "1") (pinfunction "1_1") (pintype "passive"))
      (node (ref "RESET") (pin "2") (pinfunction "2_2") (pintype "passive"))
      (node (ref "SIP") (pin "A10") (pinfunction "WARMRSTN_A10") (pintype "bidirectional"))
      (node (ref "U6") (pin "4") (pinfunction "Y_4") (pintype "output"))
    )
    (net (code "205") (name "SERVO_EN") (class "Default")
      (node (ref "6V_REG") (pin "8") (pinfunction "EN_8") (pintype "bidirectional"))
      (node (ref "R133") (pin "2") (pinfunction "2_2") (pintype "passive"))
      (node (ref "R46") (pin "2") (pinfunction "2_2") (pintype "passive"))
      (node (ref "SIP") (pin "U3") (pinfunction "LCD_DATA10_U3_U3") (pintype "bidirectional"))
    )
    (net (code "206") (name "SPI1_MISO") (class "Default")
      (node (ref "R102") (pin "2") (pinfunction "2_2") (pintype "passive"))
      (node (ref "SPI1.1") (pin "4") (pinfunction "4_4") (pintype "bidirectional"))
      (node (ref "SPI1.2") (pin "4") (pinfunction "4_4") (pintype "bidirectional"))
    )
    (net (code "207") (name "SPI1_MOSI") (class "Default")
      (node (ref "R103") (pin "2") (pinfunction "2_2") (pintype "passive"))
      (node (ref "SPI1.1") (pin "3") (pinfunction "3_3") (pintype "bidirectional"))
      (node (ref "SPI1.2") (pin "3") (pinfunction "3_3") (pintype "bidirectional"))
    )
    (net (code "208") (name "SPI1_SCK") (class "Default")
      (node (ref "R101") (pin "2") (pinfunction "2_2") (pintype "passive"))
      (node (ref "SPI1.1") (pin "5") (pinfunction "5_5") (pintype "bidirectional"))
      (node (ref "SPI1.2") (pin "5") (pinfunction "5_5") (pintype "bidirectional"))
    )
    (net (code "209") (name "SPI1_SS1") (class "Default")
      (node (ref "R104") (pin "2") (pinfunction "2_2") (pintype "passive"))
      (node (ref "SPI1.1") (pin "6") (pinfunction "6_6") (pintype "bidirectional"))
    )
    (net (code "210") (name "SPI1_SS2") (class "Default")
      (node (ref "R82") (pin "2") (pinfunction "2_2") (pintype "passive"))
      (node (ref "SPI1.2") (pin "6") (pinfunction "6_6") (pintype "bidirectional"))
    )
    (net (code "211") (name "SVO1") (class "Default")
      (node (ref "R36") (pin "1") (pinfunction "1_1") (pintype "passive"))
      (node (ref "R50") (pin "1") (pinfunction "1_1") (pintype "passive"))
      (node (ref "SIP") (pin "U5") (pinfunction "LCD_VSYNC_U5_U5") (pintype "bidirectional"))
    )
    (net (code "212") (name "SVO2") (class "Default")
      (node (ref "R37") (pin "1") (pinfunction "1_1") (pintype "passive"))
      (node (ref "R51") (pin "1") (pinfunction "1_1") (pintype "passive"))
      (node (ref "SIP") (pin "V5") (pinfunction "LCD_PCLK_V5_V5") (pintype "bidirectional"))
    )
    (net (code "213") (name "SVO3") (class "Default")
      (node (ref "R38") (pin "1") (pinfunction "1_1") (pintype "passive"))
      (node (ref "R52") (pin "1") (pinfunction "1_1") (pintype "passive"))
      (node (ref "SIP") (pin "R5") (pinfunction "LCD_HSYNC_R5_R5") (pintype "bidirectional"))
    )
    (net (code "214") (name "SVO4") (class "Default")
      (node (ref "R39") (pin "1") (pinfunction "1_1") (pintype "passive"))
      (node (ref "R53") (pin "1") (pinfunction "1_1") (pintype "passive"))
      (node (ref "SIP") (pin "R6") (pinfunction "LCD_DE_R6_R6") (pintype "bidirectional"))
    )
    (net (code "215") (name "SVO5") (class "Default")
      (node (ref "R125") (pin "2") (pinfunction "2_2") (pintype "passive"))
      (node (ref "R40") (pin "1") (pinfunction "1_1") (pintype "passive"))
      (node (ref "R54") (pin "2") (pinfunction "2_2") (pintype "passive"))
      (node (ref "SIP") (pin "T3") (pinfunction "LCD_DATA6_T3_T3") (pintype "bidirectional"))
    )
    (net (code "216") (name "SVO6") (class "Default")
      (node (ref "R127") (pin "2") (pinfunction "2_2") (pintype "passive"))
      (node (ref "R41") (pin "1") (pinfunction "1_1") (pintype "passive"))
      (node (ref "R55") (pin "2") (pinfunction "2_2") (pintype "passive"))
      (node (ref "SIP") (pin "T4") (pinfunction "LCD_DATA7_T4_T4") (pintype "bidirectional"))
    )
    (net (code "217") (name "SVO7") (class "Default")
      (node (ref "R120") (pin "1") (pinfunction "1_1") (pintype "passive"))
      (node (ref "R42") (pin "1") (pinfunction "1_1") (pintype "passive"))
      (node (ref "R56") (pin "2") (pinfunction "2_2") (pintype "passive"))
      (node (ref "SIP") (pin "T1") (pinfunction "LCD_DATA4_T1_T1") (pintype "bidirectional"))
    )
    (net (code "218") (name "SVO8") (class "Default")
      (node (ref "R122") (pin "1") (pinfunction "1_1") (pintype "passive"))
      (node (ref "R43") (pin "1") (pinfunction "1_1") (pintype "passive"))
      (node (ref "R57") (pin "2") (pinfunction "2_2") (pintype "passive"))
      (node (ref "SIP") (pin "T2") (pinfunction "LCD_DATA5_T2_T2") (pintype "bidirectional"))
    )
    (net (code "219") (name "SYS_5V") (class "Default")
      (node (ref "R153") (pin "1") (pinfunction "1_1") (pintype "passive"))
      (node (ref "SIP") (pin "W4") (pinfunction "VOUT_SYS_5V_0_W4") (pintype "power_in"))
      (node (ref "SIP") (pin "Y4") (pinfunction "VOUT_SYS_5V_1_Y4") (pintype "power_in"))
      (node (ref "TP1") (pin "TP") (pinfunction "TP_TP") (pintype "input"))
    )
    (net (code "220") (name "UART0_RX") (class "Default")
      (node (ref "R77") (pin "1") (pinfunction "1_1") (pintype "passive"))
      (node (ref "UART0") (pin "3") (pinfunction "3_3") (pintype "bidirectional"))
    )
    (net (code "221") (name "UART0_TX") (class "Default")
      (node (ref "R76") (pin "1") (pinfunction "1_1") (pintype "passive"))
      (node (ref "UART0") (pin "4") (pinfunction "4_4") (pintype "bidirectional"))
    )
    (net (code "222") (name "UART1_RX") (class "Default")
      (node (ref "R79") (pin "1") (pinfunction "1_1") (pintype "passive"))
      (node (ref "UART1") (pin "3") (pinfunction "3_3") (pintype "bidirectional"))
    )
    (net (code "223") (name "UART1_TX") (class "Default")
      (node (ref "R78") (pin "1") (pinfunction "1_1") (pintype "passive"))
      (node (ref "UART1") (pin "4") (pinfunction "4_4") (pintype "bidirectional"))
    )
    (net (code "224") (name "UART2_RX") (class "Default")
      (node (ref "GPS") (pin "3") (pinfunction "3_3") (pintype "bidirectional"))
      (node (ref "R72") (pin "1") (pinfunction "1_1") (pintype "passive"))
    )
    (net (code "225") (name "UART2_TX") (class "Default")
      (node (ref "GPS") (pin "4") (pinfunction "4_4") (pintype "bidirectional"))
      (node (ref "R73") (pin "1") (pinfunction "1_1") (pintype "passive"))
    )
    (net (code "226") (name "UART4_RX") (class "Default")
      (node (ref "DSM2") (pin "3") (pinfunction "3_3") (pintype "bidirectional"))
      (node (ref "R83") (pin "2") (pinfunction "2_2") (pintype "passive"))
    )
    (net (code "227") (name "UART5_RX") (class "Default")
      (node (ref "R145") (pin "2") (pinfunction "2_2") (pintype "passive"))
      (node (ref "UART5") (pin "3") (pinfunction "3_3") (pintype "bidirectional"))
    )
    (net (code "228") (name "UART5_TX") (class "Default")
      (node (ref "R144") (pin "2") (pinfunction "2_2") (pintype "passive"))
      (node (ref "UART5") (pin "4") (pinfunction "4_4") (pintype "bidirectional"))
    )
    (net (code "229") (name "USB_DC") (class "Default")
      (node (ref "R154") (pin "2") (pinfunction "2_2") (pintype "passive"))
      (node (ref "SIP") (pin "Y8") (pinfunction "VIN_USB_0_Y8") (pintype "power_in"))
      (node (ref "SIP") (pin "Y9") (pinfunction "VIN_USB_1_Y9") (pintype "power_in"))
    )
    (net (code "230") (name "VCC") (class "Default")
      (node (ref "C12") (pin "1") (pinfunction "1_1") (pintype "passive"))
      (node (ref "C7") (pin "1") (pinfunction "1_1") (pintype "passive"))
      (node (ref "CHG") (pin "A") (pinfunction "A_A") (pintype "passive"))
      (node (ref "CHGIC") (pin "2") (pinfunction "VIN_2") (pintype "bidirectional"))
      (node (ref "D3") (pin "A") (pinfunction "A_A") (pintype "passive"))
      (node (ref "JACK") (pin "1") (pinfunction "1_1") (pintype "passive"))
      (node (ref "R1") (pin "1") (pinfunction "1_1") (pintype "passive"))
    )
    (net (code "231") (name "VCC_3V3B") (class "Default")
      (node (ref "C34") (pin "2") (pinfunction "2_2") (pintype "passive"))
      (node (ref "C35") (pin "2") (pinfunction "2_2") (pintype "passive"))
      (node (ref "P10") (pin "4") (pinfunction "VDD_4") (pintype "bidirectional"))
      (node (ref "R65") (pin "1") (pinfunction "1_1") (pintype "passive"))
      (node (ref "R66") (pin "1") (pinfunction "1_1") (pintype "passive"))
      (node (ref "R67") (pin "1") (pinfunction "1_1") (pintype "passive"))
      (node (ref "R68") (pin "1") (pinfunction "1_1") (pintype "passive"))
      (node (ref "R69") (pin "1") (pinfunction "1_1") (pintype "passive"))
      (node (ref "R70") (pin "1") (pinfunction "1_1") (pintype "passive"))
      (node (ref "R71") (pin "1") (pinfunction "1_1") (pintype "passive"))
    )
    (net (code "232") (name "VCC_CHG") (class "Default")
      (node (ref "C4") (pin "2") (pinfunction "2_2") (pintype "passive"))
      (node (ref "CHGIC") (pin "3") (pinfunction "VCC_3") (pintype "bidirectional"))
      (node (ref "CHGIC") (pin "5") (pinfunction "SEL_5") (pintype "bidirectional"))
      (node (ref "R5") (pin "2") (pinfunction "2_2") (pintype "passive"))
    )
    (net (code "233") (name "VDD_1V8") (class "Default")
      (node (ref "SIP") (pin "D10") (pinfunction "VDD_1V84_D10") (pintype "bidirectional"))
      (node (ref "SIP") (pin "E9") (pinfunction "VDD_1V83_E9") (pintype "bidirectional"))
      (node (ref "SIP") (pin "N16") (pinfunction "VOUT_LDO3_1P8V_0_N16") (pintype "power_in"))
      (node (ref "SIP") (pin "R16") (pinfunction "VOUT_LDO3_1P8V_1_R16") (pintype "power_in"))
    )
    (net (code "234") (name "VDD_3V3A") (class "Default")
      (node (ref "C28") (pin "1") (pinfunction "1_1") (pintype "passive"))
      (node (ref "R116") (pin "2") (pinfunction "2_2") (pintype "passive"))
      (node (ref "R118") (pin "2") (pinfunction "2_2") (pintype "passive"))
      (node (ref "R120") (pin "2") (pinfunction "2_2") (pintype "passive"))
      (node (ref "R122") (pin "2") (pinfunction "2_2") (pintype "passive"))
      (node (ref "R140") (pin "2") (pinfunction "2_2") (pintype "passive"))
      (node (ref "R157") (pin "1") (pinfunction "1_1") (pintype "passive"))
      (node (ref "R2") (pin "2") (pinfunction "2_2") (pintype "passive"))
      (node (ref "R23") (pin "2") (pinfunction "2_2") (pintype "passive"))
      (node (ref "R58") (pin "2") (pinfunction "2_2") (pintype "passive"))
      (node (ref "R60") (pin "2") (pinfunction "2_2") (pintype "passive"))
      (node (ref "SIP") (pin "E10") (pinfunction "VDD_3V3A1_E10") (pintype "bidirectional"))
      (node (ref "SIP") (pin "E11") (pinfunction "VDD_3V3A2_E11") (pintype "bidirectional"))
      (node (ref "SIP") (pin "E12") (pinfunction "VDD_3V3A3_E12") (pintype "bidirectional"))
      (node (ref "SIP") (pin "E13") (pinfunction "VDD_3V3A4_E13") (pintype "bidirectional"))
      (node (ref "SIP") (pin "F14") (pinfunction "VDD_3V3A5_F14") (pintype "bidirectional"))
      (node (ref "SIP") (pin "G14") (pinfunction "VDD_3V3A6_G14") (pintype "bidirectional"))
      (node (ref "SIP") (pin "H14") (pinfunction "VDD_3V3A7_H14") (pintype "bidirectional"))
      (node (ref "SIP") (pin "J14") (pinfunction "VDD_3V3A8_J14") (pintype "bidirectional"))
      (node (ref "SIP") (pin "K14") (pinfunction "VDD_3V3A9_K14") (pintype "bidirectional"))
      (node (ref "SIP") (pin "L14") (pinfunction "VDD_3V3A10_L14") (pintype "bidirectional"))
      (node (ref "SIP") (pin "N15") (pinfunction "VDD_3V3A12_N15") (pintype "bidirectional"))
      (node (ref "SIP") (pin "N5") (pinfunction "VDD_3V3A11_N5") (pintype "bidirectional"))
      (node (ref "SIP") (pin "P10") (pinfunction "VDD_3V3A17_P10") (pintype "bidirectional"))
      (node (ref "SIP") (pin "P11") (pinfunction "VDD_3V3A18_P11") (pintype "bidirectional"))
      (node (ref "SIP") (pin "P12") (pinfunction "VDD_3V3A19_P12") (pintype "bidirectional"))
      (node (ref "SIP") (pin "P13") (pinfunction "VDD_3V3A20_P13") (pintype "bidirectional"))
      (node (ref "SIP") (pin "P5") (pinfunction "VDD_3V3A13_P5") (pintype "bidirectional"))
      (node (ref "SIP") (pin "P6") (pinfunction "VDD_3V3A14_P6") (pintype "bidirectional"))
      (node (ref "SIP") (pin "P7") (pinfunction "VDD_3V3A15_P7") (pintype "bidirectional"))
      (node (ref "SIP") (pin "P8") (pinfunction "VDD_3V3A16_P8") (pintype "bidirectional"))
      (node (ref "SIP") (pin "R15") (pinfunction "VDD_3V3A21_R15") (pintype "bidirectional"))
      (node (ref "U5") (pin "4") (pinfunction "VCC_4") (pintype "power_in"))
    )
    (net (code "235") (name "VDD_3V3AUX") (class "Default")
      (node (ref "D8") (pin "A") (pinfunction "A_A") (pintype "passive"))
      (node (ref "SIP") (pin "Y11") (pinfunction "VOUT_LDO2_3P3V_Y11") (pintype "power_in"))
    )
    (net (code "236") (name "VDD_3V3B") (class "Default")
      (node (ref "C27") (pin "1") (pinfunction "1_1") (pintype "passive"))
      (node (ref "C37") (pin "1") (pinfunction "1_1") (pintype "passive"))
      (node (ref "C38") (pin "1") (pinfunction "1_1") (pintype "passive"))
      (node (ref "C39") (pin "1") (pinfunction "1_1") (pintype "passive"))
      (node (ref "C40") (pin "1") (pinfunction "1_1") (pintype "passive"))
      (node (ref "C41") (pin "1") (pinfunction "1_1") (pintype "passive"))
      (node (ref "R109") (pin "1") (pinfunction "1_1") (pintype "passive"))
      (node (ref "R84") (pin "2") (pinfunction "2_2") (pintype "passive"))
      (node (ref "R85") (pin "2") (pinfunction "2_2") (pintype "passive"))
      (node (ref "R86") (pin "2") (pinfunction "2_2") (pintype "passive"))
      (node (ref "R87") (pin "2") (pinfunction "2_2") (pintype "passive"))
      (node (ref "R88") (pin "2") (pinfunction "2_2") (pintype "passive"))
      (node (ref "R89") (pin "2") (pinfunction "2_2") (pintype "passive"))
      (node (ref "R90") (pin "2") (pinfunction "2_2") (pintype "passive"))
      (node (ref "R91") (pin "2") (pinfunction "2_2") (pintype "passive"))
      (node (ref "R92") (pin "2") (pinfunction "2_2") (pintype "passive"))
      (node (ref "R93") (pin "2") (pinfunction "2_2") (pintype "passive"))
      (node (ref "R94") (pin "2") (pinfunction "2_2") (pintype "passive"))
      (node (ref "SIP") (pin "U20") (pinfunction "VOUT_USER_3P3V_0_U20") (pintype "power_in"))
      (node (ref "SIP") (pin "V20") (pinfunction "VOUT_USER_3P3V_1_V20") (pintype "power_in"))
      (node (ref "U8") (pin "C6") (pinfunction "VCCQ4_C6") (pintype "bidirectional"))
      (node (ref "U8") (pin "E6") (pinfunction "VCC3_E6") (pintype "bidirectional"))
      (node (ref "U8") (pin "F5") (pinfunction "VCC2_F5") (pintype "bidirectional"))
      (node (ref "U8") (pin "J10") (pinfunction "VCC0_J10") (pintype "bidirectional"))
      (node (ref "U8") (pin "K9") (pinfunction "VCC1_K9") (pintype "bidirectional"))
      (node (ref "U8") (pin "M4") (pinfunction "VCCQ5_M4") (pintype "bidirectional"))
      (node (ref "U8") (pin "N4") (pinfunction "VCCQ3_N4") (pintype "bidirectional"))
      (node (ref "U8") (pin "P3") (pinfunction "VCCQ1_P3") (pintype "bidirectional"))
      (node (ref "U8") (pin "P5") (pinfunction "VCCQ2_P5") (pintype "bidirectional"))
    )
    (net (code "237") (name "VDD_ADC") (class "Default")
      (node (ref "ADC") (pin "2") (pinfunction "2_2") (pintype "bidirectional"))
      (node (ref "C44") (pin "1") (pinfunction "1_1") (pintype "passive"))
      (node (ref "R111") (pin "1") (pinfunction "1_1") (pintype "passive"))
      (node (ref "SIP") (pin "A4") (pinfunction "VOUT_ADC_1P8V_0_A4") (pintype "bidirectional"))
      (node (ref "SIP") (pin "A5") (pinfunction "VOUT_ADC_1P8V_1_A5") (pintype "bidirectional"))
      (node (ref "SIP") (pin "D8") (pinfunction "VDDA_ADC_D8") (pintype "bidirectional"))
    )
    (net (code "238") (name "VDD_RTC") (class "Default")
      (node (ref "SIP") (pin "D7") (pinfunction "VDD_RTC1_D7") (pintype "bidirectional"))
      (node (ref "SIP") (pin "E14") (pinfunction "VDD_RTC3_E14") (pintype "bidirectional"))
      (node (ref "SIP") (pin "E6") (pinfunction "VDD_RTC2_E6") (pintype "bidirectional"))
      (node (ref "SIP") (pin "F9") (pinfunction "VDD_RTC4_F9") (pintype "bidirectional"))
      (node (ref "SIP") (pin "K13") (pinfunction "VDD_RTC5_K13") (pintype "bidirectional"))
      (node (ref "SIP") (pin "N6") (pinfunction "VDD_RTC6_N6") (pintype "bidirectional"))
      (node (ref "SIP") (pin "P14") (pinfunction "VDD_RTC8_P14") (pintype "bidirectional"))
      (node (ref "SIP") (pin "P9") (pinfunction "VDD_RTC7_P9") (pintype "bidirectional"))
      (node (ref "U6") (pin "5") (pinfunction "VCC_5") (pintype "power_in"))
    )
    (net (code "239") (name "V_BATT") (class "Default")
      (node (ref "6V_REG") (pin "9") (pinfunction "VIN_9") (pintype "bidirectional"))
      (node (ref "C11") (pin "+") (pinfunction "+_+") (pintype "passive"))
      (node (ref "C20") (pin "2") (pinfunction "2_2") (pintype "passive"))
      (node (ref "C25") (pin "1") (pinfunction "1_1") (pintype "passive"))
      (node (ref "C26") (pin "1") (pinfunction "1_1") (pintype "passive"))
      (node (ref "CHGIC") (pin "9") (pinfunction "BATT_9") (pintype "bidirectional"))
      (node (ref "D2") (pin "A") (pinfunction "A_A") (pintype "passive"))
      (node (ref "H1") (pin "13") (pinfunction "VM2_13") (pintype "bidirectional"))
      (node (ref "H1") (pin "14") (pinfunction "VM3_14") (pintype "bidirectional"))
      (node (ref "H1") (pin "24") (pinfunction "VM1_24") (pintype "bidirectional"))
      (node (ref "H2") (pin "13") (pinfunction "VM2_13") (pintype "bidirectional"))
      (node (ref "H2") (pin "14") (pinfunction "VM3_14") (pintype "bidirectional"))
      (node (ref "H2") (pin "24") (pinfunction "VM1_24") (pintype "bidirectional"))
      (node (ref "LIPO") (pin "P$1") (pinfunction "1_P$1") (pintype "passive"))
      (node (ref "R19") (pin "1") (pinfunction "1_1") (pintype "passive"))
      (node (ref "R28") (pin "1") (pinfunction "1_1") (pintype "passive"))
      (node (ref "R34") (pin "1") (pinfunction "1_1") (pintype "passive"))
      (node (ref "R4") (pin "1") (pinfunction "1_1") (pintype "passive"))
    )
    (net (code "240") (name "V_DIV_BAT") (class "Default")
      (node (ref "R19") (pin "2") (pinfunction "2_2") (pintype "passive"))
      (node (ref "R25") (pin "1") (pinfunction "1_1") (pintype "passive"))
      (node (ref "SIP") (pin "A8") (pinfunction "AIN6_A8") (pintype "bidirectional"))
    )
    (net (code "241") (name "V_DIV_DC") (class "Default")
      (node (ref "R1") (pin "2") (pinfunction "2_2") (pintype "passive"))
      (node (ref "R14") (pin "1") (pinfunction "1_1") (pintype "passive"))
      (node (ref "SIP") (pin "B8") (pinfunction "AIN5_B8") (pintype "bidirectional"))
    )
    (net (code "242") (name "unconnected-(CHGIC-ACOK-Pad12)") (class "Default")
      (node (ref "CHGIC") (pin "12") (pinfunction "ACOK_12") (pintype "bidirectional"))
    )
    (net (code "243") (name "unconnected-(CHGIC-CELL-Pad4)") (class "Default")
      (node (ref "CHGIC") (pin "4") (pinfunction "CELL_4") (pintype "bidirectional"))
    )
    (net (code "244") (name "unconnected-(GPS-Pad1)") (class "Default")
      (node (ref "GPS") (pin "1") (pinfunction "1_1") (pintype "bidirectional"))
    )
    (net (code "245") (name "unconnected-(IMU-AUX_CL-Pad7)") (class "Default")
      (node (ref "IMU") (pin "7") (pinfunction "AUX_CL_7") (pintype "bidirectional"))
    )
    (net (code "246") (name "unconnected-(IMU-AUX_DA-Pad21)") (class "Default")
      (node (ref "IMU") (pin "21") (pinfunction "AUX_DA_21") (pintype "bidirectional"))
    )
    (net (code "247") (name "unconnected-(IMU-FSYNC-Pad11)") (class "Default")
      (node (ref "IMU") (pin "11") (pinfunction "FSYNC_11") (pintype "bidirectional"))
    )
    (net (code "248") (name "unconnected-(IMU-NC-Pad2)") (class "Default")
      (node (ref "IMU") (pin "2") (pinfunction "NC_2") (pintype "bidirectional"))
    )
    (net (code "249") (name "unconnected-(IMU-NC-Pad3)") (class "Default")
      (node (ref "IMU") (pin "3") (pinfunction "NC_3") (pintype "bidirectional"))
    )
    (net (code "250") (name "unconnected-(IMU-NC-Pad4)") (class "Default")
      (node (ref "IMU") (pin "4") (pinfunction "NC_4") (pintype "bidirectional"))
    )
    (net (code "251") (name "unconnected-(IMU-NC-Pad5)") (class "Default")
      (node (ref "IMU") (pin "5") (pinfunction "NC_5") (pintype "bidirectional"))
    )
    (net (code "252") (name "unconnected-(IMU-NC-Pad6)") (class "Default")
      (node (ref "IMU") (pin "6") (pinfunction "NC_6") (pintype "bidirectional"))
    )
    (net (code "253") (name "unconnected-(IMU-NC-Pad14)") (class "Default")
      (node (ref "IMU") (pin "14") (pinfunction "NC_14") (pintype "bidirectional"))
    )
    (net (code "254") (name "unconnected-(IMU-NC-Pad15)") (class "Default")
      (node (ref "IMU") (pin "15") (pinfunction "NC_15") (pintype "bidirectional"))
    )
    (net (code "255") (name "unconnected-(IMU-NC-Pad16)") (class "Default")
      (node (ref "IMU") (pin "16") (pinfunction "NC_16") (pintype "bidirectional"))
    )
    (net (code "256") (name "unconnected-(IMU-NC-Pad17)") (class "Default")
      (node (ref "IMU") (pin "17") (pinfunction "NC_17") (pintype "bidirectional"))
    )
    (net (code "257") (name "unconnected-(IMU-RESV-Pad19)") (class "Default")
      (node (ref "IMU") (pin "19") (pinfunction "RESV_19") (pintype "bidirectional"))
    )
    (net (code "258") (name "unconnected-(PROT-CO-Pad3)") (class "Default")
      (node (ref "PROT") (pin "3") (pinfunction "CO_3") (pintype "bidirectional"))
    )
    (net (code "259") (name "unconnected-(PROT-DP-Pad4)") (class "Default")
      (node (ref "PROT") (pin "4") (pinfunction "DP_4") (pintype "bidirectional"))
    )
    (net (code "260") (name "unconnected-(SIP-PadH16)") (class "Default")
      (node (ref "SIP") (pin "H16") (pinfunction "H16_H16") (pintype "bidirectional"))
    )
    (net (code "261") (name "unconnected-(SIP-PadH17)") (class "Default")
      (node (ref "SIP") (pin "H17") (pinfunction "H17_H17") (pintype "bidirectional"))
    )
    (net (code "262") (name "unconnected-(SIP-PadH18)") (class "Default")
      (node (ref "SIP") (pin "H18") (pinfunction "H18_H18") (pintype "bidirectional"))
    )
    (net (code "263") (name "unconnected-(SIP-PadJ15)") (class "Default")
      (node (ref "SIP") (pin "J15") (pinfunction "J15_J15") (pintype "bidirectional"))
    )
    (net (code "264") (name "unconnected-(SIP-PadJ16)") (class "Default")
      (node (ref "SIP") (pin "J16") (pinfunction "J16_J16") (pintype "bidirectional"))
    )
    (net (code "265") (name "unconnected-(SIP-PadJ17)") (class "Default")
      (node (ref "SIP") (pin "J17") (pinfunction "J17_J17") (pintype "bidirectional"))
    )
    (net (code "266") (name "unconnected-(SIP-PadJ18)") (class "Default")
      (node (ref "SIP") (pin "J18") (pinfunction "J18_J18") (pintype "bidirectional"))
    )
    (net (code "267") (name "unconnected-(SIP-PadK15)") (class "Default")
      (node (ref "SIP") (pin "K15") (pinfunction "K15_K15") (pintype "bidirectional"))
    )
    (net (code "268") (name "unconnected-(SIP-PadK16)") (class "Default")
      (node (ref "SIP") (pin "K16") (pinfunction "K16_K16") (pintype "bidirectional"))
    )
    (net (code "269") (name "unconnected-(SIP-PadK17)") (class "Default")
      (node (ref "SIP") (pin "K17") (pinfunction "K17_K17") (pintype "bidirectional"))
    )
    (net (code "270") (name "unconnected-(SIP-PadK18)") (class "Default")
      (node (ref "SIP") (pin "K18") (pinfunction "K18_K18") (pintype "bidirectional"))
    )
    (net (code "271") (name "unconnected-(SIP-PadL15)") (class "Default")
      (node (ref "SIP") (pin "L15") (pinfunction "L15_L15") (pintype "bidirectional"))
    )
    (net (code "272") (name "unconnected-(SIP-PadL16)") (class "Default")
      (node (ref "SIP") (pin "L16") (pinfunction "L16_L16") (pintype "bidirectional"))
    )
    (net (code "273") (name "unconnected-(SIP-PadL17)") (class "Default")
      (node (ref "SIP") (pin "L17") (pinfunction "L17_L17") (pintype "bidirectional"))
    )
    (net (code "274") (name "unconnected-(SIP-PadL18)") (class "Default")
      (node (ref "SIP") (pin "L18") (pinfunction "L18_L18") (pintype "bidirectional"))
    )
    (net (code "275") (name "unconnected-(SIP-PadM16)") (class "Default")
      (node (ref "SIP") (pin "M16") (pinfunction "M16_M16") (pintype "bidirectional"))
    )
    (net (code "276") (name "unconnected-(SIP-PadM17)") (class "Default")
      (node (ref "SIP") (pin "M17") (pinfunction "M17_M17") (pintype "bidirectional"))
    )
    (net (code "277") (name "unconnected-(SIP-PadM18)") (class "Default")
      (node (ref "SIP") (pin "M18") (pinfunction "M18_M18") (pintype "bidirectional"))
    )
    (net (code "278") (name "unconnected-(SIPB-GPIO0_7_C18-PadC18)") (class "Default")
      (node (ref "SIP") (pin "C18") (pinfunction "GPIO0_7_C18_C18") (pintype "bidirectional"))
    )
    (net (code "279") (name "unconnected-(SIPB-GPIO1_17_V14-PadV14)") (class "Default")
      (node (ref "SIP") (pin "V14") (pinfunction "GPIO1_17_V14_V14") (pintype "bidirectional"))
    )
    (net (code "280") (name "unconnected-(SIPB-GPIO1_28_U18-PadU18)") (class "Default")
      (node (ref "SIP") (pin "U18") (pinfunction "GPIO1_28_U18_U18") (pintype "bidirectional"))
    )
    (net (code "281") (name "unconnected-(SIPB-GPIO2_0_T13-PadT13)") (class "Default")
      (node (ref "SIP") (pin "T13") (pinfunction "GPIO2_0_T13_T13") (pintype "bidirectional"))
    )
    (net (code "282") (name "unconnected-(SIPB-GPIO2_1_V12-PadV12)") (class "Default")
      (node (ref "SIP") (pin "V12") (pinfunction "GPIO2_1_V12_V12") (pintype "bidirectional"))
    )
    (net (code "283") (name "unconnected-(SIPB-GPIO3_20_D13-PadD13)") (class "Default")
      (node (ref "SIP") (pin "D13") (pinfunction "GPIO3_20_D13_D13") (pintype "bidirectional"))
    )
    (net (code "284") (name "unconnected-(SIPB-UART0_CTSN_E18-PadE18)") (class "Default")
      (node (ref "SIP") (pin "E18") (pinfunction "UART0_CTSN_E18_E18") (pintype "bidirectional"))
    )
    (net (code "285") (name "unconnected-(SIPC-AIN4-PadC8)") (class "Default")
      (node (ref "SIP") (pin "C8") (pinfunction "AIN4_C8") (pintype "bidirectional"))
    )
    (net (code "286") (name "unconnected-(SIPC-HDMIDIS_GPIO1_27_V17-PadV17)") (class "Default")
      (node (ref "SIP") (pin "V17") (pinfunction "HDMIDIS_GPIO1_27_V17_V17") (pintype "bidirectional"))
    )
    (net (code "287") (name "unconnected-(SIPC-HDMIINT_GPIO1_25_U16-PadU16)") (class "Default")
      (node (ref "SIP") (pin "U16") (pinfunction "HDMIINT_GPIO1_25_U16_U16") (pintype "bidirectional"))
    )
    (net (code "288") (name "unconnected-(SIPC-USB0_CE-PadM15)") (class "Default")
      (node (ref "SIP") (pin "M15") (pinfunction "USB0_CE_M15") (pintype "bidirectional"))
    )
    (net (code "289") (name "unconnected-(SIPC-USB0_DRVVBUS-PadF16)") (class "Default")
      (node (ref "SIP") (pin "F16") (pinfunction "USB0_DRVVBUS_F16") (pintype "bidirectional"))
    )
    (net (code "290") (name "unconnected-(SIPC-USB1_CE-PadP18)") (class "Default")
      (node (ref "SIP") (pin "P18") (pinfunction "USB1_CE_P18") (pintype "bidirectional"))
    )
    (net (code "291") (name "unconnected-(SIPE-CAP_VBB_MPU-PadC10)") (class "Default")
      (node (ref "SIP") (pin "C10") (pinfunction "CAP_VBB_MPU_C10") (pintype "bidirectional"))
    )
    (net (code "292") (name "unconnected-(SIPE-CAP_VDD_RTC-PadD6)") (class "Default")
      (node (ref "SIP") (pin "D6") (pinfunction "CAP_VDD_RTC_D6") (pintype "bidirectional"))
    )
    (net (code "293") (name "unconnected-(SIPE-CAP_VDD_SRAM_COR-PadD9)") (class "Default")
      (node (ref "SIP") (pin "D9") (pinfunction "CAP_VDD_SRAM_COR_D9") (pintype "bidirectional"))
    )
    (net (code "294") (name "unconnected-(SIPE-CAP_VDD_SRAM_MPU-PadD11)") (class "Default")
      (node (ref "SIP") (pin "D11") (pinfunction "CAP_VDD_SRAM_MPU_D11") (pintype "bidirectional"))
    )
    (net (code "295") (name "unconnected-(SIPE-TESTOUT-PadA3)") (class "Default")
      (node (ref "SIP") (pin "A3") (pinfunction "TESTOUT_A3") (pintype "bidirectional"))
    )
    (net (code "296") (name "unconnected-(SIPE-VDDS_DDR1-PadE5)") (class "Default")
      (node (ref "SIP") (pin "E5") (pinfunction "VDDS_DDR1_E5") (pintype "bidirectional"))
    )
    (net (code "297") (name "unconnected-(SIPE-VDDS_DDR2-PadF5)") (class "Default")
      (node (ref "SIP") (pin "F5") (pinfunction "VDDS_DDR2_F5") (pintype "bidirectional"))
    )
    (net (code "298") (name "unconnected-(SIPE-VDDS_DDR3-PadG5)") (class "Default")
      (node (ref "SIP") (pin "G5") (pinfunction "VDDS_DDR3_G5") (pintype "bidirectional"))
    )
    (net (code "299") (name "unconnected-(SIPE-VDDS_DDR4-PadH5)") (class "Default")
      (node (ref "SIP") (pin "H5") (pinfunction "VDDS_DDR4_H5") (pintype "bidirectional"))
    )
    (net (code "300") (name "unconnected-(SIPE-VDDS_DDR5-PadJ5)") (class "Default")
      (node (ref "SIP") (pin "J5") (pinfunction "VDDS_DDR5_J5") (pintype "bidirectional"))
    )
    (net (code "301") (name "unconnected-(SIPE-VDDS_DDR6-PadK5)") (class "Default")
      (node (ref "SIP") (pin "K5") (pinfunction "VDDS_DDR6_K5") (pintype "bidirectional"))
    )
    (net (code "302") (name "unconnected-(SIPE-VDDS_DDR7-PadL5)") (class "Default")
      (node (ref "SIP") (pin "L5") (pinfunction "VDDS_DDR7_L5") (pintype "bidirectional"))
    )
    (net (code "303") (name "unconnected-(SIPE-VDD_CORE1-PadF6)") (class "Default")
      (node (ref "SIP") (pin "F6") (pinfunction "VDD_CORE1_F6") (pintype "bidirectional"))
    )
    (net (code "304") (name "unconnected-(SIPE-VDD_CORE2-PadF7)") (class "Default")
      (node (ref "SIP") (pin "F7") (pinfunction "VDD_CORE2_F7") (pintype "bidirectional"))
    )
    (net (code "305") (name "unconnected-(SIPE-VDD_CORE3-PadG6)") (class "Default")
      (node (ref "SIP") (pin "G6") (pinfunction "VDD_CORE3_G6") (pintype "bidirectional"))
    )
    (net (code "306") (name "unconnected-(SIPE-VDD_CORE4-PadG7)") (class "Default")
      (node (ref "SIP") (pin "G7") (pinfunction "VDD_CORE4_G7") (pintype "bidirectional"))
    )
    (net (code "307") (name "unconnected-(SIPE-VDD_CORE5-PadG10)") (class "Default")
      (node (ref "SIP") (pin "G10") (pinfunction "VDD_CORE5_G10") (pintype "bidirectional"))
    )
    (net (code "308") (name "unconnected-(SIPE-VDD_CORE6-PadH11)") (class "Default")
      (node (ref "SIP") (pin "H11") (pinfunction "VDD_CORE6_H11") (pintype "bidirectional"))
    )
    (net (code "309") (name "unconnected-(SIPE-VDD_CORE7-PadJ12)") (class "Default")
      (node (ref "SIP") (pin "J12") (pinfunction "VDD_CORE7_J12") (pintype "bidirectional"))
    )
    (net (code "310") (name "unconnected-(SIPE-VDD_CORE8-PadK6)") (class "Default")
      (node (ref "SIP") (pin "K6") (pinfunction "VDD_CORE8_K6") (pintype "bidirectional"))
    )
    (net (code "311") (name "unconnected-(SIPE-VDD_CORE9-PadK8)") (class "Default")
      (node (ref "SIP") (pin "K8") (pinfunction "VDD_CORE9_K8") (pintype "bidirectional"))
    )
    (net (code "312") (name "unconnected-(SIPE-VDD_CORE10-PadK12)") (class "Default")
      (node (ref "SIP") (pin "K12") (pinfunction "VDD_CORE10_K12") (pintype "bidirectional"))
    )
    (net (code "313") (name "unconnected-(SIPE-VDD_CORE11-PadL6)") (class "Default")
      (node (ref "SIP") (pin "L6") (pinfunction "VDD_CORE11_L6") (pintype "bidirectional"))
    )
    (net (code "314") (name "unconnected-(SIPE-VDD_CORE12-PadL7)") (class "Default")
      (node (ref "SIP") (pin "L7") (pinfunction "VDD_CORE12_L7") (pintype "bidirectional"))
    )
    (net (code "315") (name "unconnected-(SIPE-VDD_CORE13-PadL8)") (class "Default")
      (node (ref "SIP") (pin "L8") (pinfunction "VDD_CORE13_L8") (pintype "bidirectional"))
    )
    (net (code "316") (name "unconnected-(SIPE-VDD_CORE14-PadL9)") (class "Default")
      (node (ref "SIP") (pin "L9") (pinfunction "VDD_CORE14_L9") (pintype "bidirectional"))
    )
    (net (code "317") (name "unconnected-(SIPE-VDD_CORE15-PadM11)") (class "Default")
      (node (ref "SIP") (pin "M11") (pinfunction "VDD_CORE15_M11") (pintype "bidirectional"))
    )
    (net (code "318") (name "unconnected-(SIPE-VDD_CORE16-PadM13)") (class "Default")
      (node (ref "SIP") (pin "M13") (pinfunction "VDD_CORE16_M13") (pintype "bidirectional"))
    )
    (net (code "319") (name "unconnected-(SIPE-VDD_CORE17-PadN8)") (class "Default")
      (node (ref "SIP") (pin "N8") (pinfunction "VDD_CORE17_N8") (pintype "bidirectional"))
    )
    (net (code "320") (name "unconnected-(SIPE-VDD_CORE18-PadN9)") (class "Default")
      (node (ref "SIP") (pin "N9") (pinfunction "VDD_CORE18_N9") (pintype "bidirectional"))
    )
    (net (code "321") (name "unconnected-(SIPE-VDD_CORE19-PadN12)") (class "Default")
      (node (ref "SIP") (pin "N12") (pinfunction "VDD_CORE19_N12") (pintype "bidirectional"))
    )
    (net (code "322") (name "unconnected-(SIPE-VDD_CORE20-PadN13)") (class "Default")
      (node (ref "SIP") (pin "N13") (pinfunction "VDD_CORE20_N13") (pintype "bidirectional"))
    )
    (net (code "323") (name "unconnected-(SIPE-VDD_MPU0-PadF10)") (class "Default")
      (node (ref "SIP") (pin "F10") (pinfunction "VDD_MPU0_F10") (pintype "bidirectional"))
    )
    (net (code "324") (name "unconnected-(SIPE-VDD_MPU1-PadF11)") (class "Default")
      (node (ref "SIP") (pin "F11") (pinfunction "VDD_MPU1_F11") (pintype "bidirectional"))
    )
    (net (code "325") (name "unconnected-(SIPE-VDD_MPU2-PadF12)") (class "Default")
      (node (ref "SIP") (pin "F12") (pinfunction "VDD_MPU2_F12") (pintype "bidirectional"))
    )
    (net (code "326") (name "unconnected-(SIPE-VDD_MPU3-PadF13)") (class "Default")
      (node (ref "SIP") (pin "F13") (pinfunction "VDD_MPU3_F13") (pintype "bidirectional"))
    )
    (net (code "327") (name "unconnected-(SIPE-VDD_MPU4-PadG13)") (class "Default")
      (node (ref "SIP") (pin "G13") (pinfunction "VDD_MPU4_G13") (pintype "bidirectional"))
    )
    (net (code "328") (name "unconnected-(SIPE-VDD_MPU5-PadH13)") (class "Default")
      (node (ref "SIP") (pin "H13") (pinfunction "VDD_MPU5_H13") (pintype "bidirectional"))
    )
    (net (code "329") (name "unconnected-(SIPE-VDD_MPU6-PadJ13)") (class "Default")
      (node (ref "SIP") (pin "J13") (pinfunction "VDD_MPU6_J13") (pintype "bidirectional"))
    )
    (net (code "330") (name "unconnected-(SIPE-VDD_MPU_MON-PadA2)") (class "Default")
      (node (ref "SIP") (pin "A2") (pinfunction "VDD_MPU_MON_A2") (pintype "bidirectional"))
    )
    (net (code "331") (name "unconnected-(SIPE-VDD_PLL1-PadE7)") (class "Default")
      (node (ref "SIP") (pin "E7") (pinfunction "VDD_PLL1_E7") (pintype "bidirectional"))
    )
    (net (code "332") (name "unconnected-(SIPE-VDD_PLL2-PadH15)") (class "Default")
      (node (ref "SIP") (pin "H15") (pinfunction "VDD_PLL2_H15") (pintype "bidirectional"))
    )
    (net (code "333") (name "unconnected-(SIPE-VDD_PLL3-PadR10)") (class "Default")
      (node (ref "SIP") (pin "R10") (pinfunction "VDD_PLL3_R10") (pintype "bidirectional"))
    )
    (net (code "334") (name "unconnected-(SIPE-VDD_PLL4-PadR11)") (class "Default")
      (node (ref "SIP") (pin "R11") (pinfunction "VDD_PLL4_R11") (pintype "bidirectional"))
    )
    (net (code "335") (name "unconnected-(SIPE-VPP-PadM5)") (class "Default")
      (node (ref "SIP") (pin "M5") (pinfunction "VPP_M5") (pintype "bidirectional"))
    )
    (net (code "336") (name "unconnected-(U1-N.C.-Pad5)") (class "Default")
      (node (ref "U1") (pin "5") (pinfunction "N.C._5") (pintype "no_connect"))
    )
    (net (code "337") (name "unconnected-(U4-ID-Pad3)") (class "Default")
      (node (ref "U4") (pin "3") (pinfunction "ID_3") (pintype "passive"))
    )
    (net (code "338") (name "unconnected-(U4-N.C.-Pad5)") (class "Default")
      (node (ref "U4") (pin "5") (pinfunction "N.C._5") (pintype "no_connect"))
    )
    (net (code "339") (name "unconnected-(U6-NC-Pad1)") (class "Default")
      (node (ref "U6") (pin "1") (pinfunction "NC_1") (pintype "passive"))
    )
    (net (code "340") (name "unconnected-(U8-NC1-PadE1)") (class "Default")
      (node (ref "U8") (pin "E1") (pinfunction "NC1_E1") (pintype "bidirectional"))
    )
    (net (code "341") (name "unconnected-(U8-NC2-PadE2)") (class "Default")
      (node (ref "U8") (pin "E2") (pinfunction "NC2_E2") (pintype "bidirectional"))
    )
    (net (code "342") (name "unconnected-(U8-NC3-PadE3)") (class "Default")
      (node (ref "U8") (pin "E3") (pinfunction "NC3_E3") (pintype "bidirectional"))
    )
    (net (code "343") (name "unconnected-(U8-NC4-PadA2)") (class "Default")
      (node (ref "U8") (pin "A2") (pinfunction "NC4_A2") (pintype "bidirectional"))
    )
    (net (code "344") (name "unconnected-(U8-NC5-PadA6)") (class "Default")
      (node (ref "U8") (pin "A6") (pinfunction "NC5_A6") (pintype "bidirectional"))
    )
    (net (code "345") (name "unconnected-(U8-NC6-PadA7)") (class "Default")
      (node (ref "U8") (pin "A7") (pinfunction "NC6_A7") (pintype "bidirectional"))
    )
    (net (code "346") (name "unconnected-(U8-NC7-PadA8)") (class "Default")
      (node (ref "U8") (pin "A8") (pinfunction "NC7_A8") (pintype "bidirectional"))
    )
    (net (code "347") (name "unconnected-(U8-NC8-PadE8)") (class "Default")
      (node (ref "U8") (pin "E8") (pinfunction "NC8_E8") (pintype "bidirectional"))
    )
    (net (code "348") (name "unconnected-(U8-NC9-PadE9)") (class "Default")
      (node (ref "U8") (pin "E9") (pinfunction "NC9_E9") (pintype "bidirectional"))
    )
    (net (code "349") (name "unconnected-(U8-NC10-PadE10)") (class "Default")
      (node (ref "U8") (pin "E10") (pinfunction "NC10_E10") (pintype "bidirectional"))
    )
    (net (code "350") (name "unconnected-(U8-NC11-PadA1)") (class "Default")
      (node (ref "U8") (pin "A1") (pinfunction "NC11_A1") (pintype "bidirectional"))
    )
    (net (code "351") (name "unconnected-(U8-NC12-PadE12)") (class "Default")
      (node (ref "U8") (pin "E12") (pinfunction "NC12_E12") (pintype "bidirectional"))
    )
    (net (code "352") (name "unconnected-(U8-NC13-PadE13)") (class "Default")
      (node (ref "U8") (pin "E13") (pinfunction "NC13_E13") (pintype "bidirectional"))
    )
    (net (code "353") (name "unconnected-(U8-NC14-PadE14)") (class "Default")
      (node (ref "U8") (pin "E14") (pinfunction "NC14_E14") (pintype "bidirectional"))
    )
    (net (code "354") (name "unconnected-(U8-NC15-PadF1)") (class "Default")
      (node (ref "U8") (pin "F1") (pinfunction "NC15_F1") (pintype "bidirectional"))
    )
    (net (code "355") (name "unconnected-(U8-NC16-PadF2)") (class "Default")
      (node (ref "U8") (pin "F2") (pinfunction "NC16_F2") (pintype "bidirectional"))
    )
    (net (code "356") (name "unconnected-(U8-NC17-PadF3)") (class "Default")
      (node (ref "U8") (pin "F3") (pinfunction "NC17_F3") (pintype "bidirectional"))
    )
    (net (code "357") (name "unconnected-(U8-NC18-PadA9)") (class "Default")
      (node (ref "U8") (pin "A9") (pinfunction "NC18_A9") (pintype "bidirectional"))
    )
    (net (code "358") (name "unconnected-(U8-NC19-PadB14)") (class "Default")
      (node (ref "U8") (pin "B14") (pinfunction "NC19_B14") (pintype "bidirectional"))
    )
    (net (code "359") (name "unconnected-(U8-NC20-PadC14)") (class "Default")
      (node (ref "U8") (pin "C14") (pinfunction "NC20_C14") (pintype "bidirectional"))
    )
    (net (code "360") (name "unconnected-(U8-NC21-PadC13)") (class "Default")
      (node (ref "U8") (pin "C13") (pinfunction "NC21_C13") (pintype "bidirectional"))
    )
    (net (code "361") (name "unconnected-(U8-NC22-PadC12)") (class "Default")
      (node (ref "U8") (pin "C12") (pinfunction "NC22_C12") (pintype "bidirectional"))
    )
    (net (code "362") (name "unconnected-(U8-NC23-PadC11)") (class "Default")
      (node (ref "U8") (pin "C11") (pinfunction "NC23_C11") (pintype "bidirectional"))
    )
    (net (code "363") (name "unconnected-(U8-NC24-PadF10)") (class "Default")
      (node (ref "U8") (pin "F10") (pinfunction "NC24_F10") (pintype "bidirectional"))
    )
    (net (code "364") (name "unconnected-(U8-NC25-PadC10)") (class "Default")
      (node (ref "U8") (pin "C10") (pinfunction "NC25_C10") (pintype "bidirectional"))
    )
    (net (code "365") (name "unconnected-(U8-NC26-PadF12)") (class "Default")
      (node (ref "U8") (pin "F12") (pinfunction "NC26_F12") (pintype "bidirectional"))
    )
    (net (code "366") (name "unconnected-(U8-NC27-PadF13)") (class "Default")
      (node (ref "U8") (pin "F13") (pinfunction "NC27_F13") (pintype "bidirectional"))
    )
    (net (code "367") (name "unconnected-(U8-NC28-PadF14)") (class "Default")
      (node (ref "U8") (pin "F14") (pinfunction "NC28_F14") (pintype "bidirectional"))
    )
    (net (code "368") (name "unconnected-(U8-NC29-PadC9)") (class "Default")
      (node (ref "U8") (pin "C9") (pinfunction "NC29_C9") (pintype "bidirectional"))
    )
    (net (code "369") (name "unconnected-(U8-NC30-PadC8)") (class "Default")
      (node (ref "U8") (pin "C8") (pinfunction "NC30_C8") (pintype "bidirectional"))
    )
    (net (code "370") (name "unconnected-(U8-NC31-PadC7)") (class "Default")
      (node (ref "U8") (pin "C7") (pinfunction "NC31_C7") (pintype "bidirectional"))
    )
    (net (code "371") (name "unconnected-(U8-NC32-PadC5)") (class "Default")
      (node (ref "U8") (pin "C5") (pinfunction "NC32_C5") (pintype "bidirectional"))
    )
    (net (code "372") (name "unconnected-(U8-NC33-PadC3)") (class "Default")
      (node (ref "U8") (pin "C3") (pinfunction "NC33_C3") (pintype "bidirectional"))
    )
    (net (code "373") (name "unconnected-(U8-NC34-PadC1)") (class "Default")
      (node (ref "U8") (pin "C1") (pinfunction "NC34_C1") (pintype "bidirectional"))
    )
    (net (code "374") (name "unconnected-(U8-NC35-PadD14)") (class "Default")
      (node (ref "U8") (pin "D14") (pinfunction "NC35_D14") (pintype "bidirectional"))
    )
    (net (code "375") (name "unconnected-(U8-NC36-PadD13)") (class "Default")
      (node (ref "U8") (pin "D13") (pinfunction "NC36_D13") (pintype "bidirectional"))
    )
    (net (code "376") (name "unconnected-(U8-NC37-PadD12)") (class "Default")
      (node (ref "U8") (pin "D12") (pinfunction "NC37_D12") (pintype "bidirectional"))
    )
    (net (code "377") (name "unconnected-(U8-NC38-PadD4)") (class "Default")
      (node (ref "U8") (pin "D4") (pinfunction "NC38_D4") (pintype "bidirectional"))
    )
    (net (code "378") (name "unconnected-(U8-NC39-PadD3)") (class "Default")
      (node (ref "U8") (pin "D3") (pinfunction "NC39_D3") (pintype "bidirectional"))
    )
    (net (code "379") (name "unconnected-(U8-NC40-PadG12)") (class "Default")
      (node (ref "U8") (pin "G12") (pinfunction "NC40_G12") (pintype "bidirectional"))
    )
    (net (code "380") (name "unconnected-(U8-NC41-PadG13)") (class "Default")
      (node (ref "U8") (pin "G13") (pinfunction "NC41_G13") (pintype "bidirectional"))
    )
    (net (code "381") (name "unconnected-(U8-NC42-PadG14)") (class "Default")
      (node (ref "U8") (pin "G14") (pinfunction "NC42_G14") (pintype "bidirectional"))
    )
    (net (code "382") (name "unconnected-(U8-NC43-PadH1)") (class "Default")
      (node (ref "U8") (pin "H1") (pinfunction "NC43_H1") (pintype "bidirectional"))
    )
    (net (code "383") (name "unconnected-(U8-NC44-PadH2)") (class "Default")
      (node (ref "U8") (pin "H2") (pinfunction "NC44_H2") (pintype "bidirectional"))
    )
    (net (code "384") (name "unconnected-(U8-NC45-PadH3)") (class "Default")
      (node (ref "U8") (pin "H3") (pinfunction "NC45_H3") (pintype "bidirectional"))
    )
    (net (code "385") (name "unconnected-(U8-NC46-PadD2)") (class "Default")
      (node (ref "U8") (pin "D2") (pinfunction "NC46_D2") (pintype "bidirectional"))
    )
    (net (code "386") (name "unconnected-(U8-NC47-PadH5)") (class "Default")
      (node (ref "U8") (pin "H5") (pinfunction "NC47_H5") (pintype "bidirectional"))
    )
    (net (code "387") (name "unconnected-(U8-NC48-PadD1)") (class "Default")
      (node (ref "U8") (pin "D1") (pinfunction "NC48_D1") (pintype "bidirectional"))
    )
    (net (code "388") (name "unconnected-(U8-NC49-PadB13)") (class "Default")
      (node (ref "U8") (pin "B13") (pinfunction "NC49_B13") (pintype "bidirectional"))
    )
    (net (code "389") (name "unconnected-(U8-NC50-PadB12)") (class "Default")
      (node (ref "U8") (pin "B12") (pinfunction "NC50_B12") (pintype "bidirectional"))
    )
    (net (code "390") (name "unconnected-(U8-NC51-PadB11)") (class "Default")
      (node (ref "U8") (pin "B11") (pinfunction "NC51_B11") (pintype "bidirectional"))
    )
    (net (code "391") (name "unconnected-(U8-NC52-PadB10)") (class "Default")
      (node (ref "U8") (pin "B10") (pinfunction "NC52_B10") (pintype "bidirectional"))
    )
    (net (code "392") (name "unconnected-(U8-NC53-PadB9)") (class "Default")
      (node (ref "U8") (pin "B9") (pinfunction "NC53_B9") (pintype "bidirectional"))
    )
    (net (code "393") (name "unconnected-(U8-NC54-PadH12)") (class "Default")
      (node (ref "U8") (pin "H12") (pinfunction "NC54_H12") (pintype "bidirectional"))
    )
    (net (code "394") (name "unconnected-(U8-NC55-PadH13)") (class "Default")
      (node (ref "U8") (pin "H13") (pinfunction "NC55_H13") (pintype "bidirectional"))
    )
    (net (code "395") (name "unconnected-(U8-NC56-PadH14)") (class "Default")
      (node (ref "U8") (pin "H14") (pinfunction "NC56_H14") (pintype "bidirectional"))
    )
    (net (code "396") (name "unconnected-(U8-NC57-PadJ1)") (class "Default")
      (node (ref "U8") (pin "J1") (pinfunction "NC57_J1") (pintype "bidirectional"))
    )
    (net (code "397") (name "unconnected-(U8-NC58-PadJ2)") (class "Default")
      (node (ref "U8") (pin "J2") (pinfunction "NC58_J2") (pintype "bidirectional"))
    )
    (net (code "398") (name "unconnected-(U8-NC59-PadJ3)") (class "Default")
      (node (ref "U8") (pin "J3") (pinfunction "NC59_J3") (pintype "bidirectional"))
    )
    (net (code "399") (name "unconnected-(U8-NC60-PadJ5)") (class "Default")
      (node (ref "U8") (pin "J5") (pinfunction "NC60_J5") (pintype "bidirectional"))
    )
    (net (code "400") (name "unconnected-(U8-NC61-PadP8)") (class "Default")
      (node (ref "U8") (pin "P8") (pinfunction "NC61_P8") (pintype "bidirectional"))
    )
    (net (code "401") (name "unconnected-(U8-NC62-PadP9)") (class "Default")
      (node (ref "U8") (pin "P9") (pinfunction "NC62_P9") (pintype "bidirectional"))
    )
    (net (code "402") (name "unconnected-(U8-NC63-PadP7)") (class "Default")
      (node (ref "U8") (pin "P7") (pinfunction "NC63_P7") (pintype "bidirectional"))
    )
    (net (code "403") (name "unconnected-(U8-NC64-PadP2)") (class "Default")
      (node (ref "U8") (pin "P2") (pinfunction "NC64_P2") (pintype "bidirectional"))
    )
    (net (code "404") (name "unconnected-(U8-NC65-PadP1)") (class "Default")
      (node (ref "U8") (pin "P1") (pinfunction "NC65_P1") (pintype "bidirectional"))
    )
    (net (code "405") (name "unconnected-(U8-NC66-PadN14)") (class "Default")
      (node (ref "U8") (pin "N14") (pinfunction "NC66_N14") (pintype "bidirectional"))
    )
    (net (code "406") (name "unconnected-(U8-NC67-PadN13)") (class "Default")
      (node (ref "U8") (pin "N13") (pinfunction "NC67_N13") (pintype "bidirectional"))
    )
    (net (code "407") (name "unconnected-(U8-NC68-PadN12)") (class "Default")
      (node (ref "U8") (pin "N12") (pinfunction "NC68_N12") (pintype "bidirectional"))
    )
    (net (code "408") (name "unconnected-(U8-NC69-PadJ13)") (class "Default")
      (node (ref "U8") (pin "J13") (pinfunction "NC69_J13") (pintype "bidirectional"))
    )
    (net (code "409") (name "unconnected-(U8-NC70-PadJ14)") (class "Default")
      (node (ref "U8") (pin "J14") (pinfunction "NC70_J14") (pintype "bidirectional"))
    )
    (net (code "410") (name "unconnected-(U8-NC71-PadK1)") (class "Default")
      (node (ref "U8") (pin "K1") (pinfunction "NC71_K1") (pintype "bidirectional"))
    )
    (net (code "411") (name "unconnected-(U8-NC72-PadK2)") (class "Default")
      (node (ref "U8") (pin "K2") (pinfunction "NC72_K2") (pintype "bidirectional"))
    )
    (net (code "412") (name "unconnected-(U8-NC73-PadK3)") (class "Default")
      (node (ref "U8") (pin "K3") (pinfunction "NC73_K3") (pintype "bidirectional"))
    )
    (net (code "413") (name "unconnected-(U8-NC74-PadB8)") (class "Default")
      (node (ref "U8") (pin "B8") (pinfunction "NC74_B8") (pintype "bidirectional"))
    )
    (net (code "414") (name "unconnected-(U8-NC75-PadN10)") (class "Default")
      (node (ref "U8") (pin "N10") (pinfunction "NC75_N10") (pintype "bidirectional"))
    )
    (net (code "415") (name "unconnected-(U8-NC76-PadN11)") (class "Default")
      (node (ref "U8") (pin "N11") (pinfunction "NC76_N11") (pintype "bidirectional"))
    )
    (net (code "416") (name "unconnected-(U8-NC77-PadK7)") (class "Default")
      (node (ref "U8") (pin "K7") (pinfunction "NC77_K7") (pintype "bidirectional"))
    )
    (net (code "417") (name "unconnected-(U8-NC78-PadG10)") (class "Default")
      (node (ref "U8") (pin "G10") (pinfunction "NC78_G10") (pintype "bidirectional"))
    )
    (net (code "418") (name "unconnected-(U8-NC79-PadG3)") (class "Default")
      (node (ref "U8") (pin "G3") (pinfunction "NC79_G3") (pintype "bidirectional"))
    )
    (net (code "419") (name "unconnected-(U8-NC80-PadK10)") (class "Default")
      (node (ref "U8") (pin "K10") (pinfunction "NC80_K10") (pintype "bidirectional"))
    )
    (net (code "420") (name "unconnected-(U8-NC81-PadG2)") (class "Default")
      (node (ref "U8") (pin "G2") (pinfunction "NC81_G2") (pintype "bidirectional"))
    )
    (net (code "421") (name "unconnected-(U8-NC82-PadK12)") (class "Default")
      (node (ref "U8") (pin "K12") (pinfunction "NC82_K12") (pintype "bidirectional"))
    )
    (net (code "422") (name "unconnected-(U8-NC83-PadK13)") (class "Default")
      (node (ref "U8") (pin "K13") (pinfunction "NC83_K13") (pintype "bidirectional"))
    )
    (net (code "423") (name "unconnected-(U8-NC84-PadK14)") (class "Default")
      (node (ref "U8") (pin "K14") (pinfunction "NC84_K14") (pintype "bidirectional"))
    )
    (net (code "424") (name "unconnected-(U8-NC85-PadL1)") (class "Default")
      (node (ref "U8") (pin "L1") (pinfunction "NC85_L1") (pintype "bidirectional"))
    )
    (net (code "425") (name "unconnected-(U8-NC86-PadL2)") (class "Default")
      (node (ref "U8") (pin "L2") (pinfunction "NC86_L2") (pintype "bidirectional"))
    )
    (net (code "426") (name "unconnected-(U8-NC87-PadL3)") (class "Default")
      (node (ref "U8") (pin "L3") (pinfunction "NC87_L3") (pintype "bidirectional"))
    )
    (net (code "427") (name "unconnected-(U8-NC88-PadG1)") (class "Default")
      (node (ref "U8") (pin "G1") (pinfunction "NC88_G1") (pintype "bidirectional"))
    )
    (net (code "428") (name "unconnected-(U8-NC89-PadB7)") (class "Default")
      (node (ref "U8") (pin "B7") (pinfunction "NC89_B7") (pintype "bidirectional"))
    )
    (net (code "429") (name "unconnected-(U8-NC90-PadB1)") (class "Default")
      (node (ref "U8") (pin "B1") (pinfunction "NC90_B1") (pintype "bidirectional"))
    )
    (net (code "430") (name "unconnected-(U8-NC91-PadA14)") (class "Default")
      (node (ref "U8") (pin "A14") (pinfunction "NC91_A14") (pintype "bidirectional"))
    )
    (net (code "431") (name "unconnected-(U8-NC92-PadA13)") (class "Default")
      (node (ref "U8") (pin "A13") (pinfunction "NC92_A13") (pintype "bidirectional"))
    )
    (net (code "432") (name "unconnected-(U8-NC93-PadA12)") (class "Default")
      (node (ref "U8") (pin "A12") (pinfunction "NC93_A12") (pintype "bidirectional"))
    )
    (net (code "433") (name "unconnected-(U8-NC94-PadA11)") (class "Default")
      (node (ref "U8") (pin "A11") (pinfunction "NC94_A11") (pintype "bidirectional"))
    )
    (net (code "434") (name "unconnected-(U8-NC95-PadA10)") (class "Default")
      (node (ref "U8") (pin "A10") (pinfunction "NC95_A10") (pintype "bidirectional"))
    )
    (net (code "435") (name "unconnected-(U8-NC96-PadL12)") (class "Default")
      (node (ref "U8") (pin "L12") (pinfunction "NC96_L12") (pintype "bidirectional"))
    )
    (net (code "436") (name "unconnected-(U8-NC97-PadL13)") (class "Default")
      (node (ref "U8") (pin "L13") (pinfunction "NC97_L13") (pintype "bidirectional"))
    )
    (net (code "437") (name "unconnected-(U8-NC98-PadL14)") (class "Default")
      (node (ref "U8") (pin "L14") (pinfunction "NC98_L14") (pintype "bidirectional"))
    )
    (net (code "438") (name "unconnected-(U8-NC99-PadM1)") (class "Default")
      (node (ref "U8") (pin "M1") (pinfunction "NC99_M1") (pintype "bidirectional"))
    )
    (net (code "439") (name "unconnected-(U8-NC100-PadM2)") (class "Default")
      (node (ref "U8") (pin "M2") (pinfunction "NC100_M2") (pintype "bidirectional"))
    )
    (net (code "440") (name "unconnected-(U8-NC101-PadM3)") (class "Default")
      (node (ref "U8") (pin "M3") (pinfunction "NC101_M3") (pintype "bidirectional"))
    )
    (net (code "441") (name "unconnected-(U8-NC102-PadP13)") (class "Default")
      (node (ref "U8") (pin "P13") (pinfunction "NC102_P13") (pintype "bidirectional"))
    )
    (net (code "442") (name "unconnected-(U8-NC103-PadP12)") (class "Default")
      (node (ref "U8") (pin "P12") (pinfunction "NC103_P12") (pintype "bidirectional"))
    )
    (net (code "443") (name "unconnected-(U8-NC104-PadP11)") (class "Default")
      (node (ref "U8") (pin "P11") (pinfunction "NC104_P11") (pintype "bidirectional"))
    )
    (net (code "444") (name "unconnected-(U8-NC105-PadM7)") (class "Default")
      (node (ref "U8") (pin "M7") (pinfunction "NC105_M7") (pintype "bidirectional"))
    )
    (net (code "445") (name "unconnected-(U8-NC106-PadM8)") (class "Default")
      (node (ref "U8") (pin "M8") (pinfunction "NC106_M8") (pintype "bidirectional"))
    )
    (net (code "446") (name "unconnected-(U8-NC107-PadM9)") (class "Default")
      (node (ref "U8") (pin "M9") (pinfunction "NC107_M9") (pintype "bidirectional"))
    )
    (net (code "447") (name "unconnected-(U8-NC108-PadM10)") (class "Default")
      (node (ref "U8") (pin "M10") (pinfunction "NC108_M10") (pintype "bidirectional"))
    )
    (net (code "448") (name "unconnected-(U8-NC109-PadM11)") (class "Default")
      (node (ref "U8") (pin "M11") (pinfunction "NC109_M11") (pintype "bidirectional"))
    )
    (net (code "449") (name "unconnected-(U8-NC110-PadM12)") (class "Default")
      (node (ref "U8") (pin "M12") (pinfunction "NC110_M12") (pintype "bidirectional"))
    )
    (net (code "450") (name "unconnected-(U8-NC111-PadM13)") (class "Default")
      (node (ref "U8") (pin "M13") (pinfunction "NC111_M13") (pintype "bidirectional"))
    )
    (net (code "451") (name "unconnected-(U8-NC112-PadM14)") (class "Default")
      (node (ref "U8") (pin "M14") (pinfunction "NC112_M14") (pintype "bidirectional"))
    )
    (net (code "452") (name "unconnected-(U8-NC113-PadN1)") (class "Default")
      (node (ref "U8") (pin "N1") (pinfunction "NC113_N1") (pintype "bidirectional"))
    )
    (net (code "453") (name "unconnected-(U8-NC114-PadP10)") (class "Default")
      (node (ref "U8") (pin "P10") (pinfunction "NC114_P10") (pintype "bidirectional"))
    )
    (net (code "454") (name "unconnected-(U8-NC115-PadN3)") (class "Default")
      (node (ref "U8") (pin "N3") (pinfunction "NC115_N3") (pintype "bidirectional"))
    )
    (net (code "455") (name "unconnected-(U8-NC116-PadP14)") (class "Default")
      (node (ref "U8") (pin "P14") (pinfunction "NC116_P14") (pintype "bidirectional"))
    )
    (net (code "456") (name "unconnected-(U8-NC117-PadJ12)") (class "Default")
      (node (ref "U8") (pin "J12") (pinfunction "NC117_J12") (pintype "bidirectional"))
    )
    (net (code "457") (name "unconnected-(U8-NC118-PadN7)") (class "Default")
      (node (ref "U8") (pin "N7") (pinfunction "NC118_N7") (pintype "bidirectional"))
    )
    (net (code "458") (name "unconnected-(U8-NC119-PadN8)") (class "Default")
      (node (ref "U8") (pin "N8") (pinfunction "NC119_N8") (pintype "bidirectional"))
    )
    (net (code "459") (name "unconnected-(U8-NC120-PadN9)") (class "Default")
      (node (ref "U8") (pin "N9") (pinfunction "NC120_N9") (pintype "bidirectional"))
    )
    (net (code "460") (name "unconnected-(U8-NC121-PadE5)") (class "Default")
      (node (ref "U8") (pin "E5") (pinfunction "NC121_E5") (pintype "bidirectional"))
    )
    (net (code "461") (name "unconnected-(U8-NC122-PadN6)") (class "Default")
      (node (ref "U8") (pin "N6") (pinfunction "NC122_N6") (pintype "bidirectional"))
    )
    (net (code "462") (name "unconnected-(U8-NC123-PadK6)") (class "Default")
      (node (ref "U8") (pin "K6") (pinfunction "NC123_K6") (pintype "bidirectional"))
    )
  )
)
